# sensor_frontend_test_v0_5_1f4504da.net
KiCad netlist of a schematic drawn in EAGLE
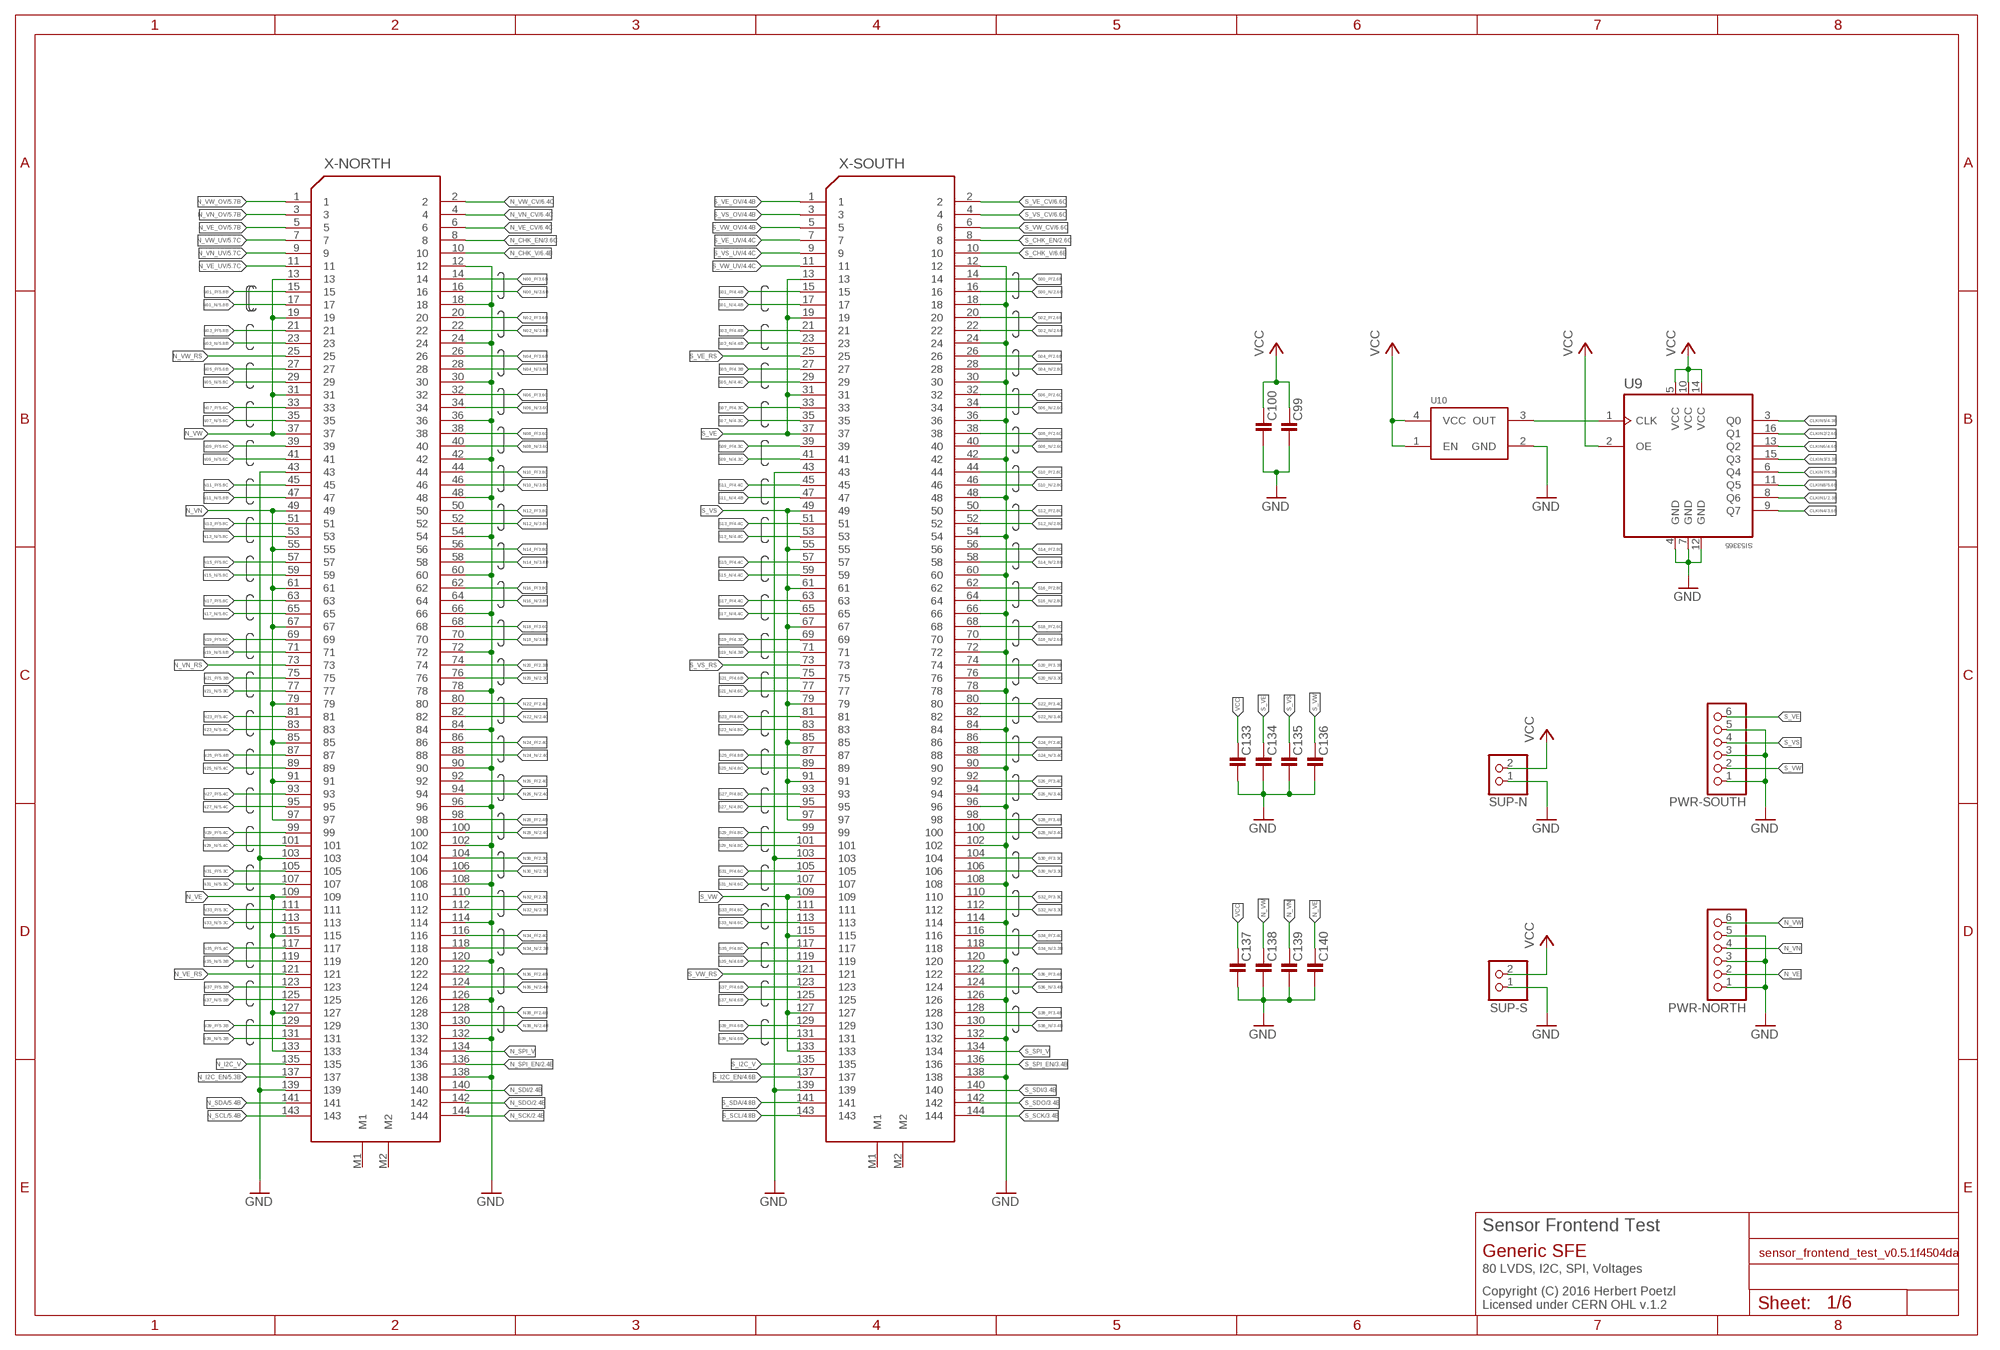
[diagram p0: schematic, sheet 1]
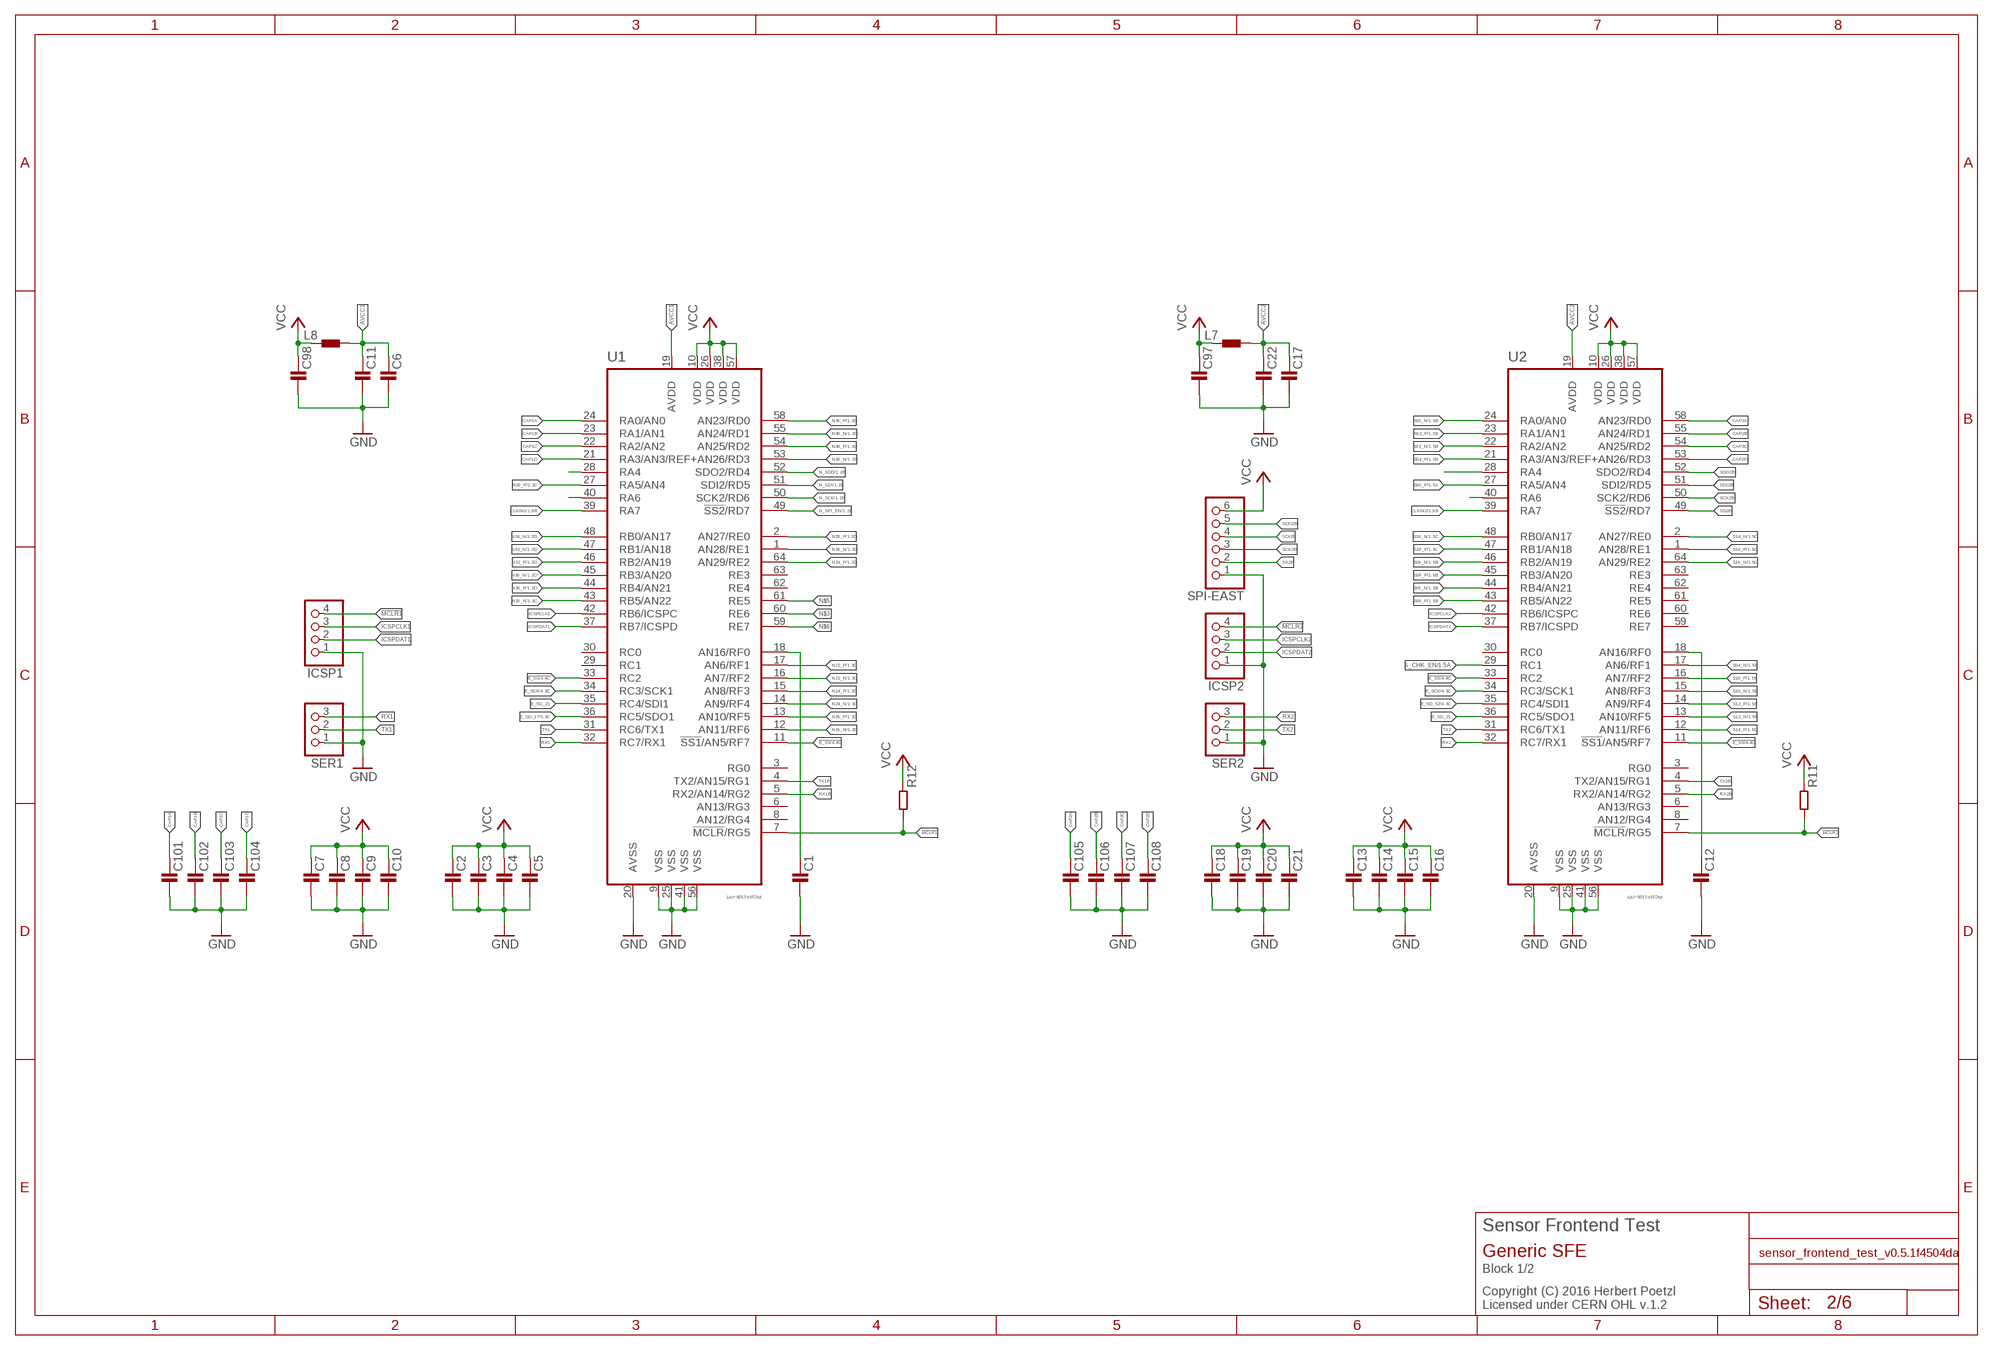
[diagram p1: schematic, sheet 2]
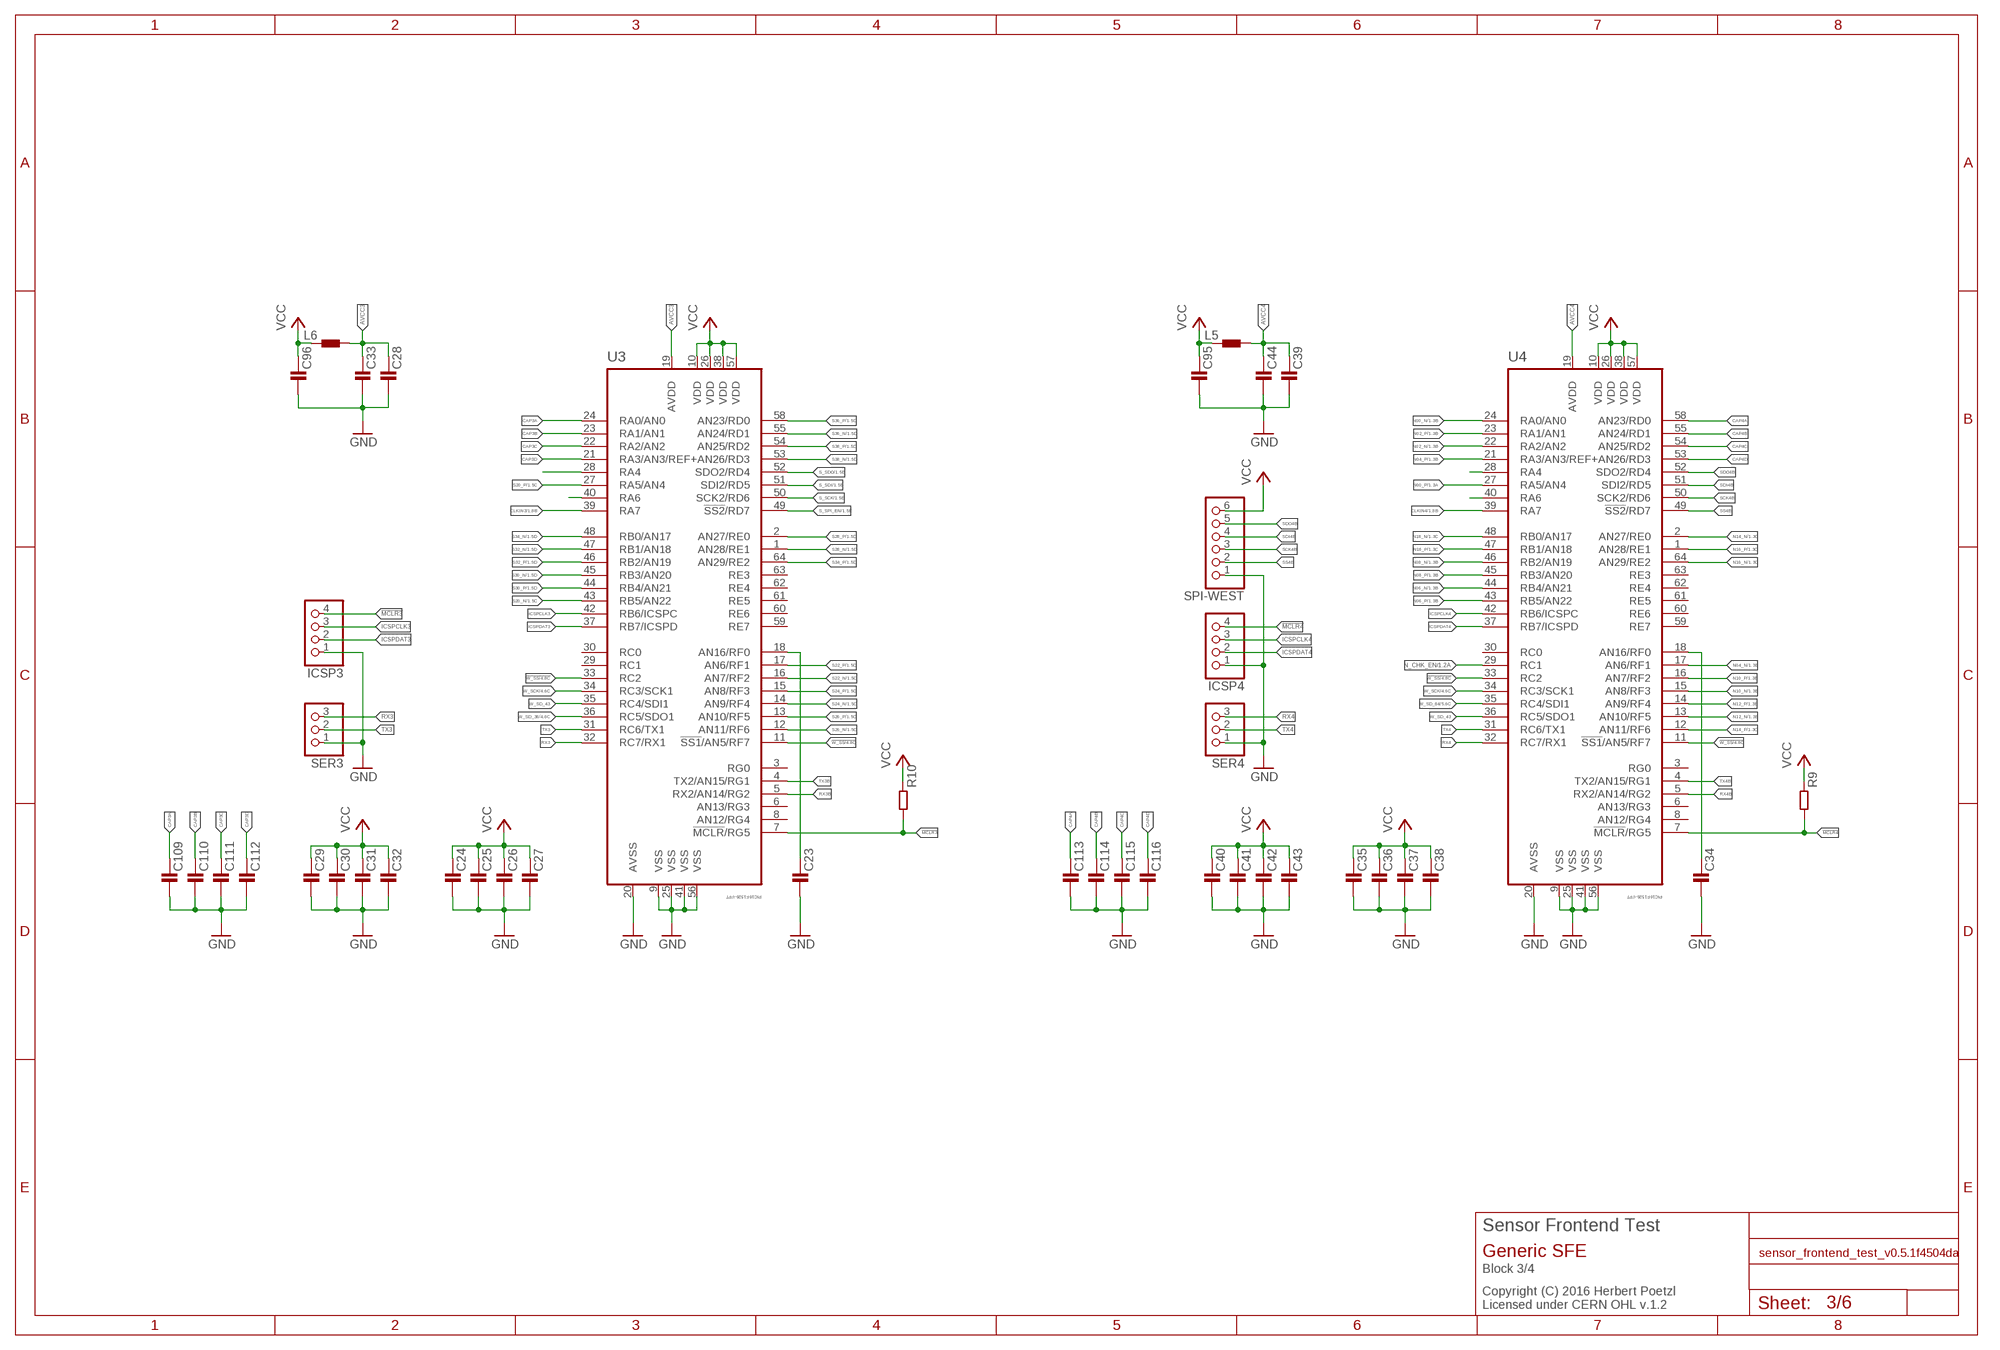
[diagram p2: schematic, sheet 3]
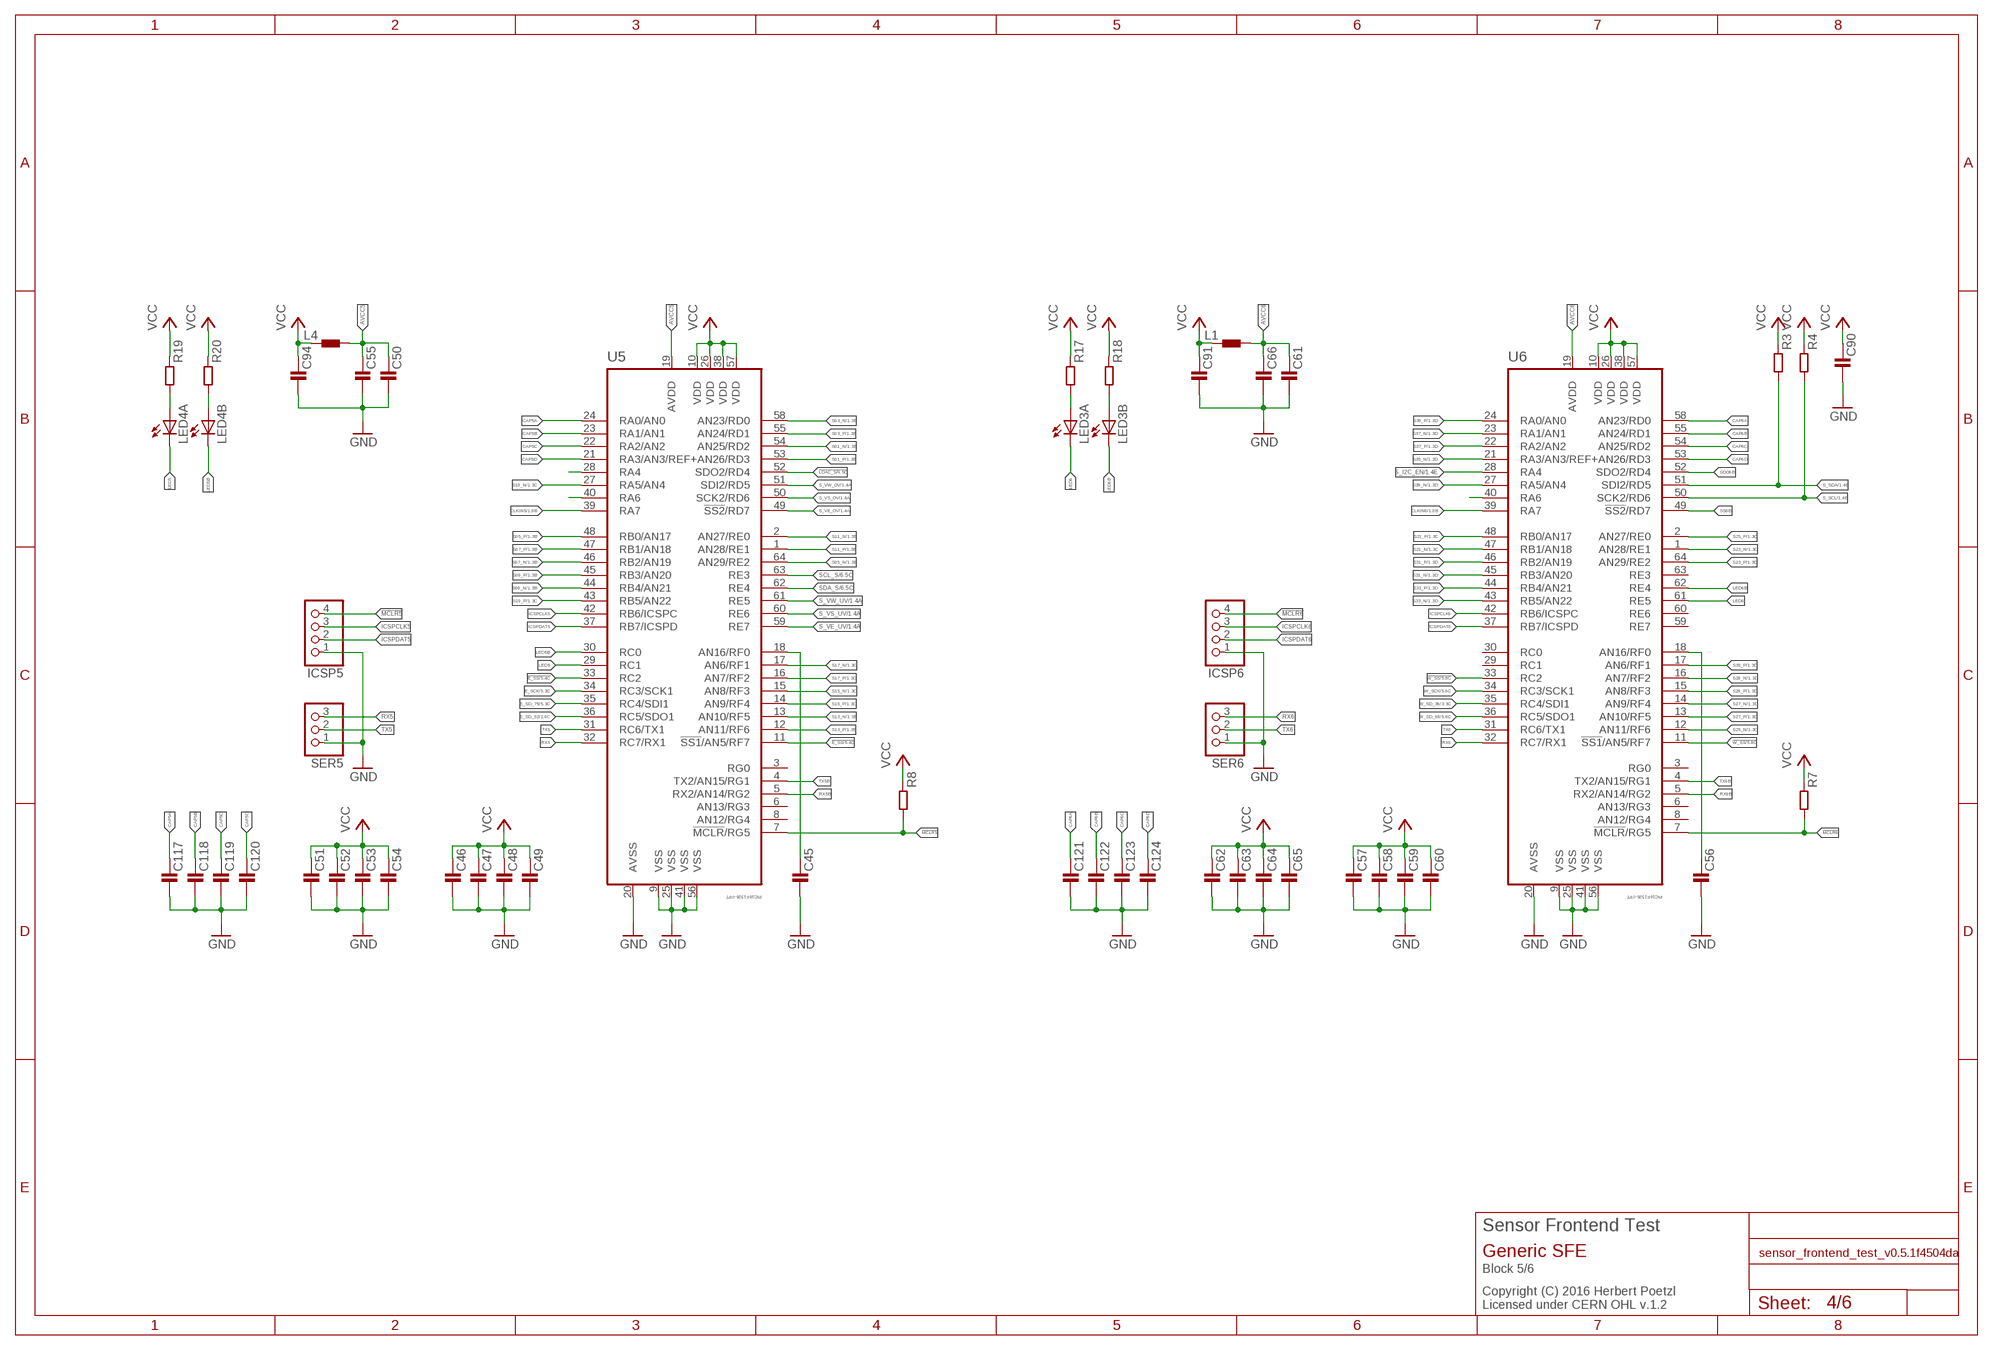
[diagram p3: schematic, sheet 4]
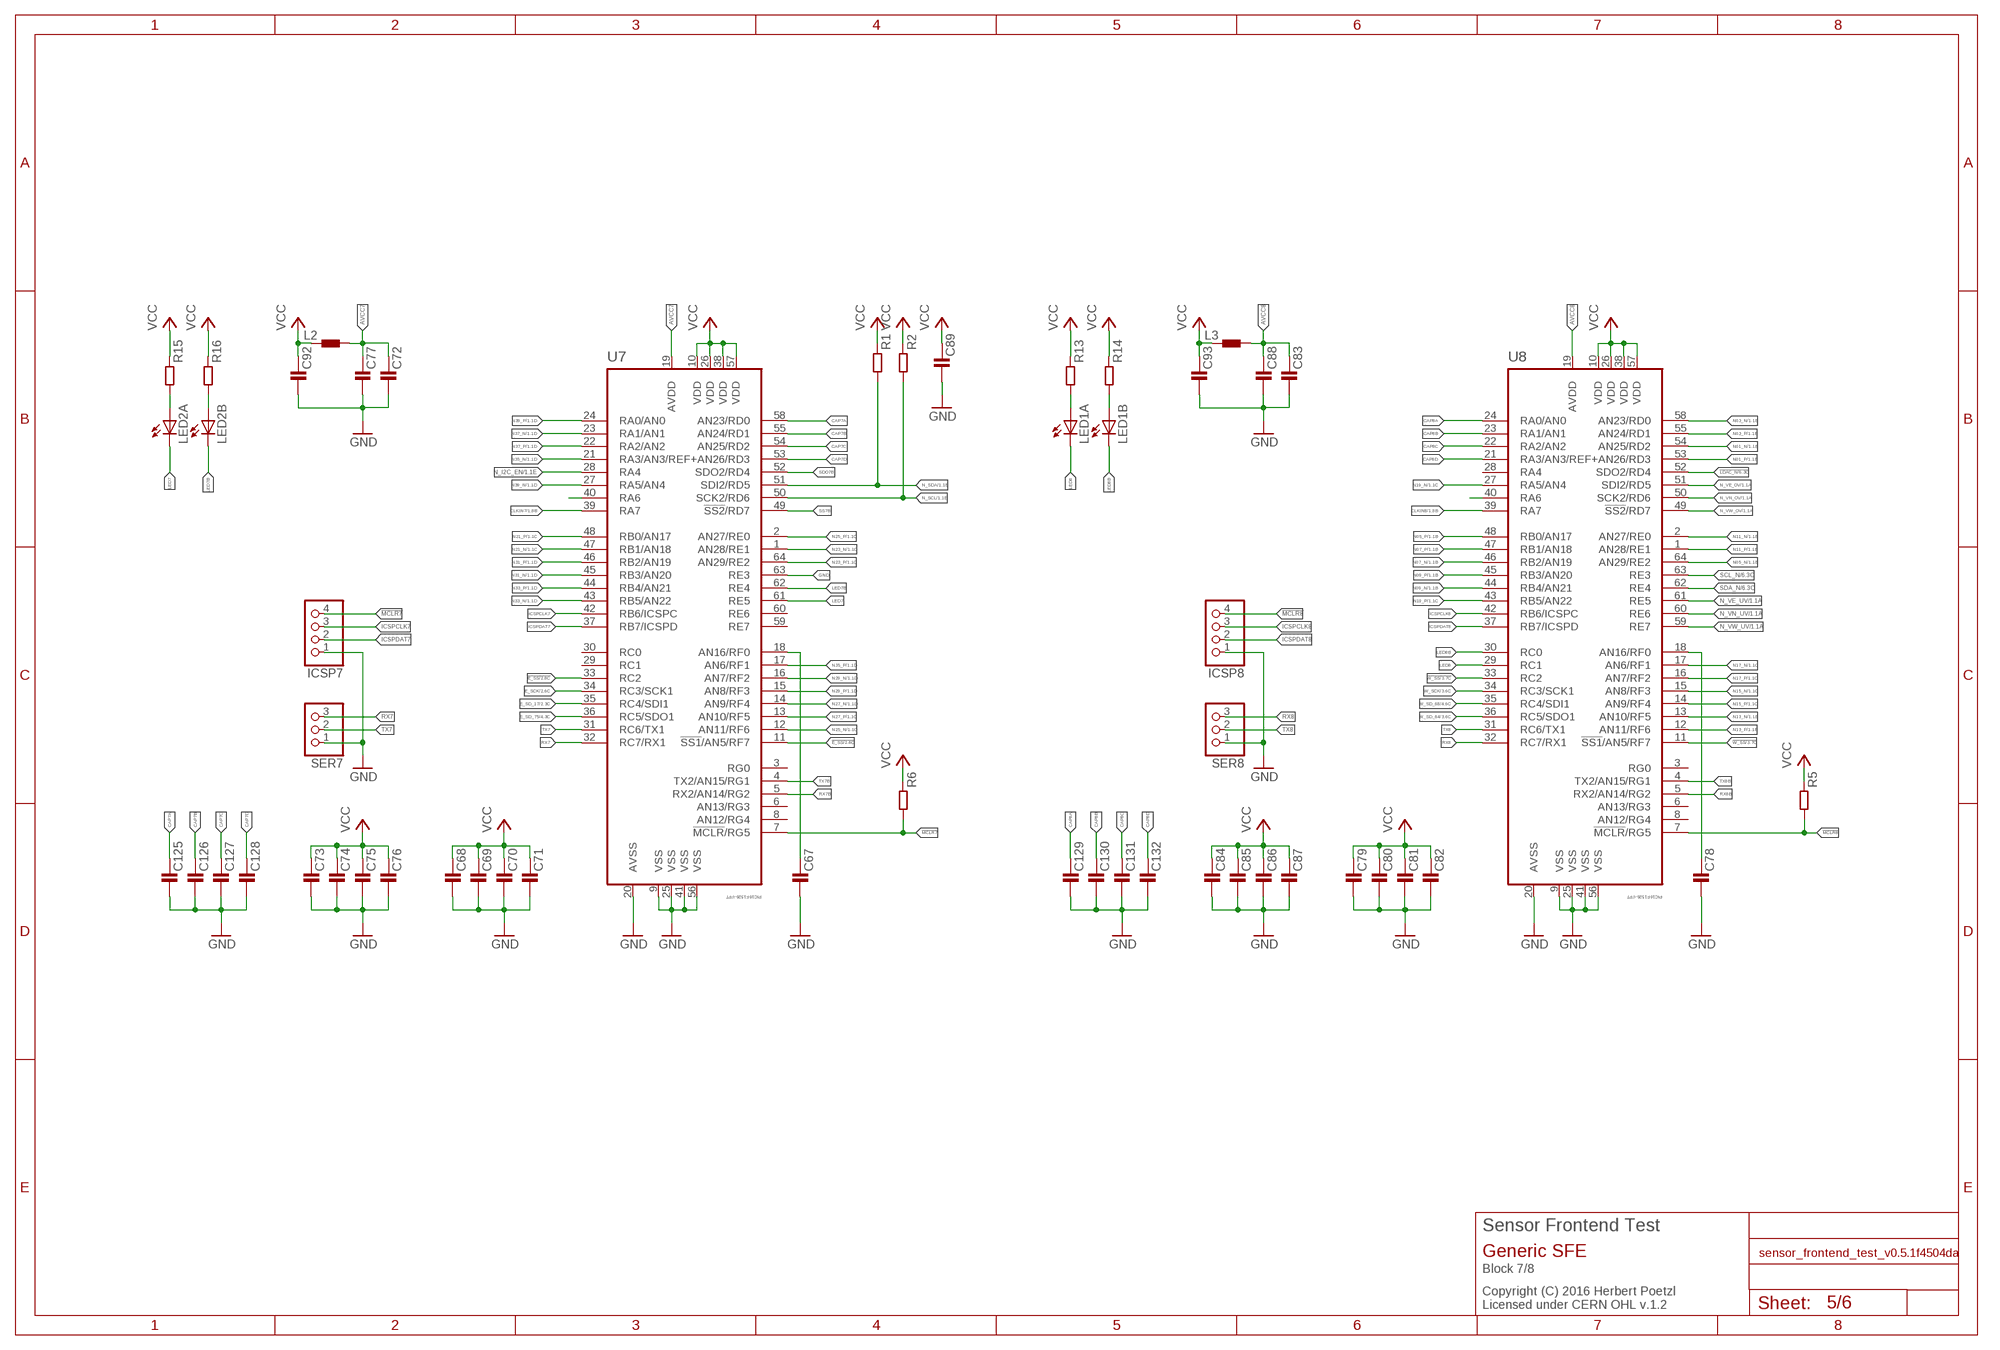
[diagram p4: schematic, sheet 5]
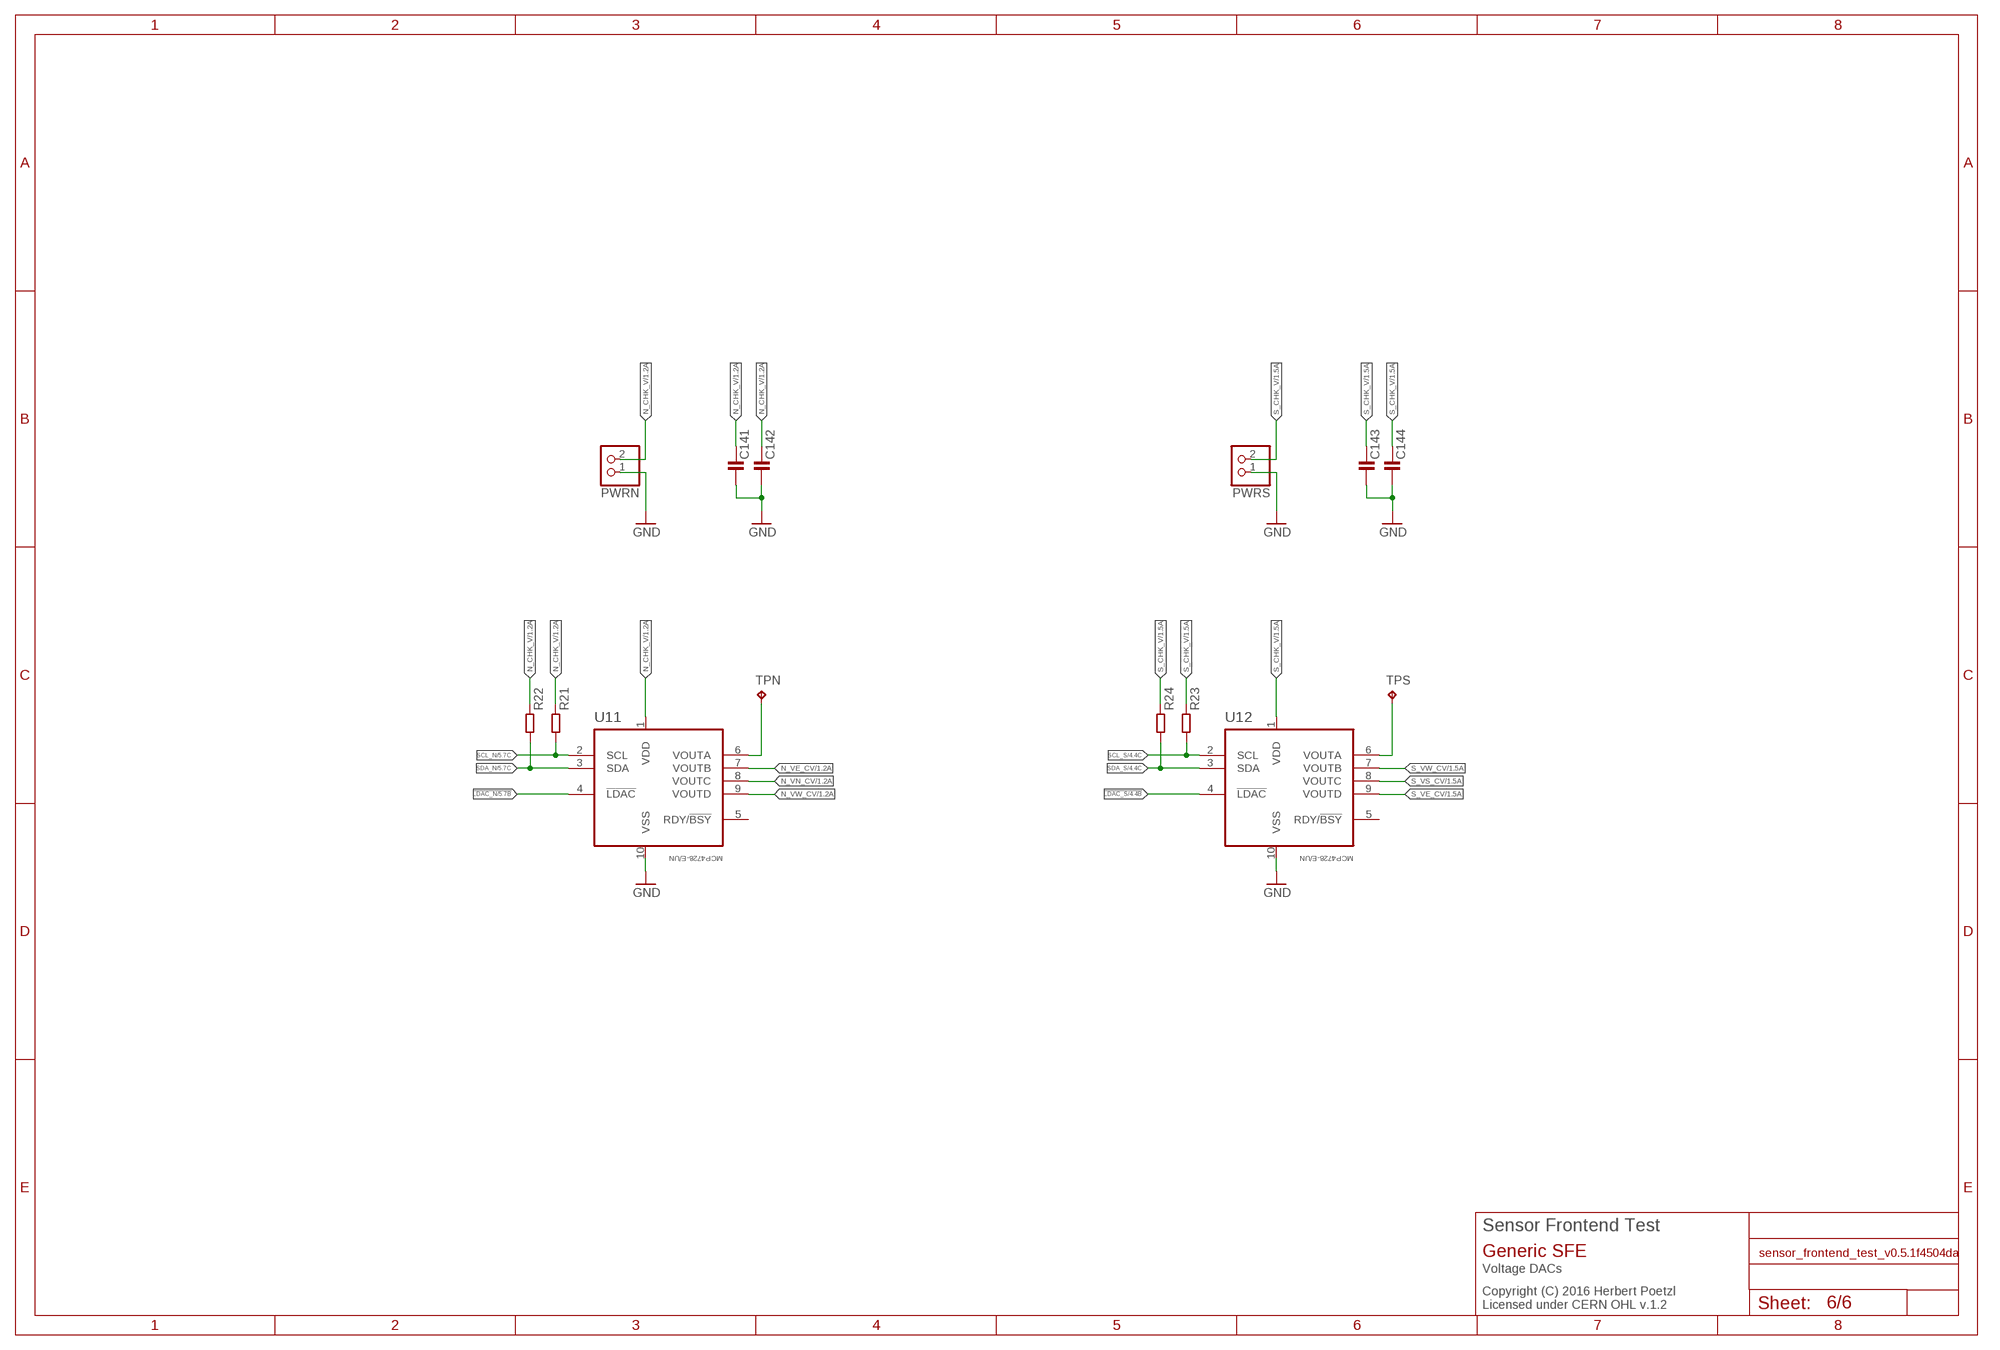
[diagram p5: schematic, sheet 6]

(export (version "E")
  (design (tool "Eeschema 10.0.6"))
  (components
    (comp (ref "C45")
      (value "C0402-B")
      (footprint "eagle-import:0402-B")
      (libsource (lib "eagle-import") (part "C0402-B"))
    )
    (comp (ref "C46")
      (value "C0402-B")
      (footprint "eagle-import:0402-B")
      (libsource (lib "eagle-import") (part "C0402-B"))
    )
    (comp (ref "C47")
      (value "C0402-B")
      (footprint "eagle-import:0402-B")
      (libsource (lib "eagle-import") (part "C0402-B"))
    )
    (comp (ref "C48")
      (value "C0402-B")
      (footprint "eagle-import:0402-B")
      (libsource (lib "eagle-import") (part "C0402-B"))
    )
    (comp (ref "C49")
      (value "C0402-B")
      (footprint "eagle-import:0402-B")
      (libsource (lib "eagle-import") (part "C0402-B"))
    )
    (comp (ref "C50")
      (value "C0402-B")
      (footprint "eagle-import:0402-B")
      (libsource (lib "eagle-import") (part "C0402-B"))
    )
    (comp (ref "C51")
      (value "C0402-B")
      (footprint "eagle-import:0402-B")
      (libsource (lib "eagle-import") (part "C0402-B"))
    )
    (comp (ref "C52")
      (value "C0402-B")
      (footprint "eagle-import:0402-B")
      (libsource (lib "eagle-import") (part "C0402-B"))
    )
    (comp (ref "C53")
      (value "C0402-B")
      (footprint "eagle-import:0402-B")
      (libsource (lib "eagle-import") (part "C0402-B"))
    )
    (comp (ref "C54")
      (value "C0402-B")
      (footprint "eagle-import:0402-B")
      (libsource (lib "eagle-import") (part "C0402-B"))
    )
    (comp (ref "C55")
      (value "C0402-B")
      (footprint "eagle-import:0402-B")
      (libsource (lib "eagle-import") (part "C0402-B"))
    )
    (comp (ref "C56")
      (value "C0402-B")
      (footprint "eagle-import:0402-B")
      (libsource (lib "eagle-import") (part "C0402-B"))
    )
    (comp (ref "C57")
      (value "C0402-B")
      (footprint "eagle-import:0402-B")
      (libsource (lib "eagle-import") (part "C0402-B"))
    )
    (comp (ref "C58")
      (value "C0402-B")
      (footprint "eagle-import:0402-B")
      (libsource (lib "eagle-import") (part "C0402-B"))
    )
    (comp (ref "C59")
      (value "C0402-B")
      (footprint "eagle-import:0402-B")
      (libsource (lib "eagle-import") (part "C0402-B"))
    )
    (comp (ref "C60")
      (value "C0402-B")
      (footprint "eagle-import:0402-B")
      (libsource (lib "eagle-import") (part "C0402-B"))
    )
    (comp (ref "C61")
      (value "C0402-B")
      (footprint "eagle-import:0402-B")
      (libsource (lib "eagle-import") (part "C0402-B"))
    )
    (comp (ref "C62")
      (value "C0402-B")
      (footprint "eagle-import:0402-B")
      (libsource (lib "eagle-import") (part "C0402-B"))
    )
    (comp (ref "C63")
      (value "C0402-B")
      (footprint "eagle-import:0402-B")
      (libsource (lib "eagle-import") (part "C0402-B"))
    )
    (comp (ref "C64")
      (value "C0402-B")
      (footprint "eagle-import:0402-B")
      (libsource (lib "eagle-import") (part "C0402-B"))
    )
    (comp (ref "C65")
      (value "C0402-B")
      (footprint "eagle-import:0402-B")
      (libsource (lib "eagle-import") (part "C0402-B"))
    )
    (comp (ref "C66")
      (value "C0402-B")
      (footprint "eagle-import:0402-B")
      (libsource (lib "eagle-import") (part "C0402-B"))
    )
    (comp (ref "C90")
      (value "C0402-B")
      (footprint "eagle-import:0402-B")
      (libsource (lib "eagle-import") (part "C0402-B"))
    )
    (comp (ref "C91")
      (value "C0402-B")
      (footprint "eagle-import:0402-B")
      (libsource (lib "eagle-import") (part "C0402-B"))
    )
    (comp (ref "C94")
      (value "C0402-B")
      (footprint "eagle-import:0402-B")
      (libsource (lib "eagle-import") (part "C0402-B"))
    )
    (comp (ref "C117")
      (value "C0402-B")
      (footprint "eagle-import:0402-B")
      (libsource (lib "eagle-import") (part "C0402-B"))
    )
    (comp (ref "C118")
      (value "C0402-B")
      (footprint "eagle-import:0402-B")
      (libsource (lib "eagle-import") (part "C0402-B"))
    )
    (comp (ref "C119")
      (value "C0603-B")
      (footprint "eagle-import:0603-B")
      (libsource (lib "eagle-import") (part "C0603-B"))
    )
    (comp (ref "C120")
      (value "C0603-B")
      (footprint "eagle-import:0603-B")
      (libsource (lib "eagle-import") (part "C0603-B"))
    )
    (comp (ref "C121")
      (value "C0402-B")
      (footprint "eagle-import:0402-B")
      (libsource (lib "eagle-import") (part "C0402-B"))
    )
    (comp (ref "C122")
      (value "C0402-B")
      (footprint "eagle-import:0402-B")
      (libsource (lib "eagle-import") (part "C0402-B"))
    )
    (comp (ref "C123")
      (value "C0603-B")
      (footprint "eagle-import:0603-B")
      (libsource (lib "eagle-import") (part "C0603-B"))
    )
    (comp (ref "C124")
      (value "C0603-B")
      (footprint "eagle-import:0603-B")
      (libsource (lib "eagle-import") (part "C0603-B"))
    )
    (comp (ref "ICSP5")
      (value "PINHD-1X04_2.00")
      (footprint "eagle-import:1X04M")
      (libsource (lib "eagle-import") (part "PINHD-1X04_2.00"))
    )
    (comp (ref "ICSP6")
      (value "PINHD-1X04_2.00")
      (footprint "eagle-import:1X04M")
      (libsource (lib "eagle-import") (part "PINHD-1X04_2.00"))
    )
    (comp (ref "L1")
      (value "L0402-B")
      (footprint "eagle-import:0402-B")
      (libsource (lib "eagle-import") (part "L0402-B"))
    )
    (comp (ref "L4")
      (value "L0402-B")
      (footprint "eagle-import:0402-B")
      (libsource (lib "eagle-import") (part "L0402-B"))
    )
    (comp (ref "LED3")
      (value "DUAL-LED-0404")
      (footprint "eagle-import:0404")
      (libsource (lib "eagle-import") (part "DUAL-LED-0404"))
    )
    (comp (ref "LED4")
      (value "DUAL-LED-0404")
      (footprint "eagle-import:0404")
      (libsource (lib "eagle-import") (part "DUAL-LED-0404"))
    )
    (comp (ref "R3")
      (value "R0402-B")
      (footprint "eagle-import:0402-B")
      (libsource (lib "eagle-import") (part "R0402-B"))
    )
    (comp (ref "R4")
      (value "R0402-B")
      (footprint "eagle-import:0402-B")
      (libsource (lib "eagle-import") (part "R0402-B"))
    )
    (comp (ref "R7")
      (value "R0402-B")
      (footprint "eagle-import:0402-B")
      (libsource (lib "eagle-import") (part "R0402-B"))
    )
    (comp (ref "R8")
      (value "R0402-B")
      (footprint "eagle-import:0402-B")
      (libsource (lib "eagle-import") (part "R0402-B"))
    )
    (comp (ref "R17")
      (value "R0402-B")
      (footprint "eagle-import:0402-B")
      (libsource (lib "eagle-import") (part "R0402-B"))
    )
    (comp (ref "R18")
      (value "R0402-B")
      (footprint "eagle-import:0402-B")
      (libsource (lib "eagle-import") (part "R0402-B"))
    )
    (comp (ref "R19")
      (value "R0402-B")
      (footprint "eagle-import:0402-B")
      (libsource (lib "eagle-import") (part "R0402-B"))
    )
    (comp (ref "R20")
      (value "R0402-B")
      (footprint "eagle-import:0402-B")
      (libsource (lib "eagle-import") (part "R0402-B"))
    )
    (comp (ref "SER5")
      (value "PINHD-1X03_2.00")
      (footprint "eagle-import:1X03M")
      (libsource (lib "eagle-import") (part "PINHD-1X03_2.00"))
    )
    (comp (ref "SER6")
      (value "PINHD-1X03_2.00")
      (footprint "eagle-import:1X03M")
      (libsource (lib "eagle-import") (part "PINHD-1X03_2.00"))
    )
    (comp (ref "U5")
      (value "PIC16F1526-I/PT")
      (footprint "eagle-import:QFP50P1200X1200X120-64N")
      (libsource (lib "eagle-import") (part "PIC16F1526-I/PT"))
    )
    (comp (ref "U6")
      (value "PIC16F1526-I/PT")
      (footprint "eagle-import:QFP50P1200X1200X120-64N")
      (libsource (lib "eagle-import") (part "PIC16F1526-I/PT"))
    )
    (comp (ref "C67")
      (value "C0402-B")
      (footprint "eagle-import:0402-B")
      (libsource (lib "eagle-import") (part "C0402-B"))
    )
    (comp (ref "C68")
      (value "C0402-B")
      (footprint "eagle-import:0402-B")
      (libsource (lib "eagle-import") (part "C0402-B"))
    )
    (comp (ref "C69")
      (value "C0402-B")
      (footprint "eagle-import:0402-B")
      (libsource (lib "eagle-import") (part "C0402-B"))
    )
    (comp (ref "C70")
      (value "C0402-B")
      (footprint "eagle-import:0402-B")
      (libsource (lib "eagle-import") (part "C0402-B"))
    )
    (comp (ref "C71")
      (value "C0402-B")
      (footprint "eagle-import:0402-B")
      (libsource (lib "eagle-import") (part "C0402-B"))
    )
    (comp (ref "C72")
      (value "C0402-B")
      (footprint "eagle-import:0402-B")
      (libsource (lib "eagle-import") (part "C0402-B"))
    )
    (comp (ref "C73")
      (value "C0402-B")
      (footprint "eagle-import:0402-B")
      (libsource (lib "eagle-import") (part "C0402-B"))
    )
    (comp (ref "C74")
      (value "C0402-B")
      (footprint "eagle-import:0402-B")
      (libsource (lib "eagle-import") (part "C0402-B"))
    )
    (comp (ref "C75")
      (value "C0402-B")
      (footprint "eagle-import:0402-B")
      (libsource (lib "eagle-import") (part "C0402-B"))
    )
    (comp (ref "C76")
      (value "C0402-B")
      (footprint "eagle-import:0402-B")
      (libsource (lib "eagle-import") (part "C0402-B"))
    )
    (comp (ref "C77")
      (value "C0402-B")
      (footprint "eagle-import:0402-B")
      (libsource (lib "eagle-import") (part "C0402-B"))
    )
    (comp (ref "C78")
      (value "C0402-B")
      (footprint "eagle-import:0402-B")
      (libsource (lib "eagle-import") (part "C0402-B"))
    )
    (comp (ref "C79")
      (value "C0402-B")
      (footprint "eagle-import:0402-B")
      (libsource (lib "eagle-import") (part "C0402-B"))
    )
    (comp (ref "C80")
      (value "C0402-B")
      (footprint "eagle-import:0402-B")
      (libsource (lib "eagle-import") (part "C0402-B"))
    )
    (comp (ref "C81")
      (value "C0402-B")
      (footprint "eagle-import:0402-B")
      (libsource (lib "eagle-import") (part "C0402-B"))
    )
    (comp (ref "C82")
      (value "C0402-B")
      (footprint "eagle-import:0402-B")
      (libsource (lib "eagle-import") (part "C0402-B"))
    )
    (comp (ref "C83")
      (value "C0402-B")
      (footprint "eagle-import:0402-B")
      (libsource (lib "eagle-import") (part "C0402-B"))
    )
    (comp (ref "C84")
      (value "C0402-B")
      (footprint "eagle-import:0402-B")
      (libsource (lib "eagle-import") (part "C0402-B"))
    )
    (comp (ref "C85")
      (value "C0402-B")
      (footprint "eagle-import:0402-B")
      (libsource (lib "eagle-import") (part "C0402-B"))
    )
    (comp (ref "C86")
      (value "C0402-B")
      (footprint "eagle-import:0402-B")
      (libsource (lib "eagle-import") (part "C0402-B"))
    )
    (comp (ref "C87")
      (value "C0402-B")
      (footprint "eagle-import:0402-B")
      (libsource (lib "eagle-import") (part "C0402-B"))
    )
    (comp (ref "C88")
      (value "C0402-B")
      (footprint "eagle-import:0402-B")
      (libsource (lib "eagle-import") (part "C0402-B"))
    )
    (comp (ref "C89")
      (value "C0402-B")
      (footprint "eagle-import:0402-B")
      (libsource (lib "eagle-import") (part "C0402-B"))
    )
    (comp (ref "C92")
      (value "C0402-B")
      (footprint "eagle-import:0402-B")
      (libsource (lib "eagle-import") (part "C0402-B"))
    )
    (comp (ref "C93")
      (value "C0402-B")
      (footprint "eagle-import:0402-B")
      (libsource (lib "eagle-import") (part "C0402-B"))
    )
    (comp (ref "C125")
      (value "C0402-B")
      (footprint "eagle-import:0402-B")
      (libsource (lib "eagle-import") (part "C0402-B"))
    )
    (comp (ref "C126")
      (value "C0402-B")
      (footprint "eagle-import:0402-B")
      (libsource (lib "eagle-import") (part "C0402-B"))
    )
    (comp (ref "C127")
      (value "C0603-B")
      (footprint "eagle-import:0603-B")
      (libsource (lib "eagle-import") (part "C0603-B"))
    )
    (comp (ref "C128")
      (value "C0603-B")
      (footprint "eagle-import:0603-B")
      (libsource (lib "eagle-import") (part "C0603-B"))
    )
    (comp (ref "C129")
      (value "C0402-B")
      (footprint "eagle-import:0402-B")
      (libsource (lib "eagle-import") (part "C0402-B"))
    )
    (comp (ref "C130")
      (value "C0402-B")
      (footprint "eagle-import:0402-B")
      (libsource (lib "eagle-import") (part "C0402-B"))
    )
    (comp (ref "C131")
      (value "C0603-B")
      (footprint "eagle-import:0603-B")
      (libsource (lib "eagle-import") (part "C0603-B"))
    )
    (comp (ref "C132")
      (value "C0603-B")
      (footprint "eagle-import:0603-B")
      (libsource (lib "eagle-import") (part "C0603-B"))
    )
    (comp (ref "ICSP7")
      (value "PINHD-1X04_2.00")
      (footprint "eagle-import:1X04M")
      (libsource (lib "eagle-import") (part "PINHD-1X04_2.00"))
    )
    (comp (ref "ICSP8")
      (value "PINHD-1X04_2.00")
      (footprint "eagle-import:1X04M")
      (libsource (lib "eagle-import") (part "PINHD-1X04_2.00"))
    )
    (comp (ref "L2")
      (value "L0402-B")
      (footprint "eagle-import:0402-B")
      (libsource (lib "eagle-import") (part "L0402-B"))
    )
    (comp (ref "L3")
      (value "L0402-B")
      (footprint "eagle-import:0402-B")
      (libsource (lib "eagle-import") (part "L0402-B"))
    )
    (comp (ref "LED1")
      (value "DUAL-LED-0404")
      (footprint "eagle-import:0404")
      (libsource (lib "eagle-import") (part "DUAL-LED-0404"))
    )
    (comp (ref "LED2")
      (value "DUAL-LED-0404")
      (footprint "eagle-import:0404")
      (libsource (lib "eagle-import") (part "DUAL-LED-0404"))
    )
    (comp (ref "R1")
      (value "R0402-B")
      (footprint "eagle-import:0402-B")
      (libsource (lib "eagle-import") (part "R0402-B"))
    )
    (comp (ref "R2")
      (value "R0402-B")
      (footprint "eagle-import:0402-B")
      (libsource (lib "eagle-import") (part "R0402-B"))
    )
    (comp (ref "R5")
      (value "R0402-B")
      (footprint "eagle-import:0402-B")
      (libsource (lib "eagle-import") (part "R0402-B"))
    )
    (comp (ref "R6")
      (value "R0402-B")
      (footprint "eagle-import:0402-B")
      (libsource (lib "eagle-import") (part "R0402-B"))
    )
    (comp (ref "R13")
      (value "R0402-B")
      (footprint "eagle-import:0402-B")
      (libsource (lib "eagle-import") (part "R0402-B"))
    )
    (comp (ref "R14")
      (value "R0402-B")
      (footprint "eagle-import:0402-B")
      (libsource (lib "eagle-import") (part "R0402-B"))
    )
    (comp (ref "R15")
      (value "R0402-B")
      (footprint "eagle-import:0402-B")
      (libsource (lib "eagle-import") (part "R0402-B"))
    )
    (comp (ref "R16")
      (value "R0402-B")
      (footprint "eagle-import:0402-B")
      (libsource (lib "eagle-import") (part "R0402-B"))
    )
    (comp (ref "SER7")
      (value "PINHD-1X03_2.00")
      (footprint "eagle-import:1X03M")
      (libsource (lib "eagle-import") (part "PINHD-1X03_2.00"))
    )
    (comp (ref "SER8")
      (value "PINHD-1X03_2.00")
      (footprint "eagle-import:1X03M")
      (libsource (lib "eagle-import") (part "PINHD-1X03_2.00"))
    )
    (comp (ref "U7")
      (value "PIC16F1526-I/PT")
      (footprint "eagle-import:QFP50P1200X1200X120-64N")
      (libsource (lib "eagle-import") (part "PIC16F1526-I/PT"))
    )
    (comp (ref "U8")
      (value "PIC16F1526-I/PT")
      (footprint "eagle-import:QFP50P1200X1200X120-64N")
      (libsource (lib "eagle-import") (part "PIC16F1526-I/PT"))
    )
    (comp (ref "C23")
      (value "C0402-B")
      (footprint "eagle-import:0402-B")
      (libsource (lib "eagle-import") (part "C0402-B"))
    )
    (comp (ref "C24")
      (value "C0402-B")
      (footprint "eagle-import:0402-B")
      (libsource (lib "eagle-import") (part "C0402-B"))
    )
    (comp (ref "C25")
      (value "C0402-B")
      (footprint "eagle-import:0402-B")
      (libsource (lib "eagle-import") (part "C0402-B"))
    )
    (comp (ref "C26")
      (value "C0402-B")
      (footprint "eagle-import:0402-B")
      (libsource (lib "eagle-import") (part "C0402-B"))
    )
    (comp (ref "C27")
      (value "C0402-B")
      (footprint "eagle-import:0402-B")
      (libsource (lib "eagle-import") (part "C0402-B"))
    )
    (comp (ref "C28")
      (value "C0402-B")
      (footprint "eagle-import:0402-B")
      (libsource (lib "eagle-import") (part "C0402-B"))
    )
    (comp (ref "C29")
      (value "C0402-B")
      (footprint "eagle-import:0402-B")
      (libsource (lib "eagle-import") (part "C0402-B"))
    )
    (comp (ref "C30")
      (value "C0402-B")
      (footprint "eagle-import:0402-B")
      (libsource (lib "eagle-import") (part "C0402-B"))
    )
    (comp (ref "C31")
      (value "C0402-B")
      (footprint "eagle-import:0402-B")
      (libsource (lib "eagle-import") (part "C0402-B"))
    )
    (comp (ref "C32")
      (value "C0402-B")
      (footprint "eagle-import:0402-B")
      (libsource (lib "eagle-import") (part "C0402-B"))
    )
    (comp (ref "C33")
      (value "C0402-B")
      (footprint "eagle-import:0402-B")
      (libsource (lib "eagle-import") (part "C0402-B"))
    )
    (comp (ref "C34")
      (value "C0402-B")
      (footprint "eagle-import:0402-B")
      (libsource (lib "eagle-import") (part "C0402-B"))
    )
    (comp (ref "C35")
      (value "C0402-B")
      (footprint "eagle-import:0402-B")
      (libsource (lib "eagle-import") (part "C0402-B"))
    )
    (comp (ref "C36")
      (value "C0402-B")
      (footprint "eagle-import:0402-B")
      (libsource (lib "eagle-import") (part "C0402-B"))
    )
    (comp (ref "C37")
      (value "C0402-B")
      (footprint "eagle-import:0402-B")
      (libsource (lib "eagle-import") (part "C0402-B"))
    )
    (comp (ref "C38")
      (value "C0402-B")
      (footprint "eagle-import:0402-B")
      (libsource (lib "eagle-import") (part "C0402-B"))
    )
    (comp (ref "C39")
      (value "C0402-B")
      (footprint "eagle-import:0402-B")
      (libsource (lib "eagle-import") (part "C0402-B"))
    )
    (comp (ref "C40")
      (value "C0402-B")
      (footprint "eagle-import:0402-B")
      (libsource (lib "eagle-import") (part "C0402-B"))
    )
    (comp (ref "C41")
      (value "C0402-B")
      (footprint "eagle-import:0402-B")
      (libsource (lib "eagle-import") (part "C0402-B"))
    )
    (comp (ref "C42")
      (value "C0402-B")
      (footprint "eagle-import:0402-B")
      (libsource (lib "eagle-import") (part "C0402-B"))
    )
    (comp (ref "C43")
      (value "C0402-B")
      (footprint "eagle-import:0402-B")
      (libsource (lib "eagle-import") (part "C0402-B"))
    )
    (comp (ref "C44")
      (value "C0402-B")
      (footprint "eagle-import:0402-B")
      (libsource (lib "eagle-import") (part "C0402-B"))
    )
    (comp (ref "C95")
      (value "C0402-B")
      (footprint "eagle-import:0402-B")
      (libsource (lib "eagle-import") (part "C0402-B"))
    )
    (comp (ref "C96")
      (value "C0402-B")
      (footprint "eagle-import:0402-B")
      (libsource (lib "eagle-import") (part "C0402-B"))
    )
    (comp (ref "C109")
      (value "C0402-B")
      (footprint "eagle-import:0402-B")
      (libsource (lib "eagle-import") (part "C0402-B"))
    )
    (comp (ref "C110")
      (value "C0402-B")
      (footprint "eagle-import:0402-B")
      (libsource (lib "eagle-import") (part "C0402-B"))
    )
    (comp (ref "C111")
      (value "C0603-B")
      (footprint "eagle-import:0603-B")
      (libsource (lib "eagle-import") (part "C0603-B"))
    )
    (comp (ref "C112")
      (value "C0603-B")
      (footprint "eagle-import:0603-B")
      (libsource (lib "eagle-import") (part "C0603-B"))
    )
    (comp (ref "C113")
      (value "C0402-B")
      (footprint "eagle-import:0402-B")
      (libsource (lib "eagle-import") (part "C0402-B"))
    )
    (comp (ref "C114")
      (value "C0402-B")
      (footprint "eagle-import:0402-B")
      (libsource (lib "eagle-import") (part "C0402-B"))
    )
    (comp (ref "C115")
      (value "C0603-B")
      (footprint "eagle-import:0603-B")
      (libsource (lib "eagle-import") (part "C0603-B"))
    )
    (comp (ref "C116")
      (value "C0603-B")
      (footprint "eagle-import:0603-B")
      (libsource (lib "eagle-import") (part "C0603-B"))
    )
    (comp (ref "ICSP3")
      (value "PINHD-1X04_2.00")
      (footprint "eagle-import:1X04M")
      (libsource (lib "eagle-import") (part "PINHD-1X04_2.00"))
    )
    (comp (ref "ICSP4")
      (value "PINHD-1X04_2.00")
      (footprint "eagle-import:1X04M")
      (libsource (lib "eagle-import") (part "PINHD-1X04_2.00"))
    )
    (comp (ref "L5")
      (value "L0402-B")
      (footprint "eagle-import:0402-B")
      (libsource (lib "eagle-import") (part "L0402-B"))
    )
    (comp (ref "L6")
      (value "L0402-B")
      (footprint "eagle-import:0402-B")
      (libsource (lib "eagle-import") (part "L0402-B"))
    )
    (comp (ref "R9")
      (value "R0402-B")
      (footprint "eagle-import:0402-B")
      (libsource (lib "eagle-import") (part "R0402-B"))
    )
    (comp (ref "R10")
      (value "R0402-B")
      (footprint "eagle-import:0402-B")
      (libsource (lib "eagle-import") (part "R0402-B"))
    )
    (comp (ref "SER3")
      (value "PINHD-1X03_2.00")
      (footprint "eagle-import:1X03M")
      (libsource (lib "eagle-import") (part "PINHD-1X03_2.00"))
    )
    (comp (ref "SER4")
      (value "PINHD-1X03_2.00")
      (footprint "eagle-import:1X03M")
      (libsource (lib "eagle-import") (part "PINHD-1X03_2.00"))
    )
    (comp (ref "SPI-WEST")
      (value "PINHD-1X06_2.00")
      (footprint "eagle-import:1X06M")
      (libsource (lib "eagle-import") (part "PINHD-1X06_2.00"))
    )
    (comp (ref "U3")
      (value "PIC16F1526-I/PT")
      (footprint "eagle-import:QFP50P1200X1200X120-64N")
      (libsource (lib "eagle-import") (part "PIC16F1526-I/PT"))
    )
    (comp (ref "U4")
      (value "PIC16F1526-I/PT")
      (footprint "eagle-import:QFP50P1200X1200X120-64N")
      (libsource (lib "eagle-import") (part "PIC16F1526-I/PT"))
    )
    (comp (ref "C141")
      (value "C0402-B")
      (footprint "eagle-import:0402-B")
      (libsource (lib "eagle-import") (part "C0402-B"))
    )
    (comp (ref "C142")
      (value "C0402-B")
      (footprint "eagle-import:0402-B")
      (libsource (lib "eagle-import") (part "C0402-B"))
    )
    (comp (ref "C143")
      (value "C0402-B")
      (footprint "eagle-import:0402-B")
      (libsource (lib "eagle-import") (part "C0402-B"))
    )
    (comp (ref "C144")
      (value "C0402-B")
      (footprint "eagle-import:0402-B")
      (libsource (lib "eagle-import") (part "C0402-B"))
    )
    (comp (ref "PWRN")
      (value "PINHD-1X02_2.00")
      (footprint "eagle-import:1X02M")
      (libsource (lib "eagle-import") (part "PINHD-1X02_2.00"))
    )
    (comp (ref "PWRS")
      (value "PINHD-1X02_2.00")
      (footprint "eagle-import:1X02M")
      (libsource (lib "eagle-import") (part "PINHD-1X02_2.00"))
    )
    (comp (ref "R21")
      (value "R0402-B")
      (footprint "eagle-import:0402-B")
      (libsource (lib "eagle-import") (part "R0402-B"))
    )
    (comp (ref "R22")
      (value "R0402-B")
      (footprint "eagle-import:0402-B")
      (libsource (lib "eagle-import") (part "R0402-B"))
    )
    (comp (ref "R23")
      (value "R0402-B")
      (footprint "eagle-import:0402-B")
      (libsource (lib "eagle-import") (part "R0402-B"))
    )
    (comp (ref "R24")
      (value "R0402-B")
      (footprint "eagle-import:0402-B")
      (libsource (lib "eagle-import") (part "R0402-B"))
    )
    (comp (ref "TPN")
      (value "TPTP16R")
      (footprint "eagle-import:TP16R")
      (libsource (lib "eagle-import") (part "TPTP16R"))
    )
    (comp (ref "TPS")
      (value "TPTP16R")
      (footprint "eagle-import:TP16R")
      (libsource (lib "eagle-import") (part "TPTP16R"))
    )
    (comp (ref "U11")
      (value "MCP4728-E/UN")
      (footprint "eagle-import:SOP50P490X110-10N")
      (libsource (lib "eagle-import") (part "MCP4728-E/UN"))
    )
    (comp (ref "U12")
      (value "MCP4728-E/UN")
      (footprint "eagle-import:SOP50P490X110-10N")
      (libsource (lib "eagle-import") (part "MCP4728-E/UN"))
    )
    (comp (ref "C99")
      (value "C0402-B")
      (footprint "eagle-import:0402-B")
      (libsource (lib "eagle-import") (part "C0402-B"))
    )
    (comp (ref "C100")
      (value "C0402-B")
      (footprint "eagle-import:0402-B")
      (libsource (lib "eagle-import") (part "C0402-B"))
    )
    (comp (ref "C133")
      (value "C0805-A")
      (footprint "eagle-import:0805-A")
      (libsource (lib "eagle-import") (part "C0805-A"))
    )
    (comp (ref "C134")
      (value "C0805-A")
      (footprint "eagle-import:0805-A")
      (libsource (lib "eagle-import") (part "C0805-A"))
    )
    (comp (ref "C135")
      (value "C0805-A")
      (footprint "eagle-import:0805-A")
      (libsource (lib "eagle-import") (part "C0805-A"))
    )
    (comp (ref "C136")
      (value "C0805-A")
      (footprint "eagle-import:0805-A")
      (libsource (lib "eagle-import") (part "C0805-A"))
    )
    (comp (ref "C137")
      (value "C0805-A")
      (footprint "eagle-import:0805-A")
      (libsource (lib "eagle-import") (part "C0805-A"))
    )
    (comp (ref "C138")
      (value "C0805-A")
      (footprint "eagle-import:0805-A")
      (libsource (lib "eagle-import") (part "C0805-A"))
    )
    (comp (ref "C139")
      (value "C0805-A")
      (footprint "eagle-import:0805-A")
      (libsource (lib "eagle-import") (part "C0805-A"))
    )
    (comp (ref "C140")
      (value "C0805-A")
      (footprint "eagle-import:0805-A")
      (libsource (lib "eagle-import") (part "C0805-A"))
    )
    (comp (ref "PWR-NORTH")
      (value "PINHD-1X06_2.54-S")
      (footprint "eagle-import:1X06-S")
      (libsource (lib "eagle-import") (part "PINHD-1X06_2.54-S"))
    )
    (comp (ref "PWR-SOUTH")
      (value "PINHD-1X06_2.54-S")
      (footprint "eagle-import:1X06-S")
      (libsource (lib "eagle-import") (part "PINHD-1X06_2.54-S"))
    )
    (comp (ref "SUP-N")
      (value "PINHD-1X02_2.54-S")
      (footprint "eagle-import:1X02-S")
      (libsource (lib "eagle-import") (part "PINHD-1X02_2.54-S"))
    )
    (comp (ref "SUP-S")
      (value "PINHD-1X02_2.54-S")
      (footprint "eagle-import:1X02-S")
      (libsource (lib "eagle-import") (part "PINHD-1X02_2.54-S"))
    )
    (comp (ref "U9")
      (value "SI53365")
      (footprint "eagle-import:SOP65P640X120-16N")
      (libsource (lib "eagle-import") (part "SI53365"))
    )
    (comp (ref "U10")
      (value "OSCILLATOR5X3-PIN1-INDICATED")
      (footprint "eagle-import:CRYSTAL-OSC-SMD-5X3")
      (libsource (lib "eagle-import") (part "OSCILLATOR5X3-PIN1-INDICATED"))
    )
    (comp (ref "X-NORTH")
      (value "FX10-144S")
      (footprint "eagle-import:FX10A-144S")
      (libsource (lib "eagle-import") (part "FX10-144S"))
    )
    (comp (ref "X-SOUTH")
      (value "FX10-144S")
      (footprint "eagle-import:FX10A-144S")
      (libsource (lib "eagle-import") (part "FX10-144S"))
    )
    (comp (ref "C1")
      (value "C0402-B")
      (footprint "eagle-import:0402-B")
      (libsource (lib "eagle-import") (part "C0402-B"))
    )
    (comp (ref "C2")
      (value "C0402-B")
      (footprint "eagle-import:0402-B")
      (libsource (lib "eagle-import") (part "C0402-B"))
    )
    (comp (ref "C3")
      (value "C0402-B")
      (footprint "eagle-import:0402-B")
      (libsource (lib "eagle-import") (part "C0402-B"))
    )
    (comp (ref "C4")
      (value "C0402-B")
      (footprint "eagle-import:0402-B")
      (libsource (lib "eagle-import") (part "C0402-B"))
    )
    (comp (ref "C5")
      (value "C0402-B")
      (footprint "eagle-import:0402-B")
      (libsource (lib "eagle-import") (part "C0402-B"))
    )
    (comp (ref "C6")
      (value "C0402-B")
      (footprint "eagle-import:0402-B")
      (libsource (lib "eagle-import") (part "C0402-B"))
    )
    (comp (ref "C7")
      (value "C0402-B")
      (footprint "eagle-import:0402-B")
      (libsource (lib "eagle-import") (part "C0402-B"))
    )
    (comp (ref "C8")
      (value "C0402-B")
      (footprint "eagle-import:0402-B")
      (libsource (lib "eagle-import") (part "C0402-B"))
    )
    (comp (ref "C9")
      (value "C0402-B")
      (footprint "eagle-import:0402-B")
      (libsource (lib "eagle-import") (part "C0402-B"))
    )
    (comp (ref "C10")
      (value "C0402-B")
      (footprint "eagle-import:0402-B")
      (libsource (lib "eagle-import") (part "C0402-B"))
    )
    (comp (ref "C11")
      (value "C0402-B")
      (footprint "eagle-import:0402-B")
      (libsource (lib "eagle-import") (part "C0402-B"))
    )
    (comp (ref "C12")
      (value "C0402-B")
      (footprint "eagle-import:0402-B")
      (libsource (lib "eagle-import") (part "C0402-B"))
    )
    (comp (ref "C13")
      (value "C0402-B")
      (footprint "eagle-import:0402-B")
      (libsource (lib "eagle-import") (part "C0402-B"))
    )
    (comp (ref "C14")
      (value "C0402-B")
      (footprint "eagle-import:0402-B")
      (libsource (lib "eagle-import") (part "C0402-B"))
    )
    (comp (ref "C15")
      (value "C0402-B")
      (footprint "eagle-import:0402-B")
      (libsource (lib "eagle-import") (part "C0402-B"))
    )
    (comp (ref "C16")
      (value "C0402-B")
      (footprint "eagle-import:0402-B")
      (libsource (lib "eagle-import") (part "C0402-B"))
    )
    (comp (ref "C17")
      (value "C0402-B")
      (footprint "eagle-import:0402-B")
      (libsource (lib "eagle-import") (part "C0402-B"))
    )
    (comp (ref "C18")
      (value "C0402-B")
      (footprint "eagle-import:0402-B")
      (libsource (lib "eagle-import") (part "C0402-B"))
    )
    (comp (ref "C19")
      (value "C0402-B")
      (footprint "eagle-import:0402-B")
      (libsource (lib "eagle-import") (part "C0402-B"))
    )
    (comp (ref "C20")
      (value "C0402-B")
      (footprint "eagle-import:0402-B")
      (libsource (lib "eagle-import") (part "C0402-B"))
    )
    (comp (ref "C21")
      (value "C0402-B")
      (footprint "eagle-import:0402-B")
      (libsource (lib "eagle-import") (part "C0402-B"))
    )
    (comp (ref "C22")
      (value "C0402-B")
      (footprint "eagle-import:0402-B")
      (libsource (lib "eagle-import") (part "C0402-B"))
    )
    (comp (ref "C97")
      (value "C0402-B")
      (footprint "eagle-import:0402-B")
      (libsource (lib "eagle-import") (part "C0402-B"))
    )
    (comp (ref "C98")
      (value "C0402-B")
      (footprint "eagle-import:0402-B")
      (libsource (lib "eagle-import") (part "C0402-B"))
    )
    (comp (ref "C101")
      (value "C0402-B")
      (footprint "eagle-import:0402-B")
      (libsource (lib "eagle-import") (part "C0402-B"))
    )
    (comp (ref "C102")
      (value "C0402-B")
      (footprint "eagle-import:0402-B")
      (libsource (lib "eagle-import") (part "C0402-B"))
    )
    (comp (ref "C103")
      (value "C0603-B")
      (footprint "eagle-import:0603-B")
      (libsource (lib "eagle-import") (part "C0603-B"))
    )
    (comp (ref "C104")
      (value "C0603-B")
      (footprint "eagle-import:0603-B")
      (libsource (lib "eagle-import") (part "C0603-B"))
    )
    (comp (ref "C105")
      (value "C0402-B")
      (footprint "eagle-import:0402-B")
      (libsource (lib "eagle-import") (part "C0402-B"))
    )
    (comp (ref "C106")
      (value "C0402-B")
      (footprint "eagle-import:0402-B")
      (libsource (lib "eagle-import") (part "C0402-B"))
    )
    (comp (ref "C107")
      (value "C0603-B")
      (footprint "eagle-import:0603-B")
      (libsource (lib "eagle-import") (part "C0603-B"))
    )
    (comp (ref "C108")
      (value "C0603-B")
      (footprint "eagle-import:0603-B")
      (libsource (lib "eagle-import") (part "C0603-B"))
    )
    (comp (ref "ICSP1")
      (value "PINHD-1X04_2.00")
      (footprint "eagle-import:1X04M")
      (libsource (lib "eagle-import") (part "PINHD-1X04_2.00"))
    )
    (comp (ref "ICSP2")
      (value "PINHD-1X04_2.00")
      (footprint "eagle-import:1X04M")
      (libsource (lib "eagle-import") (part "PINHD-1X04_2.00"))
    )
    (comp (ref "L7")
      (value "L0402-B")
      (footprint "eagle-import:0402-B")
      (libsource (lib "eagle-import") (part "L0402-B"))
    )
    (comp (ref "L8")
      (value "L0402-B")
      (footprint "eagle-import:0402-B")
      (libsource (lib "eagle-import") (part "L0402-B"))
    )
    (comp (ref "R11")
      (value "R0402-B")
      (footprint "eagle-import:0402-B")
      (libsource (lib "eagle-import") (part "R0402-B"))
    )
    (comp (ref "R12")
      (value "R0402-B")
      (footprint "eagle-import:0402-B")
      (libsource (lib "eagle-import") (part "R0402-B"))
    )
    (comp (ref "SER1")
      (value "PINHD-1X03_2.00")
      (footprint "eagle-import:1X03M")
      (libsource (lib "eagle-import") (part "PINHD-1X03_2.00"))
    )
    (comp (ref "SER2")
      (value "PINHD-1X03_2.00")
      (footprint "eagle-import:1X03M")
      (libsource (lib "eagle-import") (part "PINHD-1X03_2.00"))
    )
    (comp (ref "SPI-EAST")
      (value "PINHD-1X06_2.00")
      (footprint "eagle-import:1X06M")
      (libsource (lib "eagle-import") (part "PINHD-1X06_2.00"))
    )
    (comp (ref "U1")
      (value "PIC16F1526-I/PT")
      (footprint "eagle-import:QFP50P1200X1200X120-64N")
      (libsource (lib "eagle-import") (part "PIC16F1526-I/PT"))
    )
    (comp (ref "U2")
      (value "PIC16F1526-I/PT")
      (footprint "eagle-import:QFP50P1200X1200X120-64N")
      (libsource (lib "eagle-import") (part "PIC16F1526-I/PT"))
    )
  )
  (nets
    (net (code "1") (name "AVCC1") (class "Default")
      (node (ref "C11") (pin "1") (pinfunction "1_1") (pintype "passive"))
      (node (ref "C6") (pin "1") (pinfunction "1_1") (pintype "passive"))
      (node (ref "L8") (pin "2") (pinfunction "2_2") (pintype "passive"))
      (node (ref "U1") (pin "19") (pinfunction "AVDD_19") (pintype "power_in"))
    )
    (net (code "2") (name "AVCC2") (class "Default")
      (node (ref "C17") (pin "1") (pinfunction "1_1") (pintype "passive"))
      (node (ref "C22") (pin "1") (pinfunction "1_1") (pintype "passive"))
      (node (ref "L7") (pin "2") (pinfunction "2_2") (pintype "passive"))
      (node (ref "U2") (pin "19") (pinfunction "AVDD_19") (pintype "power_in"))
    )
    (net (code "3") (name "AVCC3") (class "Default")
      (node (ref "C28") (pin "1") (pinfunction "1_1") (pintype "passive"))
      (node (ref "C33") (pin "1") (pinfunction "1_1") (pintype "passive"))
      (node (ref "L6") (pin "2") (pinfunction "2_2") (pintype "passive"))
      (node (ref "U3") (pin "19") (pinfunction "AVDD_19") (pintype "power_in"))
    )
    (net (code "4") (name "AVCC4") (class "Default")
      (node (ref "C39") (pin "1") (pinfunction "1_1") (pintype "passive"))
      (node (ref "C44") (pin "1") (pinfunction "1_1") (pintype "passive"))
      (node (ref "L5") (pin "2") (pinfunction "2_2") (pintype "passive"))
      (node (ref "U4") (pin "19") (pinfunction "AVDD_19") (pintype "power_in"))
    )
    (net (code "5") (name "AVCC5") (class "Default")
      (node (ref "C50") (pin "1") (pinfunction "1_1") (pintype "passive"))
      (node (ref "C55") (pin "1") (pinfunction "1_1") (pintype "passive"))
      (node (ref "L4") (pin "2") (pinfunction "2_2") (pintype "passive"))
      (node (ref "U5") (pin "19") (pinfunction "AVDD_19") (pintype "power_in"))
    )
    (net (code "6") (name "AVCC6") (class "Default")
      (node (ref "C61") (pin "1") (pinfunction "1_1") (pintype "passive"))
      (node (ref "C66") (pin "1") (pinfunction "1_1") (pintype "passive"))
      (node (ref "L1") (pin "2") (pinfunction "2_2") (pintype "passive"))
      (node (ref "U6") (pin "19") (pinfunction "AVDD_19") (pintype "power_in"))
    )
    (net (code "7") (name "AVCC7") (class "Default")
      (node (ref "C72") (pin "1") (pinfunction "1_1") (pintype "passive"))
      (node (ref "C77") (pin "1") (pinfunction "1_1") (pintype "passive"))
      (node (ref "L2") (pin "2") (pinfunction "2_2") (pintype "passive"))
      (node (ref "U7") (pin "19") (pinfunction "AVDD_19") (pintype "power_in"))
    )
    (net (code "8") (name "AVCC8") (class "Default")
      (node (ref "C83") (pin "1") (pinfunction "1_1") (pintype "passive"))
      (node (ref "C88") (pin "1") (pinfunction "1_1") (pintype "passive"))
      (node (ref "L3") (pin "2") (pinfunction "2_2") (pintype "passive"))
      (node (ref "U8") (pin "19") (pinfunction "AVDD_19") (pintype "power_in"))
    )
    (net (code "9") (name "CAP1A") (class "Default")
      (node (ref "C101") (pin "1") (pinfunction "1_1") (pintype "passive"))
      (node (ref "U1") (pin "24") (pinfunction "RA0/AN0_24") (pintype "bidirectional"))
    )
    (net (code "10") (name "CAP1B") (class "Default")
      (node (ref "C102") (pin "1") (pinfunction "1_1") (pintype "passive"))
      (node (ref "U1") (pin "23") (pinfunction "RA1/AN1_23") (pintype "bidirectional"))
    )
    (net (code "11") (name "CAP1C") (class "Default")
      (node (ref "C103") (pin "1") (pinfunction "1_1") (pintype "passive"))
      (node (ref "U1") (pin "22") (pinfunction "RA2/AN2_22") (pintype "bidirectional"))
    )
    (net (code "12") (name "CAP1D") (class "Default")
      (node (ref "C104") (pin "1") (pinfunction "1_1") (pintype "passive"))
      (node (ref "U1") (pin "21") (pinfunction "RA3/AN3/REF+_21") (pintype "bidirectional"))
    )
    (net (code "13") (name "CAP2A") (class "Default")
      (node (ref "C105") (pin "1") (pinfunction "1_1") (pintype "passive"))
      (node (ref "U2") (pin "58") (pinfunction "AN23/RD0_58") (pintype "bidirectional"))
    )
    (net (code "14") (name "CAP2B") (class "Default")
      (node (ref "C106") (pin "1") (pinfunction "1_1") (pintype "passive"))
      (node (ref "U2") (pin "55") (pinfunction "AN24/RD1_55") (pintype "bidirectional"))
    )
    (net (code "15") (name "CAP2C") (class "Default")
      (node (ref "C107") (pin "1") (pinfunction "1_1") (pintype "passive"))
      (node (ref "U2") (pin "54") (pinfunction "AN25/RD2_54") (pintype "bidirectional"))
    )
    (net (code "16") (name "CAP2D") (class "Default")
      (node (ref "C108") (pin "1") (pinfunction "1_1") (pintype "passive"))
      (node (ref "U2") (pin "53") (pinfunction "AN26/RD3_53") (pintype "bidirectional"))
    )
    (net (code "17") (name "CAP3A") (class "Default")
      (node (ref "C109") (pin "1") (pinfunction "1_1") (pintype "passive"))
      (node (ref "U3") (pin "24") (pinfunction "RA0/AN0_24") (pintype "bidirectional"))
    )
    (net (code "18") (name "CAP3B") (class "Default")
      (node (ref "C110") (pin "1") (pinfunction "1_1") (pintype "passive"))
      (node (ref "U3") (pin "23") (pinfunction "RA1/AN1_23") (pintype "bidirectional"))
    )
    (net (code "19") (name "CAP3C") (class "Default")
      (node (ref "C111") (pin "1") (pinfunction "1_1") (pintype "passive"))
      (node (ref "U3") (pin "22") (pinfunction "RA2/AN2_22") (pintype "bidirectional"))
    )
    (net (code "20") (name "CAP3D") (class "Default")
      (node (ref "C112") (pin "1") (pinfunction "1_1") (pintype "passive"))
      (node (ref "U3") (pin "21") (pinfunction "RA3/AN3/REF+_21") (pintype "bidirectional"))
    )
    (net (code "21") (name "CAP4A") (class "Default")
      (node (ref "C113") (pin "1") (pinfunction "1_1") (pintype "passive"))
      (node (ref "U4") (pin "58") (pinfunction "AN23/RD0_58") (pintype "bidirectional"))
    )
    (net (code "22") (name "CAP4B") (class "Default")
      (node (ref "C114") (pin "1") (pinfunction "1_1") (pintype "passive"))
      (node (ref "U4") (pin "55") (pinfunction "AN24/RD1_55") (pintype "bidirectional"))
    )
    (net (code "23") (name "CAP4C") (class "Default")
      (node (ref "C115") (pin "1") (pinfunction "1_1") (pintype "passive"))
      (node (ref "U4") (pin "54") (pinfunction "AN25/RD2_54") (pintype "bidirectional"))
    )
    (net (code "24") (name "CAP4D") (class "Default")
      (node (ref "C116") (pin "1") (pinfunction "1_1") (pintype "passive"))
      (node (ref "U4") (pin "53") (pinfunction "AN26/RD3_53") (pintype "bidirectional"))
    )
    (net (code "25") (name "CAP5A") (class "Default")
      (node (ref "C117") (pin "1") (pinfunction "1_1") (pintype "passive"))
      (node (ref "U5") (pin "24") (pinfunction "RA0/AN0_24") (pintype "bidirectional"))
    )
    (net (code "26") (name "CAP5B") (class "Default")
      (node (ref "C118") (pin "1") (pinfunction "1_1") (pintype "passive"))
      (node (ref "U5") (pin "23") (pinfunction "RA1/AN1_23") (pintype "bidirectional"))
    )
    (net (code "27") (name "CAP5C") (class "Default")
      (node (ref "C119") (pin "1") (pinfunction "1_1") (pintype "passive"))
      (node (ref "U5") (pin "22") (pinfunction "RA2/AN2_22") (pintype "bidirectional"))
    )
    (net (code "28") (name "CAP5D") (class "Default")
      (node (ref "C120") (pin "1") (pinfunction "1_1") (pintype "passive"))
      (node (ref "U5") (pin "21") (pinfunction "RA3/AN3/REF+_21") (pintype "bidirectional"))
    )
    (net (code "29") (name "CAP6A") (class "Default")
      (node (ref "C121") (pin "1") (pinfunction "1_1") (pintype "passive"))
      (node (ref "U6") (pin "58") (pinfunction "AN23/RD0_58") (pintype "bidirectional"))
    )
    (net (code "30") (name "CAP6B") (class "Default")
      (node (ref "C122") (pin "1") (pinfunction "1_1") (pintype "passive"))
      (node (ref "U6") (pin "55") (pinfunction "AN24/RD1_55") (pintype "bidirectional"))
    )
    (net (code "31") (name "CAP6C") (class "Default")
      (node (ref "C123") (pin "1") (pinfunction "1_1") (pintype "passive"))
      (node (ref "U6") (pin "54") (pinfunction "AN25/RD2_54") (pintype "bidirectional"))
    )
    (net (code "32") (name "CAP6D") (class "Default")
      (node (ref "C124") (pin "1") (pinfunction "1_1") (pintype "passive"))
      (node (ref "U6") (pin "53") (pinfunction "AN26/RD3_53") (pintype "bidirectional"))
    )
    (net (code "33") (name "CAP7A") (class "Default")
      (node (ref "C125") (pin "1") (pinfunction "1_1") (pintype "passive"))
      (node (ref "U7") (pin "58") (pinfunction "AN23/RD0_58") (pintype "bidirectional"))
    )
    (net (code "34") (name "CAP7B") (class "Default")
      (node (ref "C126") (pin "1") (pinfunction "1_1") (pintype "passive"))
      (node (ref "U7") (pin "55") (pinfunction "AN24/RD1_55") (pintype "bidirectional"))
    )
    (net (code "35") (name "CAP7C") (class "Default")
      (node (ref "C127") (pin "1") (pinfunction "1_1") (pintype "passive"))
      (node (ref "U7") (pin "54") (pinfunction "AN25/RD2_54") (pintype "bidirectional"))
    )
    (net (code "36") (name "CAP7D") (class "Default")
      (node (ref "C128") (pin "1") (pinfunction "1_1") (pintype "passive"))
      (node (ref "U7") (pin "53") (pinfunction "AN26/RD3_53") (pintype "bidirectional"))
    )
    (net (code "37") (name "CAP8A") (class "Default")
      (node (ref "C129") (pin "1") (pinfunction "1_1") (pintype "passive"))
      (node (ref "U8") (pin "24") (pinfunction "RA0/AN0_24") (pintype "bidirectional"))
    )
    (net (code "38") (name "CAP8B") (class "Default")
      (node (ref "C130") (pin "1") (pinfunction "1_1") (pintype "passive"))
      (node (ref "U8") (pin "23") (pinfunction "RA1/AN1_23") (pintype "bidirectional"))
    )
    (net (code "39") (name "CAP8C") (class "Default")
      (node (ref "C131") (pin "1") (pinfunction "1_1") (pintype "passive"))
      (node (ref "U8") (pin "22") (pinfunction "RA2/AN2_22") (pintype "bidirectional"))
    )
    (net (code "40") (name "CAP8D") (class "Default")
      (node (ref "C132") (pin "1") (pinfunction "1_1") (pintype "passive"))
      (node (ref "U8") (pin "21") (pinfunction "RA3/AN3/REF+_21") (pintype "bidirectional"))
    )
    (net (code "41") (name "CLKIN1") (class "Default")
      (node (ref "U1") (pin "39") (pinfunction "RA7_39") (pintype "bidirectional"))
      (node (ref "U9") (pin "8") (pinfunction "Q6_8") (pintype "output"))
    )
    (net (code "42") (name "CLKIN2") (class "Default")
      (node (ref "U2") (pin "39") (pinfunction "RA7_39") (pintype "bidirectional"))
      (node (ref "U9") (pin "16") (pinfunction "Q1_16") (pintype "output"))
    )
    (net (code "43") (name "CLKIN3") (class "Default")
      (node (ref "U3") (pin "39") (pinfunction "RA7_39") (pintype "bidirectional"))
      (node (ref "U9") (pin "15") (pinfunction "Q3_15") (pintype "output"))
    )
    (net (code "44") (name "CLKIN4") (class "Default")
      (node (ref "U4") (pin "39") (pinfunction "RA7_39") (pintype "bidirectional"))
      (node (ref "U9") (pin "9") (pinfunction "Q7_9") (pintype "output"))
    )
    (net (code "45") (name "CLKIN5") (class "Default")
      (node (ref "U5") (pin "39") (pinfunction "RA7_39") (pintype "bidirectional"))
      (node (ref "U9") (pin "3") (pinfunction "Q0_3") (pintype "output"))
    )
    (net (code "46") (name "CLKIN6") (class "Default")
      (node (ref "U6") (pin "39") (pinfunction "RA7_39") (pintype "bidirectional"))
      (node (ref "U9") (pin "13") (pinfunction "Q2_13") (pintype "output"))
    )
    (net (code "47") (name "CLKIN7") (class "Default")
      (node (ref "U7") (pin "39") (pinfunction "RA7_39") (pintype "bidirectional"))
      (node (ref "U9") (pin "6") (pinfunction "Q4_6") (pintype "output"))
    )
    (net (code "48") (name "CLKIN8") (class "Default")
      (node (ref "U8") (pin "39") (pinfunction "RA7_39") (pintype "bidirectional"))
      (node (ref "U9") (pin "11") (pinfunction "Q5_11") (pintype "output"))
    )
    (net (code "49") (name "E_SCK") (class "Default")
      (node (ref "U1") (pin "34") (pinfunction "RC3/SCK1_34") (pintype "bidirectional"))
      (node (ref "U2") (pin "34") (pinfunction "RC3/SCK1_34") (pintype "bidirectional"))
      (node (ref "U5") (pin "34") (pinfunction "RC3/SCK1_34") (pintype "bidirectional"))
      (node (ref "U7") (pin "34") (pinfunction "RC3/SCK1_34") (pintype "bidirectional"))
    )
    (net (code "50") (name "E_SD_17") (class "Default")
      (node (ref "U1") (pin "36") (pinfunction "RC5/SDO1_36") (pintype "bidirectional"))
      (node (ref "U7") (pin "35") (pinfunction "RC4/SDI1_35") (pintype "bidirectional"))
    )
    (net (code "51") (name "E_SD_21") (class "Default")
      (node (ref "U1") (pin "35") (pinfunction "RC4/SDI1_35") (pintype "bidirectional"))
      (node (ref "U2") (pin "36") (pinfunction "RC5/SDO1_36") (pintype "bidirectional"))
    )
    (net (code "52") (name "E_SD_52") (class "Default")
      (node (ref "U2") (pin "35") (pinfunction "RC4/SDI1_35") (pintype "bidirectional"))
      (node (ref "U5") (pin "36") (pinfunction "RC5/SDO1_36") (pintype "bidirectional"))
    )
    (net (code "53") (name "E_SD_75") (class "Default")
      (node (ref "U5") (pin "35") (pinfunction "RC4/SDI1_35") (pintype "bidirectional"))
      (node (ref "U7") (pin "36") (pinfunction "RC5/SDO1_36") (pintype "bidirectional"))
    )
    (net (code "54") (name "GND") (class "Default")
      (node (ref "C1") (pin "2") (pinfunction "2_2") (pintype "passive"))
      (node (ref "C10") (pin "2") (pinfunction "2_2") (pintype "passive"))
      (node (ref "C100") (pin "2") (pinfunction "2_2") (pintype "passive"))
      (node (ref "C101") (pin "2") (pinfunction "2_2") (pintype "passive"))
      (node (ref "C102") (pin "2") (pinfunction "2_2") (pintype "passive"))
      (node (ref "C103") (pin "2") (pinfunction "2_2") (pintype "passive"))
      (node (ref "C104") (pin "2") (pinfunction "2_2") (pintype "passive"))
      (node (ref "C105") (pin "2") (pinfunction "2_2") (pintype "passive"))
      (node (ref "C106") (pin "2") (pinfunction "2_2") (pintype "passive"))
      (node (ref "C107") (pin "2") (pinfunction "2_2") (pintype "passive"))
      (node (ref "C108") (pin "2") (pinfunction "2_2") (pintype "passive"))
      (node (ref "C109") (pin "2") (pinfunction "2_2") (pintype "passive"))
      (node (ref "C11") (pin "2") (pinfunction "2_2") (pintype "passive"))
      (node (ref "C110") (pin "2") (pinfunction "2_2") (pintype "passive"))
      (node (ref "C111") (pin "2") (pinfunction "2_2") (pintype "passive"))
      (node (ref "C112") (pin "2") (pinfunction "2_2") (pintype "passive"))
      (node (ref "C113") (pin "2") (pinfunction "2_2") (pintype "passive"))
      (node (ref "C114") (pin "2") (pinfunction "2_2") (pintype "passive"))
      (node (ref "C115") (pin "2") (pinfunction "2_2") (pintype "passive"))
      (node (ref "C116") (pin "2") (pinfunction "2_2") (pintype "passive"))
      (node (ref "C117") (pin "2") (pinfunction "2_2") (pintype "passive"))
      (node (ref "C118") (pin "2") (pinfunction "2_2") (pintype "passive"))
      (node (ref "C119") (pin "2") (pinfunction "2_2") (pintype "passive"))
      (node (ref "C12") (pin "2") (pinfunction "2_2") (pintype "passive"))
      (node (ref "C120") (pin "2") (pinfunction "2_2") (pintype "passive"))
      (node (ref "C121") (pin "2") (pinfunction "2_2") (pintype "passive"))
      (node (ref "C122") (pin "2") (pinfunction "2_2") (pintype "passive"))
      (node (ref "C123") (pin "2") (pinfunction "2_2") (pintype "passive"))
      (node (ref "C124") (pin "2") (pinfunction "2_2") (pintype "passive"))
      (node (ref "C125") (pin "2") (pinfunction "2_2") (pintype "passive"))
      (node (ref "C126") (pin "2") (pinfunction "2_2") (pintype "passive"))
      (node (ref "C127") (pin "2") (pinfunction "2_2") (pintype "passive"))
      (node (ref "C128") (pin "2") (pinfunction "2_2") (pintype "passive"))
      (node (ref "C129") (pin "2") (pinfunction "2_2") (pintype "passive"))
      (node (ref "C13") (pin "2") (pinfunction "2_2") (pintype "passive"))
      (node (ref "C130") (pin "2") (pinfunction "2_2") (pintype "passive"))
      (node (ref "C131") (pin "2") (pinfunction "2_2") (pintype "passive"))
      (node (ref "C132") (pin "2") (pinfunction "2_2") (pintype "passive"))
      (node (ref "C133") (pin "2") (pinfunction "2_2") (pintype "passive"))
      (node (ref "C134") (pin "2") (pinfunction "2_2") (pintype "passive"))
      (node (ref "C135") (pin "2") (pinfunction "2_2") (pintype "passive"))
      (node (ref "C136") (pin "2") (pinfunction "2_2") (pintype "passive"))
      (node (ref "C137") (pin "2") (pinfunction "2_2") (pintype "passive"))
      (node (ref "C138") (pin "2") (pinfunction "2_2") (pintype "passive"))
      (node (ref "C139") (pin "2") (pinfunction "2_2") (pintype "passive"))
      (node (ref "C14") (pin "2") (pinfunction "2_2") (pintype "passive"))
      (node (ref "C140") (pin "2") (pinfunction "2_2") (pintype "passive"))
      (node (ref "C141") (pin "2") (pinfunction "2_2") (pintype "passive"))
      (node (ref "C142") (pin "2") (pinfunction "2_2") (pintype "passive"))
      (node (ref "C143") (pin "2") (pinfunction "2_2") (pintype "passive"))
      (node (ref "C144") (pin "2") (pinfunction "2_2") (pintype "passive"))
      (node (ref "C15") (pin "2") (pinfunction "2_2") (pintype "passive"))
      (node (ref "C16") (pin "2") (pinfunction "2_2") (pintype "passive"))
      (node (ref "C17") (pin "2") (pinfunction "2_2") (pintype "passive"))
      (node (ref "C18") (pin "2") (pinfunction "2_2") (pintype "passive"))
      (node (ref "C19") (pin "2") (pinfunction "2_2") (pintype "passive"))
      (node (ref "C2") (pin "2") (pinfunction "2_2") (pintype "passive"))
      (node (ref "C20") (pin "2") (pinfunction "2_2") (pintype "passive"))
      (node (ref "C21") (pin "2") (pinfunction "2_2") (pintype "passive"))
      (node (ref "C22") (pin "2") (pinfunction "2_2") (pintype "passive"))
      (node (ref "C23") (pin "2") (pinfunction "2_2") (pintype "passive"))
      (node (ref "C24") (pin "2") (pinfunction "2_2") (pintype "passive"))
      (node (ref "C25") (pin "2") (pinfunction "2_2") (pintype "passive"))
      (node (ref "C26") (pin "2") (pinfunction "2_2") (pintype "passive"))
      (node (ref "C27") (pin "2") (pinfunction "2_2") (pintype "passive"))
      (node (ref "C28") (pin "2") (pinfunction "2_2") (pintype "passive"))
      (node (ref "C29") (pin "2") (pinfunction "2_2") (pintype "passive"))
      (node (ref "C3") (pin "2") (pinfunction "2_2") (pintype "passive"))
      (node (ref "C30") (pin "2") (pinfunction "2_2") (pintype "passive"))
      (node (ref "C31") (pin "2") (pinfunction "2_2") (pintype "passive"))
      (node (ref "C32") (pin "2") (pinfunction "2_2") (pintype "passive"))
      (node (ref "C33") (pin "2") (pinfunction "2_2") (pintype "passive"))
      (node (ref "C34") (pin "2") (pinfunction "2_2") (pintype "passive"))
      (node (ref "C35") (pin "2") (pinfunction "2_2") (pintype "passive"))
      (node (ref "C36") (pin "2") (pinfunction "2_2") (pintype "passive"))
      (node (ref "C37") (pin "2") (pinfunction "2_2") (pintype "passive"))
      (node (ref "C38") (pin "2") (pinfunction "2_2") (pintype "passive"))
      (node (ref "C39") (pin "2") (pinfunction "2_2") (pintype "passive"))
      (node (ref "C4") (pin "2") (pinfunction "2_2") (pintype "passive"))
      (node (ref "C40") (pin "2") (pinfunction "2_2") (pintype "passive"))
      (node (ref "C41") (pin "2") (pinfunction "2_2") (pintype "passive"))
      (node (ref "C42") (pin "2") (pinfunction "2_2") (pintype "passive"))
      (node (ref "C43") (pin "2") (pinfunction "2_2") (pintype "passive"))
      (node (ref "C44") (pin "2") (pinfunction "2_2") (pintype "passive"))
      (node (ref "C45") (pin "2") (pinfunction "2_2") (pintype "passive"))
      (node (ref "C46") (pin "2") (pinfunction "2_2") (pintype "passive"))
      (node (ref "C47") (pin "2") (pinfunction "2_2") (pintype "passive"))
      (node (ref "C48") (pin "2") (pinfunction "2_2") (pintype "passive"))
      (node (ref "C49") (pin "2") (pinfunction "2_2") (pintype "passive"))
      (node (ref "C5") (pin "2") (pinfunction "2_2") (pintype "passive"))
      (node (ref "C50") (pin "2") (pinfunction "2_2") (pintype "passive"))
      (node (ref "C51") (pin "2") (pinfunction "2_2") (pintype "passive"))
      (node (ref "C52") (pin "2") (pinfunction "2_2") (pintype "passive"))
      (node (ref "C53") (pin "2") (pinfunction "2_2") (pintype "passive"))
      (node (ref "C54") (pin "2") (pinfunction "2_2") (pintype "passive"))
      (node (ref "C55") (pin "2") (pinfunction "2_2") (pintype "passive"))
      (node (ref "C56") (pin "2") (pinfunction "2_2") (pintype "passive"))
      (node (ref "C57") (pin "2") (pinfunction "2_2") (pintype "passive"))
      (node (ref "C58") (pin "2") (pinfunction "2_2") (pintype "passive"))
      (node (ref "C59") (pin "2") (pinfunction "2_2") (pintype "passive"))
      (node (ref "C6") (pin "2") (pinfunction "2_2") (pintype "passive"))
      (node (ref "C60") (pin "2") (pinfunction "2_2") (pintype "passive"))
      (node (ref "C61") (pin "2") (pinfunction "2_2") (pintype "passive"))
      (node (ref "C62") (pin "2") (pinfunction "2_2") (pintype "passive"))
      (node (ref "C63") (pin "2") (pinfunction "2_2") (pintype "passive"))
      (node (ref "C64") (pin "2") (pinfunction "2_2") (pintype "passive"))
      (node (ref "C65") (pin "2") (pinfunction "2_2") (pintype "passive"))
      (node (ref "C66") (pin "2") (pinfunction "2_2") (pintype "passive"))
      (node (ref "C67") (pin "2") (pinfunction "2_2") (pintype "passive"))
      (node (ref "C68") (pin "2") (pinfunction "2_2") (pintype "passive"))
      (node (ref "C69") (pin "2") (pinfunction "2_2") (pintype "passive"))
      (node (ref "C7") (pin "2") (pinfunction "2_2") (pintype "passive"))
      (node (ref "C70") (pin "2") (pinfunction "2_2") (pintype "passive"))
      (node (ref "C71") (pin "2") (pinfunction "2_2") (pintype "passive"))
      (node (ref "C72") (pin "2") (pinfunction "2_2") (pintype "passive"))
      (node (ref "C73") (pin "2") (pinfunction "2_2") (pintype "passive"))
      (node (ref "C74") (pin "2") (pinfunction "2_2") (pintype "passive"))
      (node (ref "C75") (pin "2") (pinfunction "2_2") (pintype "passive"))
      (node (ref "C76") (pin "2") (pinfunction "2_2") (pintype "passive"))
      (node (ref "C77") (pin "2") (pinfunction "2_2") (pintype "passive"))
      (node (ref "C78") (pin "2") (pinfunction "2_2") (pintype "passive"))
      (node (ref "C79") (pin "2") (pinfunction "2_2") (pintype "passive"))
      (node (ref "C8") (pin "2") (pinfunction "2_2") (pintype "passive"))
      (node (ref "C80") (pin "2") (pinfunction "2_2") (pintype "passive"))
      (node (ref "C81") (pin "2") (pinfunction "2_2") (pintype "passive"))
      (node (ref "C82") (pin "2") (pinfunction "2_2") (pintype "passive"))
      (node (ref "C83") (pin "2") (pinfunction "2_2") (pintype "passive"))
      (node (ref "C84") (pin "2") (pinfunction "2_2") (pintype "passive"))
      (node (ref "C85") (pin "2") (pinfunction "2_2") (pintype "passive"))
      (node (ref "C86") (pin "2") (pinfunction "2_2") (pintype "passive"))
      (node (ref "C87") (pin "2") (pinfunction "2_2") (pintype "passive"))
      (node (ref "C88") (pin "2") (pinfunction "2_2") (pintype "passive"))
      (node (ref "C89") (pin "2") (pinfunction "2_2") (pintype "passive"))
      (node (ref "C9") (pin "2") (pinfunction "2_2") (pintype "passive"))
      (node (ref "C90") (pin "2") (pinfunction "2_2") (pintype "passive"))
      (node (ref "C91") (pin "2") (pinfunction "2_2") (pintype "passive"))
      (node (ref "C92") (pin "2") (pinfunction "2_2") (pintype "passive"))
      (node (ref "C93") (pin "2") (pinfunction "2_2") (pintype "passive"))
      (node (ref "C94") (pin "2") (pinfunction "2_2") (pintype "passive"))
      (node (ref "C95") (pin "2") (pinfunction "2_2") (pintype "passive"))
      (node (ref "C96") (pin "2") (pinfunction "2_2") (pintype "passive"))
      (node (ref "C97") (pin "2") (pinfunction "2_2") (pintype "passive"))
      (node (ref "C98") (pin "2") (pinfunction "2_2") (pintype "passive"))
      (node (ref "C99") (pin "2") (pinfunction "2_2") (pintype "passive"))
      (node (ref "ICSP1") (pin "1") (pinfunction "1_1") (pintype "passive"))
      (node (ref "ICSP2") (pin "1") (pinfunction "1_1") (pintype "passive"))
      (node (ref "ICSP3") (pin "1") (pinfunction "1_1") (pintype "passive"))
      (node (ref "ICSP4") (pin "1") (pinfunction "1_1") (pintype "passive"))
      (node (ref "ICSP5") (pin "1") (pinfunction "1_1") (pintype "passive"))
      (node (ref "ICSP6") (pin "1") (pinfunction "1_1") (pintype "passive"))
      (node (ref "ICSP7") (pin "1") (pinfunction "1_1") (pintype "passive"))
      (node (ref "ICSP8") (pin "1") (pinfunction "1_1") (pintype "passive"))
      (node (ref "PWR-NORTH") (pin "1") (pinfunction "1_1") (pintype "passive"))
      (node (ref "PWR-NORTH") (pin "3") (pinfunction "3_3") (pintype "passive"))
      (node (ref "PWR-NORTH") (pin "5") (pinfunction "5_5") (pintype "passive"))
      (node (ref "PWR-SOUTH") (pin "1") (pinfunction "1_1") (pintype "passive"))
      (node (ref "PWR-SOUTH") (pin "3") (pinfunction "3_3") (pintype "passive"))
      (node (ref "PWR-SOUTH") (pin "5") (pinfunction "5_5") (pintype "passive"))
      (node (ref "PWRN") (pin "1") (pinfunction "1_1") (pintype "passive"))
      (node (ref "PWRS") (pin "1") (pinfunction "1_1") (pintype "passive"))
      (node (ref "SER1") (pin "1") (pinfunction "1_1") (pintype "passive"))
      (node (ref "SER2") (pin "1") (pinfunction "1_1") (pintype "passive"))
      (node (ref "SER3") (pin "1") (pinfunction "1_1") (pintype "passive"))
      (node (ref "SER4") (pin "1") (pinfunction "1_1") (pintype "passive"))
      (node (ref "SER5") (pin "1") (pinfunction "1_1") (pintype "passive"))
      (node (ref "SER6") (pin "1") (pinfunction "1_1") (pintype "passive"))
      (node (ref "SER7") (pin "1") (pinfunction "1_1") (pintype "passive"))
      (node (ref "SER8") (pin "1") (pinfunction "1_1") (pintype "passive"))
      (node (ref "SPI-EAST") (pin "1") (pinfunction "1_1") (pintype "passive"))
      (node (ref "SPI-WEST") (pin "1") (pinfunction "1_1") (pintype "passive"))
      (node (ref "SUP-N") (pin "1") (pinfunction "1_1") (pintype "passive"))
      (node (ref "SUP-S") (pin "1") (pinfunction "1_1") (pintype "passive"))
      (node (ref "U1") (pin "20") (pinfunction "AVSS_20") (pintype "power_in"))
      (node (ref "U1") (pin "25") (pinfunction "VSS_25") (pintype "power_in"))
      (node (ref "U1") (pin "41") (pinfunction "VSS_41") (pintype "power_in"))
      (node (ref "U1") (pin "56") (pinfunction "VSS_56") (pintype "power_in"))
      (node (ref "U1") (pin "9") (pinfunction "VSS_9") (pintype "power_in"))
      (node (ref "U10") (pin "2") (pinfunction "GND_2") (pintype "bidirectional"))
      (node (ref "U11") (pin "10") (pinfunction "VSS_10") (pintype "power_in"))
      (node (ref "U12") (pin "10") (pinfunction "VSS_10") (pintype "power_in"))
      (node (ref "U2") (pin "20") (pinfunction "AVSS_20") (pintype "power_in"))
      (node (ref "U2") (pin "25") (pinfunction "VSS_25") (pintype "power_in"))
      (node (ref "U2") (pin "41") (pinfunction "VSS_41") (pintype "power_in"))
      (node (ref "U2") (pin "56") (pinfunction "VSS_56") (pintype "power_in"))
      (node (ref "U2") (pin "9") (pinfunction "VSS_9") (pintype "power_in"))
      (node (ref "U3") (pin "20") (pinfunction "AVSS_20") (pintype "power_in"))
      (node (ref "U3") (pin "25") (pinfunction "VSS_25") (pintype "power_in"))
      (node (ref "U3") (pin "41") (pinfunction "VSS_41") (pintype "power_in"))
      (node (ref "U3") (pin "56") (pinfunction "VSS_56") (pintype "power_in"))
      (node (ref "U3") (pin "9") (pinfunction "VSS_9") (pintype "power_in"))
      (node (ref "U4") (pin "20") (pinfunction "AVSS_20") (pintype "power_in"))
      (node (ref "U4") (pin "25") (pinfunction "VSS_25") (pintype "power_in"))
      (node (ref "U4") (pin "41") (pinfunction "VSS_41") (pintype "power_in"))
      (node (ref "U4") (pin "56") (pinfunction "VSS_56") (pintype "power_in"))
      (node (ref "U4") (pin "9") (pinfunction "VSS_9") (pintype "power_in"))
      (node (ref "U5") (pin "20") (pinfunction "AVSS_20") (pintype "power_in"))
      (node (ref "U5") (pin "25") (pinfunction "VSS_25") (pintype "power_in"))
      (node (ref "U5") (pin "41") (pinfunction "VSS_41") (pintype "power_in"))
      (node (ref "U5") (pin "56") (pinfunction "VSS_56") (pintype "power_in"))
      (node (ref "U5") (pin "9") (pinfunction "VSS_9") (pintype "power_in"))
      (node (ref "U6") (pin "20") (pinfunction "AVSS_20") (pintype "power_in"))
      (node (ref "U6") (pin "25") (pinfunction "VSS_25") (pintype "power_in"))
      (node (ref "U6") (pin "41") (pinfunction "VSS_41") (pintype "power_in"))
      (node (ref "U6") (pin "56") (pinfunction "VSS_56") (pintype "power_in"))
      (node (ref "U6") (pin "9") (pinfunction "VSS_9") (pintype "power_in"))
      (node (ref "U7") (pin "20") (pinfunction "AVSS_20") (pintype "power_in"))
      (node (ref "U7") (pin "25") (pinfunction "VSS_25") (pintype "power_in"))
      (node (ref "U7") (pin "41") (pinfunction "VSS_41") (pintype "power_in"))
      (node (ref "U7") (pin "56") (pinfunction "VSS_56") (pintype "power_in"))
      (node (ref "U7") (pin "63") (pinfunction "RE3_63") (pintype "bidirectional"))
      (node (ref "U7") (pin "9") (pinfunction "VSS_9") (pintype "power_in"))
      (node (ref "U8") (pin "20") (pinfunction "AVSS_20") (pintype "power_in"))
      (node (ref "U8") (pin "25") (pinfunction "VSS_25") (pintype "power_in"))
      (node (ref "U8") (pin "41") (pinfunction "VSS_41") (pintype "power_in"))
      (node (ref "U8") (pin "56") (pinfunction "VSS_56") (pintype "power_in"))
      (node (ref "U8") (pin "9") (pinfunction "VSS_9") (pintype "power_in"))
      (node (ref "U9") (pin "12") (pinfunction "GND_12") (pintype "passive"))
      (node (ref "U9") (pin "4") (pinfunction "GND_4") (pintype "passive"))
      (node (ref "U9") (pin "7") (pinfunction "GND_7") (pintype "passive"))
      (node (ref "X-NORTH") (pin "102") (pinfunction "102_102") (pintype "bidirectional"))
      (node (ref "X-NORTH") (pin "103") (pinfunction "103_103") (pintype "bidirectional"))
      (node (ref "X-NORTH") (pin "108") (pinfunction "108_108") (pintype "bidirectional"))
      (node (ref "X-NORTH") (pin "114") (pinfunction "114_114") (pintype "bidirectional"))
      (node (ref "X-NORTH") (pin "12") (pinfunction "12_12") (pintype "bidirectional"))
      (node (ref "X-NORTH") (pin "120") (pinfunction "120_120") (pintype "bidirectional"))
      (node (ref "X-NORTH") (pin "126") (pinfunction "126_126") (pintype "bidirectional"))
      (node (ref "X-NORTH") (pin "132") (pinfunction "132_132") (pintype "bidirectional"))
      (node (ref "X-NORTH") (pin "138") (pinfunction "138_138") (pintype "bidirectional"))
      (node (ref "X-NORTH") (pin "139") (pinfunction "139_139") (pintype "bidirectional"))
      (node (ref "X-NORTH") (pin "18") (pinfunction "18_18") (pintype "bidirectional"))
      (node (ref "X-NORTH") (pin "24") (pinfunction "24_24") (pintype "bidirectional"))
      (node (ref "X-NORTH") (pin "30") (pinfunction "30_30") (pintype "bidirectional"))
      (node (ref "X-NORTH") (pin "36") (pinfunction "36_36") (pintype "bidirectional"))
      (node (ref "X-NORTH") (pin "42") (pinfunction "42_42") (pintype "bidirectional"))
      (node (ref "X-NORTH") (pin "43") (pinfunction "43_43") (pintype "bidirectional"))
      (node (ref "X-NORTH") (pin "48") (pinfunction "48_48") (pintype "bidirectional"))
      (node (ref "X-NORTH") (pin "54") (pinfunction "54_54") (pintype "bidirectional"))
      (node (ref "X-NORTH") (pin "60") (pinfunction "60_60") (pintype "bidirectional"))
      (node (ref "X-NORTH") (pin "66") (pinfunction "66_66") (pintype "bidirectional"))
      (node (ref "X-NORTH") (pin "72") (pinfunction "72_72") (pintype "bidirectional"))
      (node (ref "X-NORTH") (pin "78") (pinfunction "78_78") (pintype "bidirectional"))
      (node (ref "X-NORTH") (pin "84") (pinfunction "84_84") (pintype "bidirectional"))
      (node (ref "X-NORTH") (pin "90") (pinfunction "90_90") (pintype "bidirectional"))
      (node (ref "X-NORTH") (pin "96") (pinfunction "96_96") (pintype "bidirectional"))
      (node (ref "X-SOUTH") (pin "102") (pinfunction "102_102") (pintype "bidirectional"))
      (node (ref "X-SOUTH") (pin "103") (pinfunction "103_103") (pintype "bidirectional"))
      (node (ref "X-SOUTH") (pin "108") (pinfunction "108_108") (pintype "bidirectional"))
      (node (ref "X-SOUTH") (pin "114") (pinfunction "114_114") (pintype "bidirectional"))
      (node (ref "X-SOUTH") (pin "12") (pinfunction "12_12") (pintype "bidirectional"))
      (node (ref "X-SOUTH") (pin "120") (pinfunction "120_120") (pintype "bidirectional"))
      (node (ref "X-SOUTH") (pin "126") (pinfunction "126_126") (pintype "bidirectional"))
      (node (ref "X-SOUTH") (pin "132") (pinfunction "132_132") (pintype "bidirectional"))
      (node (ref "X-SOUTH") (pin "138") (pinfunction "138_138") (pintype "bidirectional"))
      (node (ref "X-SOUTH") (pin "139") (pinfunction "139_139") (pintype "bidirectional"))
      (node (ref "X-SOUTH") (pin "18") (pinfunction "18_18") (pintype "bidirectional"))
      (node (ref "X-SOUTH") (pin "24") (pinfunction "24_24") (pintype "bidirectional"))
      (node (ref "X-SOUTH") (pin "30") (pinfunction "30_30") (pintype "bidirectional"))
      (node (ref "X-SOUTH") (pin "36") (pinfunction "36_36") (pintype "bidirectional"))
      (node (ref "X-SOUTH") (pin "42") (pinfunction "42_42") (pintype "bidirectional"))
      (node (ref "X-SOUTH") (pin "43") (pinfunction "43_43") (pintype "bidirectional"))
      (node (ref "X-SOUTH") (pin "48") (pinfunction "48_48") (pintype "bidirectional"))
      (node (ref "X-SOUTH") (pin "54") (pinfunction "54_54") (pintype "bidirectional"))
      (node (ref "X-SOUTH") (pin "60") (pinfunction "60_60") (pintype "bidirectional"))
      (node (ref "X-SOUTH") (pin "66") (pinfunction "66_66") (pintype "bidirectional"))
      (node (ref "X-SOUTH") (pin "72") (pinfunction "72_72") (pintype "bidirectional"))
      (node (ref "X-SOUTH") (pin "78") (pinfunction "78_78") (pintype "bidirectional"))
      (node (ref "X-SOUTH") (pin "84") (pinfunction "84_84") (pintype "bidirectional"))
      (node (ref "X-SOUTH") (pin "90") (pinfunction "90_90") (pintype "bidirectional"))
      (node (ref "X-SOUTH") (pin "96") (pinfunction "96_96") (pintype "bidirectional"))
    )
    (net (code "55") (name "ICSPCLK1") (class "Default")
      (node (ref "ICSP1") (pin "3") (pinfunction "3_3") (pintype "passive"))
      (node (ref "U1") (pin "42") (pinfunction "RB6/ICSPC_42") (pintype "bidirectional"))
    )
    (net (code "56") (name "ICSPCLK2") (class "Default")
      (node (ref "ICSP2") (pin "3") (pinfunction "3_3") (pintype "passive"))
      (node (ref "U2") (pin "42") (pinfunction "RB6/ICSPC_42") (pintype "bidirectional"))
    )
    (net (code "57") (name "ICSPCLK3") (class "Default")
      (node (ref "ICSP3") (pin "3") (pinfunction "3_3") (pintype "passive"))
      (node (ref "U3") (pin "42") (pinfunction "RB6/ICSPC_42") (pintype "bidirectional"))
    )
    (net (code "58") (name "ICSPCLK4") (class "Default")
      (node (ref "ICSP4") (pin "3") (pinfunction "3_3") (pintype "passive"))
      (node (ref "U4") (pin "42") (pinfunction "RB6/ICSPC_42") (pintype "bidirectional"))
    )
    (net (code "59") (name "ICSPCLK5") (class "Default")
      (node (ref "ICSP5") (pin "3") (pinfunction "3_3") (pintype "passive"))
      (node (ref "U5") (pin "42") (pinfunction "RB6/ICSPC_42") (pintype "bidirectional"))
    )
    (net (code "60") (name "ICSPCLK6") (class "Default")
      (node (ref "ICSP6") (pin "3") (pinfunction "3_3") (pintype "passive"))
      (node (ref "U6") (pin "42") (pinfunction "RB6/ICSPC_42") (pintype "bidirectional"))
    )
    (net (code "61") (name "ICSPCLK7") (class "Default")
      (node (ref "ICSP7") (pin "3") (pinfunction "3_3") (pintype "passive"))
      (node (ref "U7") (pin "42") (pinfunction "RB6/ICSPC_42") (pintype "bidirectional"))
    )
    (net (code "62") (name "ICSPCLK8") (class "Default")
      (node (ref "ICSP8") (pin "3") (pinfunction "3_3") (pintype "passive"))
      (node (ref "U8") (pin "42") (pinfunction "RB6/ICSPC_42") (pintype "bidirectional"))
    )
    (net (code "63") (name "ICSPDAT1") (class "Default")
      (node (ref "ICSP1") (pin "2") (pinfunction "2_2") (pintype "passive"))
      (node (ref "U1") (pin "37") (pinfunction "RB7/ICSPD_37") (pintype "bidirectional"))
    )
    (net (code "64") (name "ICSPDAT2") (class "Default")
      (node (ref "ICSP2") (pin "2") (pinfunction "2_2") (pintype "passive"))
      (node (ref "U2") (pin "37") (pinfunction "RB7/ICSPD_37") (pintype "bidirectional"))
    )
    (net (code "65") (name "ICSPDAT3") (class "Default")
      (node (ref "ICSP3") (pin "2") (pinfunction "2_2") (pintype "passive"))
      (node (ref "U3") (pin "37") (pinfunction "RB7/ICSPD_37") (pintype "bidirectional"))
    )
    (net (code "66") (name "ICSPDAT4") (class "Default")
      (node (ref "ICSP4") (pin "2") (pinfunction "2_2") (pintype "passive"))
      (node (ref "U4") (pin "37") (pinfunction "RB7/ICSPD_37") (pintype "bidirectional"))
    )
    (net (code "67") (name "ICSPDAT5") (class "Default")
      (node (ref "ICSP5") (pin "2") (pinfunction "2_2") (pintype "passive"))
      (node (ref "U5") (pin "37") (pinfunction "RB7/ICSPD_37") (pintype "bidirectional"))
    )
    (net (code "68") (name "ICSPDAT6") (class "Default")
      (node (ref "ICSP6") (pin "2") (pinfunction "2_2") (pintype "passive"))
      (node (ref "U6") (pin "37") (pinfunction "RB7/ICSPD_37") (pintype "bidirectional"))
    )
    (net (code "69") (name "ICSPDAT7") (class "Default")
      (node (ref "ICSP7") (pin "2") (pinfunction "2_2") (pintype "passive"))
      (node (ref "U7") (pin "37") (pinfunction "RB7/ICSPD_37") (pintype "bidirectional"))
    )
    (net (code "70") (name "ICSPDAT8") (class "Default")
      (node (ref "ICSP8") (pin "2") (pinfunction "2_2") (pintype "passive"))
      (node (ref "U8") (pin "37") (pinfunction "RB7/ICSPD_37") (pintype "bidirectional"))
    )
    (net (code "71") (name "LED5") (class "Default")
      (node (ref "LED4") (pin "4") (pinfunction "C_4") (pintype "passive"))
      (node (ref "U5") (pin "29") (pinfunction "RC1_29") (pintype "bidirectional"))
    )
    (net (code "72") (name "LED5B") (class "Default")
      (node (ref "LED4") (pin "3") (pinfunction "C_3") (pintype "passive"))
      (node (ref "U5") (pin "30") (pinfunction "RC0_30") (pintype "bidirectional"))
    )
    (net (code "73") (name "LED6") (class "Default")
      (node (ref "LED3") (pin "4") (pinfunction "C_4") (pintype "passive"))
      (node (ref "U6") (pin "61") (pinfunction "RE5_61") (pintype "bidirectional"))
    )
    (net (code "74") (name "LED6B") (class "Default")
      (node (ref "LED3") (pin "3") (pinfunction "C_3") (pintype "passive"))
      (node (ref "U6") (pin "62") (pinfunction "RE4_62") (pintype "bidirectional"))
    )
    (net (code "75") (name "LED7") (class "Default")
      (node (ref "LED2") (pin "4") (pinfunction "C_4") (pintype "passive"))
      (node (ref "U7") (pin "61") (pinfunction "RE5_61") (pintype "bidirectional"))
    )
    (net (code "76") (name "LED7B") (class "Default")
      (node (ref "LED2") (pin "3") (pinfunction "C_3") (pintype "passive"))
      (node (ref "U7") (pin "62") (pinfunction "RE4_62") (pintype "bidirectional"))
    )
    (net (code "77") (name "LED8") (class "Default")
      (node (ref "LED1") (pin "4") (pinfunction "C_4") (pintype "passive"))
      (node (ref "U8") (pin "29") (pinfunction "RC1_29") (pintype "bidirectional"))
    )
    (net (code "78") (name "LED8B") (class "Default")
      (node (ref "LED1") (pin "3") (pinfunction "C_3") (pintype "passive"))
      (node (ref "U8") (pin "30") (pinfunction "RC0_30") (pintype "bidirectional"))
    )
    (net (code "79") (name "N$3") (class "Default")
      (node (ref "U1") (pin "60") (pinfunction "RE6_60") (pintype "bidirectional"))
    )
    (net (code "80") (name "N$5") (class "Default")
      (node (ref "U1") (pin "61") (pinfunction "RE5_61") (pintype "bidirectional"))
    )
    (net (code "81") (name "N$6") (class "Default")
      (node (ref "U1") (pin "59") (pinfunction "RE7_59") (pintype "bidirectional"))
    )
    (net (code "82") (name "N00_N") (class "Default")
      (node (ref "U4") (pin "24") (pinfunction "RA0/AN0_24") (pintype "bidirectional"))
      (node (ref "X-NORTH") (pin "16") (pinfunction "16_16") (pintype "bidirectional"))
    )
    (net (code "83") (name "N00_P") (class "Default")
      (node (ref "U4") (pin "27") (pinfunction "RA5/AN4_27") (pintype "bidirectional"))
      (node (ref "X-NORTH") (pin "14") (pinfunction "14_14") (pintype "bidirectional"))
    )
    (net (code "84") (name "N01_N") (class "Default")
      (node (ref "U8") (pin "54") (pinfunction "AN25/RD2_54") (pintype "bidirectional"))
      (node (ref "X-NORTH") (pin "17") (pinfunction "17_17") (pintype "bidirectional"))
    )
    (net (code "85") (name "N01_P") (class "Default")
      (node (ref "U8") (pin "53") (pinfunction "AN26/RD3_53") (pintype "bidirectional"))
      (node (ref "X-NORTH") (pin "15") (pinfunction "15_15") (pintype "bidirectional"))
    )
    (net (code "86") (name "N02_N") (class "Default")
      (node (ref "U4") (pin "22") (pinfunction "RA2/AN2_22") (pintype "bidirectional"))
      (node (ref "X-NORTH") (pin "22") (pinfunction "22_22") (pintype "bidirectional"))
    )
    (net (code "87") (name "N02_P") (class "Default")
      (node (ref "U4") (pin "23") (pinfunction "RA1/AN1_23") (pintype "bidirectional"))
      (node (ref "X-NORTH") (pin "20") (pinfunction "20_20") (pintype "bidirectional"))
    )
    (net (code "88") (name "N03_N") (class "Default")
      (node (ref "U8") (pin "58") (pinfunction "AN23/RD0_58") (pintype "bidirectional"))
      (node (ref "X-NORTH") (pin "23") (pinfunction "23_23") (pintype "bidirectional"))
    )
    (net (code "89") (name "N03_P") (class "Default")
      (node (ref "U8") (pin "55") (pinfunction "AN24/RD1_55") (pintype "bidirectional"))
      (node (ref "X-NORTH") (pin "21") (pinfunction "21_21") (pintype "bidirectional"))
    )
    (net (code "90") (name "N04_N") (class "Default")
      (node (ref "U4") (pin "17") (pinfunction "AN6/RF1_17") (pintype "bidirectional"))
      (node (ref "X-NORTH") (pin "28") (pinfunction "28_28") (pintype "bidirectional"))
    )
    (net (code "91") (name "N04_P") (class "Default")
      (node (ref "U4") (pin "21") (pinfunction "RA3/AN3/REF+_21") (pintype "bidirectional"))
      (node (ref "X-NORTH") (pin "26") (pinfunction "26_26") (pintype "bidirectional"))
    )
    (net (code "92") (name "N05_N") (class "Default")
      (node (ref "U8") (pin "64") (pinfunction "AN29/RE2_64") (pintype "bidirectional"))
      (node (ref "X-NORTH") (pin "29") (pinfunction "29_29") (pintype "bidirectional"))
    )
    (net (code "93") (name "N05_P") (class "Default")
      (node (ref "U8") (pin "48") (pinfunction "RB0/AN17_48") (pintype "bidirectional"))
      (node (ref "X-NORTH") (pin "27") (pinfunction "27_27") (pintype "bidirectional"))
    )
    (net (code "94") (name "N06_N") (class "Default")
      (node (ref "U4") (pin "44") (pinfunction "RB4/AN21_44") (pintype "bidirectional"))
      (node (ref "X-NORTH") (pin "34") (pinfunction "34_34") (pintype "bidirectional"))
    )
    (net (code "95") (name "N06_P") (class "Default")
      (node (ref "U4") (pin "43") (pinfunction "RB5/AN22_43") (pintype "bidirectional"))
      (node (ref "X-NORTH") (pin "32") (pinfunction "32_32") (pintype "bidirectional"))
    )
    (net (code "96") (name "N07_N") (class "Default")
      (node (ref "U8") (pin "46") (pinfunction "RB2/AN19_46") (pintype "bidirectional"))
      (node (ref "X-NORTH") (pin "35") (pinfunction "35_35") (pintype "bidirectional"))
    )
    (net (code "97") (name "N07_P") (class "Default")
      (node (ref "U8") (pin "47") (pinfunction "RB1/AN18_47") (pintype "bidirectional"))
      (node (ref "X-NORTH") (pin "33") (pinfunction "33_33") (pintype "bidirectional"))
    )
    (net (code "98") (name "N08_N") (class "Default")
      (node (ref "U4") (pin "46") (pinfunction "RB2/AN19_46") (pintype "bidirectional"))
      (node (ref "X-NORTH") (pin "40") (pinfunction "40_40") (pintype "bidirectional"))
    )
    (net (code "99") (name "N08_P") (class "Default")
      (node (ref "U4") (pin "45") (pinfunction "RB3/AN20_45") (pintype "bidirectional"))
      (node (ref "X-NORTH") (pin "38") (pinfunction "38_38") (pintype "bidirectional"))
    )
    (net (code "100") (name "N09_N") (class "Default")
      (node (ref "U8") (pin "44") (pinfunction "RB4/AN21_44") (pintype "bidirectional"))
      (node (ref "X-NORTH") (pin "41") (pinfunction "41_41") (pintype "bidirectional"))
    )
    (net (code "101") (name "N09_P") (class "Default")
      (node (ref "U8") (pin "45") (pinfunction "RB3/AN20_45") (pintype "bidirectional"))
      (node (ref "X-NORTH") (pin "39") (pinfunction "39_39") (pintype "bidirectional"))
    )
    (net (code "102") (name "N10_N") (class "Default")
      (node (ref "U4") (pin "15") (pinfunction "AN8/RF3_15") (pintype "bidirectional"))
      (node (ref "X-NORTH") (pin "46") (pinfunction "46_46") (pintype "bidirectional"))
    )
    (net (code "103") (name "N10_P") (class "Default")
      (node (ref "U4") (pin "16") (pinfunction "AN7/RF2_16") (pintype "bidirectional"))
      (node (ref "X-NORTH") (pin "44") (pinfunction "44_44") (pintype "bidirectional"))
    )
    (net (code "104") (name "N11_N") (class "Default")
      (node (ref "U8") (pin "2") (pinfunction "AN27/RE0_2") (pintype "bidirectional"))
      (node (ref "X-NORTH") (pin "47") (pinfunction "47_47") (pintype "bidirectional"))
    )
    (net (code "105") (name "N11_P") (class "Default")
      (node (ref "U8") (pin "1") (pinfunction "AN28/RE1_1") (pintype "bidirectional"))
      (node (ref "X-NORTH") (pin "45") (pinfunction "45_45") (pintype "bidirectional"))
    )
    (net (code "106") (name "N12_N") (class "Default")
      (node (ref "U4") (pin "13") (pinfunction "AN10/RF5_13") (pintype "bidirectional"))
      (node (ref "X-NORTH") (pin "52") (pinfunction "52_52") (pintype "bidirectional"))
    )
    (net (code "107") (name "N12_P") (class "Default")
      (node (ref "U4") (pin "14") (pinfunction "AN9/RF4_14") (pintype "bidirectional"))
      (node (ref "X-NORTH") (pin "50") (pinfunction "50_50") (pintype "bidirectional"))
    )
    (net (code "108") (name "N13_N") (class "Default")
      (node (ref "U8") (pin "13") (pinfunction "AN10/RF5_13") (pintype "bidirectional"))
      (node (ref "X-NORTH") (pin "53") (pinfunction "53_53") (pintype "bidirectional"))
    )
    (net (code "109") (name "N13_P") (class "Default")
      (node (ref "U8") (pin "12") (pinfunction "AN11/RF6_12") (pintype "bidirectional"))
      (node (ref "X-NORTH") (pin "51") (pinfunction "51_51") (pintype "bidirectional"))
    )
    (net (code "110") (name "N14_N") (class "Default")
      (node (ref "U4") (pin "2") (pinfunction "AN27/RE0_2") (pintype "bidirectional"))
      (node (ref "X-NORTH") (pin "58") (pinfunction "58_58") (pintype "bidirectional"))
    )
    (net (code "111") (name "N14_P") (class "Default")
      (node (ref "U4") (pin "12") (pinfunction "AN11/RF6_12") (pintype "bidirectional"))
      (node (ref "X-NORTH") (pin "56") (pinfunction "56_56") (pintype "bidirectional"))
    )
    (net (code "112") (name "N15_N") (class "Default")
      (node (ref "U8") (pin "15") (pinfunction "AN8/RF3_15") (pintype "bidirectional"))
      (node (ref "X-NORTH") (pin "59") (pinfunction "59_59") (pintype "bidirectional"))
    )
    (net (code "113") (name "N15_P") (class "Default")
      (node (ref "U8") (pin "14") (pinfunction "AN9/RF4_14") (pintype "bidirectional"))
      (node (ref "X-NORTH") (pin "57") (pinfunction "57_57") (pintype "bidirectional"))
    )
    (net (code "114") (name "N16_N") (class "Default")
      (node (ref "U4") (pin "64") (pinfunction "AN29/RE2_64") (pintype "bidirectional"))
      (node (ref "X-NORTH") (pin "64") (pinfunction "64_64") (pintype "bidirectional"))
    )
    (net (code "115") (name "N16_P") (class "Default")
      (node (ref "U4") (pin "1") (pinfunction "AN28/RE1_1") (pintype "bidirectional"))
      (node (ref "X-NORTH") (pin "62") (pinfunction "62_62") (pintype "bidirectional"))
    )
    (net (code "116") (name "N17_N") (class "Default")
      (node (ref "U8") (pin "17") (pinfunction "AN6/RF1_17") (pintype "bidirectional"))
      (node (ref "X-NORTH") (pin "65") (pinfunction "65_65") (pintype "bidirectional"))
    )
    (net (code "117") (name "N17_P") (class "Default")
      (node (ref "U8") (pin "16") (pinfunction "AN7/RF2_16") (pintype "bidirectional"))
      (node (ref "X-NORTH") (pin "63") (pinfunction "63_63") (pintype "bidirectional"))
    )
    (net (code "118") (name "N18_N") (class "Default")
      (node (ref "U4") (pin "48") (pinfunction "RB0/AN17_48") (pintype "bidirectional"))
      (node (ref "X-NORTH") (pin "70") (pinfunction "70_70") (pintype "bidirectional"))
    )
    (net (code "119") (name "N18_P") (class "Default")
      (node (ref "U4") (pin "47") (pinfunction "RB1/AN18_47") (pintype "bidirectional"))
      (node (ref "X-NORTH") (pin "68") (pinfunction "68_68") (pintype "bidirectional"))
    )
    (net (code "120") (name "N19_N") (class "Default")
      (node (ref "U8") (pin "27") (pinfunction "RA5/AN4_27") (pintype "bidirectional"))
      (node (ref "X-NORTH") (pin "71") (pinfunction "71_71") (pintype "bidirectional"))
    )
    (net (code "121") (name "N19_P") (class "Default")
      (node (ref "U8") (pin "43") (pinfunction "RB5/AN22_43") (pintype "bidirectional"))
      (node (ref "X-NORTH") (pin "69") (pinfunction "69_69") (pintype "bidirectional"))
    )
    (net (code "122") (name "N20_N") (class "Default")
      (node (ref "U1") (pin "43") (pinfunction "RB5/AN22_43") (pintype "bidirectional"))
      (node (ref "X-NORTH") (pin "76") (pinfunction "76_76") (pintype "bidirectional"))
    )
    (net (code "123") (name "N20_P") (class "Default")
      (node (ref "U1") (pin "27") (pinfunction "RA5/AN4_27") (pintype "bidirectional"))
      (node (ref "X-NORTH") (pin "74") (pinfunction "74_74") (pintype "bidirectional"))
    )
    (net (code "124") (name "N21_N") (class "Default")
      (node (ref "U7") (pin "47") (pinfunction "RB1/AN18_47") (pintype "bidirectional"))
      (node (ref "X-NORTH") (pin "77") (pinfunction "77_77") (pintype "bidirectional"))
    )
    (net (code "125") (name "N21_P") (class "Default")
      (node (ref "U7") (pin "48") (pinfunction "RB0/AN17_48") (pintype "bidirectional"))
      (node (ref "X-NORTH") (pin "75") (pinfunction "75_75") (pintype "bidirectional"))
    )
    (net (code "126") (name "N22_N") (class "Default")
      (node (ref "U1") (pin "16") (pinfunction "AN7/RF2_16") (pintype "bidirectional"))
      (node (ref "X-NORTH") (pin "82") (pinfunction "82_82") (pintype "bidirectional"))
    )
    (net (code "127") (name "N22_P") (class "Default")
      (node (ref "U1") (pin "17") (pinfunction "AN6/RF1_17") (pintype "bidirectional"))
      (node (ref "X-NORTH") (pin "80") (pinfunction "80_80") (pintype "bidirectional"))
    )
    (net (code "128") (name "N23_N") (class "Default")
      (node (ref "U7") (pin "1") (pinfunction "AN28/RE1_1") (pintype "bidirectional"))
      (node (ref "X-NORTH") (pin "83") (pinfunction "83_83") (pintype "bidirectional"))
    )
    (net (code "129") (name "N23_P") (class "Default")
      (node (ref "U7") (pin "64") (pinfunction "AN29/RE2_64") (pintype "bidirectional"))
      (node (ref "X-NORTH") (pin "81") (pinfunction "81_81") (pintype "bidirectional"))
    )
    (net (code "130") (name "N24_N") (class "Default")
      (node (ref "U1") (pin "14") (pinfunction "AN9/RF4_14") (pintype "bidirectional"))
      (node (ref "X-NORTH") (pin "88") (pinfunction "88_88") (pintype "bidirectional"))
    )
    (net (code "131") (name "N24_P") (class "Default")
      (node (ref "U1") (pin "15") (pinfunction "AN8/RF3_15") (pintype "bidirectional"))
      (node (ref "X-NORTH") (pin "86") (pinfunction "86_86") (pintype "bidirectional"))
    )
    (net (code "132") (name "N25_N") (class "Default")
      (node (ref "U7") (pin "12") (pinfunction "AN11/RF6_12") (pintype "bidirectional"))
      (node (ref "X-NORTH") (pin "89") (pinfunction "89_89") (pintype "bidirectional"))
    )
    (net (code "133") (name "N25_P") (class "Default")
      (node (ref "U7") (pin "2") (pinfunction "AN27/RE0_2") (pintype "bidirectional"))
      (node (ref "X-NORTH") (pin "87") (pinfunction "87_87") (pintype "bidirectional"))
    )
    (net (code "134") (name "N26_N") (class "Default")
      (node (ref "U1") (pin "12") (pinfunction "AN11/RF6_12") (pintype "bidirectional"))
      (node (ref "X-NORTH") (pin "94") (pinfunction "94_94") (pintype "bidirectional"))
    )
    (net (code "135") (name "N26_P") (class "Default")
      (node (ref "U1") (pin "13") (pinfunction "AN10/RF5_13") (pintype "bidirectional"))
      (node (ref "X-NORTH") (pin "92") (pinfunction "92_92") (pintype "bidirectional"))
    )
    (net (code "136") (name "N27_N") (class "Default")
      (node (ref "U7") (pin "14") (pinfunction "AN9/RF4_14") (pintype "bidirectional"))
      (node (ref "X-NORTH") (pin "95") (pinfunction "95_95") (pintype "bidirectional"))
    )
    (net (code "137") (name "N27_P") (class "Default")
      (node (ref "U7") (pin "13") (pinfunction "AN10/RF5_13") (pintype "bidirectional"))
      (node (ref "X-NORTH") (pin "93") (pinfunction "93_93") (pintype "bidirectional"))
    )
    (net (code "138") (name "N28_N") (class "Default")
      (node (ref "U1") (pin "1") (pinfunction "AN28/RE1_1") (pintype "bidirectional"))
      (node (ref "X-NORTH") (pin "100") (pinfunction "100_100") (pintype "bidirectional"))
    )
    (net (code "139") (name "N28_P") (class "Default")
      (node (ref "U1") (pin "2") (pinfunction "AN27/RE0_2") (pintype "bidirectional"))
      (node (ref "X-NORTH") (pin "98") (pinfunction "98_98") (pintype "bidirectional"))
    )
    (net (code "140") (name "N29_N") (class "Default")
      (node (ref "U7") (pin "16") (pinfunction "AN7/RF2_16") (pintype "bidirectional"))
      (node (ref "X-NORTH") (pin "101") (pinfunction "101_101") (pintype "bidirectional"))
    )
    (net (code "141") (name "N29_P") (class "Default")
      (node (ref "U7") (pin "15") (pinfunction "AN8/RF3_15") (pintype "bidirectional"))
      (node (ref "X-NORTH") (pin "99") (pinfunction "99_99") (pintype "bidirectional"))
    )
    (net (code "142") (name "N30_N") (class "Default")
      (node (ref "U1") (pin "45") (pinfunction "RB3/AN20_45") (pintype "bidirectional"))
      (node (ref "X-NORTH") (pin "106") (pinfunction "106_106") (pintype "bidirectional"))
    )
    (net (code "143") (name "N30_P") (class "Default")
      (node (ref "U1") (pin "44") (pinfunction "RB4/AN21_44") (pintype "bidirectional"))
      (node (ref "X-NORTH") (pin "104") (pinfunction "104_104") (pintype "bidirectional"))
    )
    (net (code "144") (name "N31_N") (class "Default")
      (node (ref "U7") (pin "45") (pinfunction "RB3/AN20_45") (pintype "bidirectional"))
      (node (ref "X-NORTH") (pin "107") (pinfunction "107_107") (pintype "bidirectional"))
    )
    (net (code "145") (name "N31_P") (class "Default")
      (node (ref "U7") (pin "46") (pinfunction "RB2/AN19_46") (pintype "bidirectional"))
      (node (ref "X-NORTH") (pin "105") (pinfunction "105_105") (pintype "bidirectional"))
    )
    (net (code "146") (name "N32_N") (class "Default")
      (node (ref "U1") (pin "47") (pinfunction "RB1/AN18_47") (pintype "bidirectional"))
      (node (ref "X-NORTH") (pin "112") (pinfunction "112_112") (pintype "bidirectional"))
    )
    (net (code "147") (name "N32_P") (class "Default")
      (node (ref "U1") (pin "46") (pinfunction "RB2/AN19_46") (pintype "bidirectional"))
      (node (ref "X-NORTH") (pin "110") (pinfunction "110_110") (pintype "bidirectional"))
    )
    (net (code "148") (name "N33_N") (class "Default")
      (node (ref "U7") (pin "43") (pinfunction "RB5/AN22_43") (pintype "bidirectional"))
      (node (ref "X-NORTH") (pin "113") (pinfunction "113_113") (pintype "bidirectional"))
    )
    (net (code "149") (name "N33_P") (class "Default")
      (node (ref "U7") (pin "44") (pinfunction "RB4/AN21_44") (pintype "bidirectional"))
      (node (ref "X-NORTH") (pin "111") (pinfunction "111_111") (pintype "bidirectional"))
    )
    (net (code "150") (name "N34_N") (class "Default")
      (node (ref "U1") (pin "48") (pinfunction "RB0/AN17_48") (pintype "bidirectional"))
      (node (ref "X-NORTH") (pin "118") (pinfunction "118_118") (pintype "bidirectional"))
    )
    (net (code "151") (name "N34_P") (class "Default")
      (node (ref "U1") (pin "64") (pinfunction "AN29/RE2_64") (pintype "bidirectional"))
      (node (ref "X-NORTH") (pin "116") (pinfunction "116_116") (pintype "bidirectional"))
    )
    (net (code "152") (name "N35_N") (class "Default")
      (node (ref "U7") (pin "21") (pinfunction "RA3/AN3/REF+_21") (pintype "bidirectional"))
      (node (ref "X-NORTH") (pin "119") (pinfunction "119_119") (pintype "bidirectional"))
    )
    (net (code "153") (name "N35_P") (class "Default")
      (node (ref "U7") (pin "17") (pinfunction "AN6/RF1_17") (pintype "bidirectional"))
      (node (ref "X-NORTH") (pin "117") (pinfunction "117_117") (pintype "bidirectional"))
    )
    (net (code "154") (name "N36_N") (class "Default")
      (node (ref "U1") (pin "55") (pinfunction "AN24/RD1_55") (pintype "bidirectional"))
      (node (ref "X-NORTH") (pin "124") (pinfunction "124_124") (pintype "bidirectional"))
    )
    (net (code "155") (name "N36_P") (class "Default")
      (node (ref "U1") (pin "58") (pinfunction "AN23/RD0_58") (pintype "bidirectional"))
      (node (ref "X-NORTH") (pin "122") (pinfunction "122_122") (pintype "bidirectional"))
    )
    (net (code "156") (name "N37_N") (class "Default")
      (node (ref "U7") (pin "23") (pinfunction "RA1/AN1_23") (pintype "bidirectional"))
      (node (ref "X-NORTH") (pin "125") (pinfunction "125_125") (pintype "bidirectional"))
    )
    (net (code "157") (name "N37_P") (class "Default")
      (node (ref "U7") (pin "22") (pinfunction "RA2/AN2_22") (pintype "bidirectional"))
      (node (ref "X-NORTH") (pin "123") (pinfunction "123_123") (pintype "bidirectional"))
    )
    (net (code "158") (name "N38_N") (class "Default")
      (node (ref "U1") (pin "53") (pinfunction "AN26/RD3_53") (pintype "bidirectional"))
      (node (ref "X-NORTH") (pin "130") (pinfunction "130_130") (pintype "bidirectional"))
    )
    (net (code "159") (name "N38_P") (class "Default")
      (node (ref "U1") (pin "54") (pinfunction "AN25/RD2_54") (pintype "bidirectional"))
      (node (ref "X-NORTH") (pin "128") (pinfunction "128_128") (pintype "bidirectional"))
    )
    (net (code "160") (name "N39_N") (class "Default")
      (node (ref "U7") (pin "27") (pinfunction "RA5/AN4_27") (pintype "bidirectional"))
      (node (ref "X-NORTH") (pin "131") (pinfunction "131_131") (pintype "bidirectional"))
    )
    (net (code "161") (name "N39_P") (class "Default")
      (node (ref "U7") (pin "24") (pinfunction "RA0/AN0_24") (pintype "bidirectional"))
      (node (ref "X-NORTH") (pin "129") (pinfunction "129_129") (pintype "bidirectional"))
    )
    (net (code "162") (name "N_CHK_EN") (class "Default")
      (node (ref "U4") (pin "29") (pinfunction "RC1_29") (pintype "bidirectional"))
      (node (ref "X-NORTH") (pin "8") (pinfunction "8_8") (pintype "bidirectional"))
    )
    (net (code "163") (name "N_CHK_V") (class "Default")
      (node (ref "C141") (pin "1") (pinfunction "1_1") (pintype "passive"))
      (node (ref "C142") (pin "1") (pinfunction "1_1") (pintype "passive"))
      (node (ref "PWRN") (pin "2") (pinfunction "2_2") (pintype "passive"))
      (node (ref "R21") (pin "1") (pinfunction "1_1") (pintype "passive"))
      (node (ref "R22") (pin "1") (pinfunction "1_1") (pintype "passive"))
      (node (ref "U11") (pin "1") (pinfunction "VDD_1") (pintype "power_in"))
      (node (ref "X-NORTH") (pin "10") (pinfunction "10_10") (pintype "bidirectional"))
    )
    (net (code "164") (name "N_I2C_EN") (class "Default")
      (node (ref "U7") (pin "28") (pinfunction "RA4_28") (pintype "bidirectional"))
      (node (ref "X-NORTH") (pin "137") (pinfunction "137_137") (pintype "bidirectional"))
    )
    (net (code "165") (name "N_I2C_V") (class "Default")
      (node (ref "X-NORTH") (pin "135") (pinfunction "135_135") (pintype "bidirectional"))
    )
    (net (code "166") (name "N_SCK") (class "Default")
      (node (ref "U1") (pin "50") (pinfunction "SCK2/RD6_50") (pintype "bidirectional"))
      (node (ref "X-NORTH") (pin "144") (pinfunction "144_144") (pintype "bidirectional"))
    )
    (net (code "167") (name "N_SCL") (class "Default")
      (node (ref "R2") (pin "2") (pinfunction "2_2") (pintype "passive"))
      (node (ref "U7") (pin "50") (pinfunction "SCK2/RD6_50") (pintype "bidirectional"))
      (node (ref "X-NORTH") (pin "143") (pinfunction "143_143") (pintype "bidirectional"))
    )
    (net (code "168") (name "N_SDA") (class "Default")
      (node (ref "R1") (pin "2") (pinfunction "2_2") (pintype "passive"))
      (node (ref "U7") (pin "51") (pinfunction "SDI2/RD5_51") (pintype "bidirectional"))
      (node (ref "X-NORTH") (pin "141") (pinfunction "141_141") (pintype "bidirectional"))
    )
    (net (code "169") (name "N_SDI") (class "Default")
      (node (ref "U1") (pin "51") (pinfunction "SDI2/RD5_51") (pintype "bidirectional"))
      (node (ref "X-NORTH") (pin "140") (pinfunction "140_140") (pintype "bidirectional"))
    )
    (net (code "170") (name "N_SDO") (class "Default")
      (node (ref "U1") (pin "52") (pinfunction "SDO2/RD4_52") (pintype "bidirectional"))
      (node (ref "X-NORTH") (pin "142") (pinfunction "142_142") (pintype "bidirectional"))
    )
    (net (code "171") (name "N_SPI_EN") (class "Default")
      (node (ref "U1") (pin "49") (pinfunction "~{SS2}/RD7_49") (pintype "bidirectional"))
      (node (ref "X-NORTH") (pin "136") (pinfunction "136_136") (pintype "bidirectional"))
    )
    (net (code "172") (name "N_SPI_V") (class "Default")
      (node (ref "X-NORTH") (pin "134") (pinfunction "134_134") (pintype "bidirectional"))
    )
    (net (code "173") (name "N_VE") (class "Default")
      (node (ref "C140") (pin "1") (pinfunction "1_1") (pintype "passive"))
      (node (ref "PWR-NORTH") (pin "2") (pinfunction "2_2") (pintype "passive"))
      (node (ref "X-NORTH") (pin "109") (pinfunction "109_109") (pintype "bidirectional"))
      (node (ref "X-NORTH") (pin "115") (pinfunction "115_115") (pintype "bidirectional"))
      (node (ref "X-NORTH") (pin "127") (pinfunction "127_127") (pintype "bidirectional"))
      (node (ref "X-NORTH") (pin "133") (pinfunction "133_133") (pintype "bidirectional"))
    )
    (net (code "174") (name "N_VE_CV") (class "Default")
      (node (ref "U11") (pin "7") (pinfunction "VOUTB_7") (pintype "output"))
      (node (ref "X-NORTH") (pin "6") (pinfunction "6_6") (pintype "bidirectional"))
    )
    (net (code "175") (name "N_VE_OV") (class "Default")
      (node (ref "U8") (pin "51") (pinfunction "SDI2/RD5_51") (pintype "bidirectional"))
      (node (ref "X-NORTH") (pin "5") (pinfunction "5_5") (pintype "bidirectional"))
    )
    (net (code "176") (name "N_VE_RS") (class "Default")
      (node (ref "X-NORTH") (pin "121") (pinfunction "121_121") (pintype "bidirectional"))
    )
    (net (code "177") (name "N_VE_UV") (class "Default")
      (node (ref "U8") (pin "61") (pinfunction "RE5_61") (pintype "bidirectional"))
      (node (ref "X-NORTH") (pin "11") (pinfunction "11_11") (pintype "bidirectional"))
    )
    (net (code "178") (name "N_VN") (class "Default")
      (node (ref "C139") (pin "1") (pinfunction "1_1") (pintype "passive"))
      (node (ref "PWR-NORTH") (pin "4") (pinfunction "4_4") (pintype "passive"))
      (node (ref "X-NORTH") (pin "49") (pinfunction "49_49") (pintype "bidirectional"))
      (node (ref "X-NORTH") (pin "55") (pinfunction "55_55") (pintype "bidirectional"))
      (node (ref "X-NORTH") (pin "61") (pinfunction "61_61") (pintype "bidirectional"))
      (node (ref "X-NORTH") (pin "67") (pinfunction "67_67") (pintype "bidirectional"))
      (node (ref "X-NORTH") (pin "79") (pinfunction "79_79") (pintype "bidirectional"))
      (node (ref "X-NORTH") (pin "85") (pinfunction "85_85") (pintype "bidirectional"))
      (node (ref "X-NORTH") (pin "91") (pinfunction "91_91") (pintype "bidirectional"))
      (node (ref "X-NORTH") (pin "97") (pinfunction "97_97") (pintype "bidirectional"))
    )
    (net (code "179") (name "N_VN_CV") (class "Default")
      (node (ref "U11") (pin "8") (pinfunction "VOUTC_8") (pintype "output"))
      (node (ref "X-NORTH") (pin "4") (pinfunction "4_4") (pintype "bidirectional"))
    )
    (net (code "180") (name "N_VN_OV") (class "Default")
      (node (ref "U8") (pin "50") (pinfunction "SCK2/RD6_50") (pintype "bidirectional"))
      (node (ref "X-NORTH") (pin "3") (pinfunction "3_3") (pintype "bidirectional"))
    )
    (net (code "181") (name "N_VN_RS") (class "Default")
      (node (ref "X-NORTH") (pin "73") (pinfunction "73_73") (pintype "bidirectional"))
    )
    (net (code "182") (name "N_VN_UV") (class "Default")
      (node (ref "U8") (pin "60") (pinfunction "RE6_60") (pintype "bidirectional"))
      (node (ref "X-NORTH") (pin "9") (pinfunction "9_9") (pintype "bidirectional"))
    )
    (net (code "183") (name "N_VW") (class "Default")
      (node (ref "C138") (pin "1") (pinfunction "1_1") (pintype "passive"))
      (node (ref "PWR-NORTH") (pin "6") (pinfunction "6_6") (pintype "passive"))
      (node (ref "X-NORTH") (pin "13") (pinfunction "13_13") (pintype "bidirectional"))
      (node (ref "X-NORTH") (pin "19") (pinfunction "19_19") (pintype "bidirectional"))
      (node (ref "X-NORTH") (pin "31") (pinfunction "31_31") (pintype "bidirectional"))
      (node (ref "X-NORTH") (pin "37") (pinfunction "37_37") (pintype "bidirectional"))
    )
    (net (code "184") (name "N_VW_CV") (class "Default")
      (node (ref "U11") (pin "9") (pinfunction "VOUTD_9") (pintype "output"))
      (node (ref "X-NORTH") (pin "2") (pinfunction "2_2") (pintype "bidirectional"))
    )
    (net (code "185") (name "N_VW_OV") (class "Default")
      (node (ref "U8") (pin "49") (pinfunction "~{SS2}/RD7_49") (pintype "bidirectional"))
      (node (ref "X-NORTH") (pin "1") (pinfunction "1_1") (pintype "bidirectional"))
    )
    (net (code "186") (name "N_VW_RS") (class "Default")
      (node (ref "X-NORTH") (pin "25") (pinfunction "25_25") (pintype "bidirectional"))
    )
    (net (code "187") (name "N_VW_UV") (class "Default")
      (node (ref "U8") (pin "59") (pinfunction "RE7_59") (pintype "bidirectional"))
      (node (ref "X-NORTH") (pin "7") (pinfunction "7_7") (pintype "bidirectional"))
    )
    (net (code "188") (name "Net-(LED1A-A)") (class "Default")
      (node (ref "LED1") (pin "1") (pinfunction "A_1") (pintype "passive"))
      (node (ref "R13") (pin "2") (pinfunction "2_2") (pintype "passive"))
    )
    (net (code "189") (name "Net-(LED1B-A)") (class "Default")
      (node (ref "LED1") (pin "2") (pinfunction "A_2") (pintype "passive"))
      (node (ref "R14") (pin "2") (pinfunction "2_2") (pintype "passive"))
    )
    (net (code "190") (name "Net-(LED2A-A)") (class "Default")
      (node (ref "LED2") (pin "1") (pinfunction "A_1") (pintype "passive"))
      (node (ref "R15") (pin "2") (pinfunction "2_2") (pintype "passive"))
    )
    (net (code "191") (name "Net-(LED2B-A)") (class "Default")
      (node (ref "LED2") (pin "2") (pinfunction "A_2") (pintype "passive"))
      (node (ref "R16") (pin "2") (pinfunction "2_2") (pintype "passive"))
    )
    (net (code "192") (name "Net-(LED3A-A)") (class "Default")
      (node (ref "LED3") (pin "1") (pinfunction "A_1") (pintype "passive"))
      (node (ref "R17") (pin "2") (pinfunction "2_2") (pintype "passive"))
    )
    (net (code "193") (name "Net-(LED3B-A)") (class "Default")
      (node (ref "LED3") (pin "2") (pinfunction "A_2") (pintype "passive"))
      (node (ref "R18") (pin "2") (pinfunction "2_2") (pintype "passive"))
    )
    (net (code "194") (name "Net-(LED4A-A)") (class "Default")
      (node (ref "LED4") (pin "1") (pinfunction "A_1") (pintype "passive"))
      (node (ref "R19") (pin "2") (pinfunction "2_2") (pintype "passive"))
    )
    (net (code "195") (name "Net-(LED4B-A)") (class "Default")
      (node (ref "LED4") (pin "2") (pinfunction "A_2") (pintype "passive"))
      (node (ref "R20") (pin "2") (pinfunction "2_2") (pintype "passive"))
    )
    (net (code "196") (name "Net-(U1-AN16{slash}RF0)") (class "Default")
      (node (ref "C1") (pin "1") (pinfunction "1_1") (pintype "passive"))
      (node (ref "U1") (pin "18") (pinfunction "AN16/RF0_18") (pintype "bidirectional"))
    )
    (net (code "197") (name "Net-(U2-AN16{slash}RF0)") (class "Default")
      (node (ref "C12") (pin "1") (pinfunction "1_1") (pintype "passive"))
      (node (ref "U2") (pin "18") (pinfunction "AN16/RF0_18") (pintype "bidirectional"))
    )
    (net (code "198") (name "Net-(U3-AN16{slash}RF0)") (class "Default")
      (node (ref "C23") (pin "1") (pinfunction "1_1") (pintype "passive"))
      (node (ref "U3") (pin "18") (pinfunction "AN16/RF0_18") (pintype "bidirectional"))
    )
    (net (code "199") (name "Net-(U4-AN16{slash}RF0)") (class "Default")
      (node (ref "C34") (pin "1") (pinfunction "1_1") (pintype "passive"))
      (node (ref "U4") (pin "18") (pinfunction "AN16/RF0_18") (pintype "bidirectional"))
    )
    (net (code "200") (name "Net-(U5-AN16{slash}RF0)") (class "Default")
      (node (ref "C45") (pin "1") (pinfunction "1_1") (pintype "passive"))
      (node (ref "U5") (pin "18") (pinfunction "AN16/RF0_18") (pintype "bidirectional"))
    )
    (net (code "201") (name "Net-(U6-AN16{slash}RF0)") (class "Default")
      (node (ref "C56") (pin "1") (pinfunction "1_1") (pintype "passive"))
      (node (ref "U6") (pin "18") (pinfunction "AN16/RF0_18") (pintype "bidirectional"))
    )
    (net (code "202") (name "Net-(U7-AN16{slash}RF0)") (class "Default")
      (node (ref "C67") (pin "1") (pinfunction "1_1") (pintype "passive"))
      (node (ref "U7") (pin "18") (pinfunction "AN16/RF0_18") (pintype "bidirectional"))
    )
    (net (code "203") (name "Net-(U8-AN16{slash}RF0)") (class "Default")
      (node (ref "C78") (pin "1") (pinfunction "1_1") (pintype "passive"))
      (node (ref "U8") (pin "18") (pinfunction "AN16/RF0_18") (pintype "bidirectional"))
    )
    (net (code "204") (name "Net-(U10-OUT)") (class "Default")
      (node (ref "U10") (pin "3") (pinfunction "OUT_3") (pintype "bidirectional"))
      (node (ref "U9") (pin "1") (pinfunction "CLK_1") (pintype "input"))
    )
    (net (code "205") (name "Net-(U11-VOUTA)") (class "Default")
      (node (ref "TPN") (pin "TP") (pinfunction "TP_TP") (pintype "input"))
      (node (ref "U11") (pin "6") (pinfunction "VOUTA_6") (pintype "output"))
    )
    (net (code "206") (name "Net-(U12-VOUTA)") (class "Default")
      (node (ref "TPS") (pin "TP") (pinfunction "TP_TP") (pintype "input"))
      (node (ref "U12") (pin "6") (pinfunction "VOUTA_6") (pintype "output"))
    )
    (net (code "207") (name "RX1") (class "Default")
      (node (ref "SER1") (pin "3") (pinfunction "3_3") (pintype "passive"))
      (node (ref "U1") (pin "32") (pinfunction "RC7/RX1_32") (pintype "bidirectional"))
    )
    (net (code "208") (name "RX1B") (class "Default")
      (node (ref "U1") (pin "5") (pinfunction "RX2/AN14/RG2_5") (pintype "bidirectional"))
    )
    (net (code "209") (name "RX2") (class "Default")
      (node (ref "SER2") (pin "3") (pinfunction "3_3") (pintype "passive"))
      (node (ref "U2") (pin "32") (pinfunction "RC7/RX1_32") (pintype "bidirectional"))
    )
    (net (code "210") (name "RX2B") (class "Default")
      (node (ref "U2") (pin "5") (pinfunction "RX2/AN14/RG2_5") (pintype "bidirectional"))
    )
    (net (code "211") (name "RX3") (class "Default")
      (node (ref "SER3") (pin "3") (pinfunction "3_3") (pintype "passive"))
      (node (ref "U3") (pin "32") (pinfunction "RC7/RX1_32") (pintype "bidirectional"))
    )
    (net (code "212") (name "RX3B") (class "Default")
      (node (ref "U3") (pin "5") (pinfunction "RX2/AN14/RG2_5") (pintype "bidirectional"))
    )
    (net (code "213") (name "RX4") (class "Default")
      (node (ref "SER4") (pin "3") (pinfunction "3_3") (pintype "passive"))
      (node (ref "U4") (pin "32") (pinfunction "RC7/RX1_32") (pintype "bidirectional"))
    )
    (net (code "214") (name "RX4B") (class "Default")
      (node (ref "U4") (pin "5") (pinfunction "RX2/AN14/RG2_5") (pintype "bidirectional"))
    )
    (net (code "215") (name "RX5") (class "Default")
      (node (ref "SER5") (pin "3") (pinfunction "3_3") (pintype "passive"))
      (node (ref "U5") (pin "32") (pinfunction "RC7/RX1_32") (pintype "bidirectional"))
    )
    (net (code "216") (name "RX5B") (class "Default")
      (node (ref "U5") (pin "5") (pinfunction "RX2/AN14/RG2_5") (pintype "bidirectional"))
    )
    (net (code "217") (name "RX6") (class "Default")
      (node (ref "SER6") (pin "3") (pinfunction "3_3") (pintype "passive"))
      (node (ref "U6") (pin "32") (pinfunction "RC7/RX1_32") (pintype "bidirectional"))
    )
    (net (code "218") (name "RX6B") (class "Default")
      (node (ref "U6") (pin "5") (pinfunction "RX2/AN14/RG2_5") (pintype "bidirectional"))
    )
    (net (code "219") (name "RX7") (class "Default")
      (node (ref "SER7") (pin "3") (pinfunction "3_3") (pintype "passive"))
      (node (ref "U7") (pin "32") (pinfunction "RC7/RX1_32") (pintype "bidirectional"))
    )
    (net (code "220") (name "RX7B") (class "Default")
      (node (ref "U7") (pin "5") (pinfunction "RX2/AN14/RG2_5") (pintype "bidirectional"))
    )
    (net (code "221") (name "RX8") (class "Default")
      (node (ref "SER8") (pin "3") (pinfunction "3_3") (pintype "passive"))
      (node (ref "U8") (pin "32") (pinfunction "RC7/RX1_32") (pintype "bidirectional"))
    )
    (net (code "222") (name "RX8B") (class "Default")
      (node (ref "U8") (pin "5") (pinfunction "RX2/AN14/RG2_5") (pintype "bidirectional"))
    )
    (net (code "223") (name "S00_N") (class "Default")
      (node (ref "U2") (pin "24") (pinfunction "RA0/AN0_24") (pintype "bidirectional"))
      (node (ref "X-SOUTH") (pin "16") (pinfunction "16_16") (pintype "bidirectional"))
    )
    (net (code "224") (name "S00_P") (class "Default")
      (node (ref "U2") (pin "27") (pinfunction "RA5/AN4_27") (pintype "bidirectional"))
      (node (ref "X-SOUTH") (pin "14") (pinfunction "14_14") (pintype "bidirectional"))
    )
    (net (code "225") (name "S01_N") (class "Default")
      (node (ref "U5") (pin "54") (pinfunction "AN25/RD2_54") (pintype "bidirectional"))
      (node (ref "X-SOUTH") (pin "17") (pinfunction "17_17") (pintype "bidirectional"))
    )
    (net (code "226") (name "S01_P") (class "Default")
      (node (ref "U5") (pin "53") (pinfunction "AN26/RD3_53") (pintype "bidirectional"))
      (node (ref "X-SOUTH") (pin "15") (pinfunction "15_15") (pintype "bidirectional"))
    )
    (net (code "227") (name "S02_N") (class "Default")
      (node (ref "U2") (pin "22") (pinfunction "RA2/AN2_22") (pintype "bidirectional"))
      (node (ref "X-SOUTH") (pin "22") (pinfunction "22_22") (pintype "bidirectional"))
    )
    (net (code "228") (name "S02_P") (class "Default")
      (node (ref "U2") (pin "23") (pinfunction "RA1/AN1_23") (pintype "bidirectional"))
      (node (ref "X-SOUTH") (pin "20") (pinfunction "20_20") (pintype "bidirectional"))
    )
    (net (code "229") (name "S03_N") (class "Default")
      (node (ref "U5") (pin "58") (pinfunction "AN23/RD0_58") (pintype "bidirectional"))
      (node (ref "X-SOUTH") (pin "23") (pinfunction "23_23") (pintype "bidirectional"))
    )
    (net (code "230") (name "S03_P") (class "Default")
      (node (ref "U5") (pin "55") (pinfunction "AN24/RD1_55") (pintype "bidirectional"))
      (node (ref "X-SOUTH") (pin "21") (pinfunction "21_21") (pintype "bidirectional"))
    )
    (net (code "231") (name "S04_N") (class "Default")
      (node (ref "U2") (pin "17") (pinfunction "AN6/RF1_17") (pintype "bidirectional"))
      (node (ref "X-SOUTH") (pin "28") (pinfunction "28_28") (pintype "bidirectional"))
    )
    (net (code "232") (name "S04_P") (class "Default")
      (node (ref "U2") (pin "21") (pinfunction "RA3/AN3/REF+_21") (pintype "bidirectional"))
      (node (ref "X-SOUTH") (pin "26") (pinfunction "26_26") (pintype "bidirectional"))
    )
    (net (code "233") (name "S05_N") (class "Default")
      (node (ref "U5") (pin "64") (pinfunction "AN29/RE2_64") (pintype "bidirectional"))
      (node (ref "X-SOUTH") (pin "29") (pinfunction "29_29") (pintype "bidirectional"))
    )
    (net (code "234") (name "S05_P") (class "Default")
      (node (ref "U5") (pin "48") (pinfunction "RB0/AN17_48") (pintype "bidirectional"))
      (node (ref "X-SOUTH") (pin "27") (pinfunction "27_27") (pintype "bidirectional"))
    )
    (net (code "235") (name "S06_N") (class "Default")
      (node (ref "U2") (pin "44") (pinfunction "RB4/AN21_44") (pintype "bidirectional"))
      (node (ref "X-SOUTH") (pin "34") (pinfunction "34_34") (pintype "bidirectional"))
    )
    (net (code "236") (name "S06_P") (class "Default")
      (node (ref "U2") (pin "43") (pinfunction "RB5/AN22_43") (pintype "bidirectional"))
      (node (ref "X-SOUTH") (pin "32") (pinfunction "32_32") (pintype "bidirectional"))
    )
    (net (code "237") (name "S07_N") (class "Default")
      (node (ref "U5") (pin "46") (pinfunction "RB2/AN19_46") (pintype "bidirectional"))
      (node (ref "X-SOUTH") (pin "35") (pinfunction "35_35") (pintype "bidirectional"))
    )
    (net (code "238") (name "S07_P") (class "Default")
      (node (ref "U5") (pin "47") (pinfunction "RB1/AN18_47") (pintype "bidirectional"))
      (node (ref "X-SOUTH") (pin "33") (pinfunction "33_33") (pintype "bidirectional"))
    )
    (net (code "239") (name "S08_N") (class "Default")
      (node (ref "U2") (pin "46") (pinfunction "RB2/AN19_46") (pintype "bidirectional"))
      (node (ref "X-SOUTH") (pin "40") (pinfunction "40_40") (pintype "bidirectional"))
    )
    (net (code "240") (name "S08_P") (class "Default")
      (node (ref "U2") (pin "45") (pinfunction "RB3/AN20_45") (pintype "bidirectional"))
      (node (ref "X-SOUTH") (pin "38") (pinfunction "38_38") (pintype "bidirectional"))
    )
    (net (code "241") (name "S09_N") (class "Default")
      (node (ref "U5") (pin "44") (pinfunction "RB4/AN21_44") (pintype "bidirectional"))
      (node (ref "X-SOUTH") (pin "41") (pinfunction "41_41") (pintype "bidirectional"))
    )
    (net (code "242") (name "S09_P") (class "Default")
      (node (ref "U5") (pin "45") (pinfunction "RB3/AN20_45") (pintype "bidirectional"))
      (node (ref "X-SOUTH") (pin "39") (pinfunction "39_39") (pintype "bidirectional"))
    )
    (net (code "243") (name "S10_N") (class "Default")
      (node (ref "U2") (pin "15") (pinfunction "AN8/RF3_15") (pintype "bidirectional"))
      (node (ref "X-SOUTH") (pin "46") (pinfunction "46_46") (pintype "bidirectional"))
    )
    (net (code "244") (name "S10_P") (class "Default")
      (node (ref "U2") (pin "16") (pinfunction "AN7/RF2_16") (pintype "bidirectional"))
      (node (ref "X-SOUTH") (pin "44") (pinfunction "44_44") (pintype "bidirectional"))
    )
    (net (code "245") (name "S11_N") (class "Default")
      (node (ref "U5") (pin "2") (pinfunction "AN27/RE0_2") (pintype "bidirectional"))
      (node (ref "X-SOUTH") (pin "47") (pinfunction "47_47") (pintype "bidirectional"))
    )
    (net (code "246") (name "S11_P") (class "Default")
      (node (ref "U5") (pin "1") (pinfunction "AN28/RE1_1") (pintype "bidirectional"))
      (node (ref "X-SOUTH") (pin "45") (pinfunction "45_45") (pintype "bidirectional"))
    )
    (net (code "247") (name "S12_N") (class "Default")
      (node (ref "U2") (pin "13") (pinfunction "AN10/RF5_13") (pintype "bidirectional"))
      (node (ref "X-SOUTH") (pin "52") (pinfunction "52_52") (pintype "bidirectional"))
    )
    (net (code "248") (name "S12_P") (class "Default")
      (node (ref "U2") (pin "14") (pinfunction "AN9/RF4_14") (pintype "bidirectional"))
      (node (ref "X-SOUTH") (pin "50") (pinfunction "50_50") (pintype "bidirectional"))
    )
    (net (code "249") (name "S13_N") (class "Default")
      (node (ref "U5") (pin "13") (pinfunction "AN10/RF5_13") (pintype "bidirectional"))
      (node (ref "X-SOUTH") (pin "53") (pinfunction "53_53") (pintype "bidirectional"))
    )
    (net (code "250") (name "S13_P") (class "Default")
      (node (ref "U5") (pin "12") (pinfunction "AN11/RF6_12") (pintype "bidirectional"))
      (node (ref "X-SOUTH") (pin "51") (pinfunction "51_51") (pintype "bidirectional"))
    )
    (net (code "251") (name "S14_N") (class "Default")
      (node (ref "U2") (pin "2") (pinfunction "AN27/RE0_2") (pintype "bidirectional"))
      (node (ref "X-SOUTH") (pin "58") (pinfunction "58_58") (pintype "bidirectional"))
    )
    (net (code "252") (name "S14_P") (class "Default")
      (node (ref "U2") (pin "12") (pinfunction "AN11/RF6_12") (pintype "bidirectional"))
      (node (ref "X-SOUTH") (pin "56") (pinfunction "56_56") (pintype "bidirectional"))
    )
    (net (code "253") (name "S15_N") (class "Default")
      (node (ref "U5") (pin "15") (pinfunction "AN8/RF3_15") (pintype "bidirectional"))
      (node (ref "X-SOUTH") (pin "59") (pinfunction "59_59") (pintype "bidirectional"))
    )
    (net (code "254") (name "S15_P") (class "Default")
      (node (ref "U5") (pin "14") (pinfunction "AN9/RF4_14") (pintype "bidirectional"))
      (node (ref "X-SOUTH") (pin "57") (pinfunction "57_57") (pintype "bidirectional"))
    )
    (net (code "255") (name "S16_N") (class "Default")
      (node (ref "U2") (pin "64") (pinfunction "AN29/RE2_64") (pintype "bidirectional"))
      (node (ref "X-SOUTH") (pin "64") (pinfunction "64_64") (pintype "bidirectional"))
    )
    (net (code "256") (name "S16_P") (class "Default")
      (node (ref "U2") (pin "1") (pinfunction "AN28/RE1_1") (pintype "bidirectional"))
      (node (ref "X-SOUTH") (pin "62") (pinfunction "62_62") (pintype "bidirectional"))
    )
    (net (code "257") (name "S17_N") (class "Default")
      (node (ref "U5") (pin "17") (pinfunction "AN6/RF1_17") (pintype "bidirectional"))
      (node (ref "X-SOUTH") (pin "65") (pinfunction "65_65") (pintype "bidirectional"))
    )
    (net (code "258") (name "S17_P") (class "Default")
      (node (ref "U5") (pin "16") (pinfunction "AN7/RF2_16") (pintype "bidirectional"))
      (node (ref "X-SOUTH") (pin "63") (pinfunction "63_63") (pintype "bidirectional"))
    )
    (net (code "259") (name "S18_N") (class "Default")
      (node (ref "U2") (pin "48") (pinfunction "RB0/AN17_48") (pintype "bidirectional"))
      (node (ref "X-SOUTH") (pin "70") (pinfunction "70_70") (pintype "bidirectional"))
    )
    (net (code "260") (name "S18_P") (class "Default")
      (node (ref "U2") (pin "47") (pinfunction "RB1/AN18_47") (pintype "bidirectional"))
      (node (ref "X-SOUTH") (pin "68") (pinfunction "68_68") (pintype "bidirectional"))
    )
    (net (code "261") (name "S19_N") (class "Default")
      (node (ref "U5") (pin "27") (pinfunction "RA5/AN4_27") (pintype "bidirectional"))
      (node (ref "X-SOUTH") (pin "71") (pinfunction "71_71") (pintype "bidirectional"))
    )
    (net (code "262") (name "S19_P") (class "Default")
      (node (ref "U5") (pin "43") (pinfunction "RB5/AN22_43") (pintype "bidirectional"))
      (node (ref "X-SOUTH") (pin "69") (pinfunction "69_69") (pintype "bidirectional"))
    )
    (net (code "263") (name "S20_N") (class "Default")
      (node (ref "U3") (pin "43") (pinfunction "RB5/AN22_43") (pintype "bidirectional"))
      (node (ref "X-SOUTH") (pin "76") (pinfunction "76_76") (pintype "bidirectional"))
    )
    (net (code "264") (name "S20_P") (class "Default")
      (node (ref "U3") (pin "27") (pinfunction "RA5/AN4_27") (pintype "bidirectional"))
      (node (ref "X-SOUTH") (pin "74") (pinfunction "74_74") (pintype "bidirectional"))
    )
    (net (code "265") (name "S21_N") (class "Default")
      (node (ref "U6") (pin "47") (pinfunction "RB1/AN18_47") (pintype "bidirectional"))
      (node (ref "X-SOUTH") (pin "77") (pinfunction "77_77") (pintype "bidirectional"))
    )
    (net (code "266") (name "S21_P") (class "Default")
      (node (ref "U6") (pin "48") (pinfunction "RB0/AN17_48") (pintype "bidirectional"))
      (node (ref "X-SOUTH") (pin "75") (pinfunction "75_75") (pintype "bidirectional"))
    )
    (net (code "267") (name "S22_N") (class "Default")
      (node (ref "U3") (pin "16") (pinfunction "AN7/RF2_16") (pintype "bidirectional"))
      (node (ref "X-SOUTH") (pin "82") (pinfunction "82_82") (pintype "bidirectional"))
    )
    (net (code "268") (name "S22_P") (class "Default")
      (node (ref "U3") (pin "17") (pinfunction "AN6/RF1_17") (pintype "bidirectional"))
      (node (ref "X-SOUTH") (pin "80") (pinfunction "80_80") (pintype "bidirectional"))
    )
    (net (code "269") (name "S23_N") (class "Default")
      (node (ref "U6") (pin "1") (pinfunction "AN28/RE1_1") (pintype "bidirectional"))
      (node (ref "X-SOUTH") (pin "83") (pinfunction "83_83") (pintype "bidirectional"))
    )
    (net (code "270") (name "S23_P") (class "Default")
      (node (ref "U6") (pin "64") (pinfunction "AN29/RE2_64") (pintype "bidirectional"))
      (node (ref "X-SOUTH") (pin "81") (pinfunction "81_81") (pintype "bidirectional"))
    )
    (net (code "271") (name "S24_N") (class "Default")
      (node (ref "U3") (pin "14") (pinfunction "AN9/RF4_14") (pintype "bidirectional"))
      (node (ref "X-SOUTH") (pin "88") (pinfunction "88_88") (pintype "bidirectional"))
    )
    (net (code "272") (name "S24_P") (class "Default")
      (node (ref "U3") (pin "15") (pinfunction "AN8/RF3_15") (pintype "bidirectional"))
      (node (ref "X-SOUTH") (pin "86") (pinfunction "86_86") (pintype "bidirectional"))
    )
    (net (code "273") (name "S25_N") (class "Default")
      (node (ref "U6") (pin "12") (pinfunction "AN11/RF6_12") (pintype "bidirectional"))
      (node (ref "X-SOUTH") (pin "89") (pinfunction "89_89") (pintype "bidirectional"))
    )
    (net (code "274") (name "S25_P") (class "Default")
      (node (ref "U6") (pin "2") (pinfunction "AN27/RE0_2") (pintype "bidirectional"))
      (node (ref "X-SOUTH") (pin "87") (pinfunction "87_87") (pintype "bidirectional"))
    )
    (net (code "275") (name "S26_N") (class "Default")
      (node (ref "U3") (pin "12") (pinfunction "AN11/RF6_12") (pintype "bidirectional"))
      (node (ref "X-SOUTH") (pin "94") (pinfunction "94_94") (pintype "bidirectional"))
    )
    (net (code "276") (name "S26_P") (class "Default")
      (node (ref "U3") (pin "13") (pinfunction "AN10/RF5_13") (pintype "bidirectional"))
      (node (ref "X-SOUTH") (pin "92") (pinfunction "92_92") (pintype "bidirectional"))
    )
    (net (code "277") (name "S27_N") (class "Default")
      (node (ref "U6") (pin "14") (pinfunction "AN9/RF4_14") (pintype "bidirectional"))
      (node (ref "X-SOUTH") (pin "95") (pinfunction "95_95") (pintype "bidirectional"))
    )
    (net (code "278") (name "S27_P") (class "Default")
      (node (ref "U6") (pin "13") (pinfunction "AN10/RF5_13") (pintype "bidirectional"))
      (node (ref "X-SOUTH") (pin "93") (pinfunction "93_93") (pintype "bidirectional"))
    )
    (net (code "279") (name "S28_N") (class "Default")
      (node (ref "U3") (pin "1") (pinfunction "AN28/RE1_1") (pintype "bidirectional"))
      (node (ref "X-SOUTH") (pin "100") (pinfunction "100_100") (pintype "bidirectional"))
    )
    (net (code "280") (name "S28_P") (class "Default")
      (node (ref "U3") (pin "2") (pinfunction "AN27/RE0_2") (pintype "bidirectional"))
      (node (ref "X-SOUTH") (pin "98") (pinfunction "98_98") (pintype "bidirectional"))
    )
    (net (code "281") (name "S29_N") (class "Default")
      (node (ref "U6") (pin "16") (pinfunction "AN7/RF2_16") (pintype "bidirectional"))
      (node (ref "X-SOUTH") (pin "101") (pinfunction "101_101") (pintype "bidirectional"))
    )
    (net (code "282") (name "S29_P") (class "Default")
      (node (ref "U6") (pin "15") (pinfunction "AN8/RF3_15") (pintype "bidirectional"))
      (node (ref "X-SOUTH") (pin "99") (pinfunction "99_99") (pintype "bidirectional"))
    )
    (net (code "283") (name "S30_N") (class "Default")
      (node (ref "U3") (pin "45") (pinfunction "RB3/AN20_45") (pintype "bidirectional"))
      (node (ref "X-SOUTH") (pin "106") (pinfunction "106_106") (pintype "bidirectional"))
    )
    (net (code "284") (name "S30_P") (class "Default")
      (node (ref "U3") (pin "44") (pinfunction "RB4/AN21_44") (pintype "bidirectional"))
      (node (ref "X-SOUTH") (pin "104") (pinfunction "104_104") (pintype "bidirectional"))
    )
    (net (code "285") (name "S31_N") (class "Default")
      (node (ref "U6") (pin "45") (pinfunction "RB3/AN20_45") (pintype "bidirectional"))
      (node (ref "X-SOUTH") (pin "107") (pinfunction "107_107") (pintype "bidirectional"))
    )
    (net (code "286") (name "S31_P") (class "Default")
      (node (ref "U6") (pin "46") (pinfunction "RB2/AN19_46") (pintype "bidirectional"))
      (node (ref "X-SOUTH") (pin "105") (pinfunction "105_105") (pintype "bidirectional"))
    )
    (net (code "287") (name "S32_N") (class "Default")
      (node (ref "U3") (pin "47") (pinfunction "RB1/AN18_47") (pintype "bidirectional"))
      (node (ref "X-SOUTH") (pin "112") (pinfunction "112_112") (pintype "bidirectional"))
    )
    (net (code "288") (name "S32_P") (class "Default")
      (node (ref "U3") (pin "46") (pinfunction "RB2/AN19_46") (pintype "bidirectional"))
      (node (ref "X-SOUTH") (pin "110") (pinfunction "110_110") (pintype "bidirectional"))
    )
    (net (code "289") (name "S33_N") (class "Default")
      (node (ref "U6") (pin "43") (pinfunction "RB5/AN22_43") (pintype "bidirectional"))
      (node (ref "X-SOUTH") (pin "113") (pinfunction "113_113") (pintype "bidirectional"))
    )
    (net (code "290") (name "S33_P") (class "Default")
      (node (ref "U6") (pin "44") (pinfunction "RB4/AN21_44") (pintype "bidirectional"))
      (node (ref "X-SOUTH") (pin "111") (pinfunction "111_111") (pintype "bidirectional"))
    )
    (net (code "291") (name "S34_N") (class "Default")
      (node (ref "U3") (pin "48") (pinfunction "RB0/AN17_48") (pintype "bidirectional"))
      (node (ref "X-SOUTH") (pin "118") (pinfunction "118_118") (pintype "bidirectional"))
    )
    (net (code "292") (name "S34_P") (class "Default")
      (node (ref "U3") (pin "64") (pinfunction "AN29/RE2_64") (pintype "bidirectional"))
      (node (ref "X-SOUTH") (pin "116") (pinfunction "116_116") (pintype "bidirectional"))
    )
    (net (code "293") (name "S35_N") (class "Default")
      (node (ref "U6") (pin "21") (pinfunction "RA3/AN3/REF+_21") (pintype "bidirectional"))
      (node (ref "X-SOUTH") (pin "119") (pinfunction "119_119") (pintype "bidirectional"))
    )
    (net (code "294") (name "S35_P") (class "Default")
      (node (ref "U6") (pin "17") (pinfunction "AN6/RF1_17") (pintype "bidirectional"))
      (node (ref "X-SOUTH") (pin "117") (pinfunction "117_117") (pintype "bidirectional"))
    )
    (net (code "295") (name "S36_N") (class "Default")
      (node (ref "U3") (pin "55") (pinfunction "AN24/RD1_55") (pintype "bidirectional"))
      (node (ref "X-SOUTH") (pin "124") (pinfunction "124_124") (pintype "bidirectional"))
    )
    (net (code "296") (name "S36_P") (class "Default")
      (node (ref "U3") (pin "58") (pinfunction "AN23/RD0_58") (pintype "bidirectional"))
      (node (ref "X-SOUTH") (pin "122") (pinfunction "122_122") (pintype "bidirectional"))
    )
    (net (code "297") (name "S37_N") (class "Default")
      (node (ref "U6") (pin "23") (pinfunction "RA1/AN1_23") (pintype "bidirectional"))
      (node (ref "X-SOUTH") (pin "125") (pinfunction "125_125") (pintype "bidirectional"))
    )
    (net (code "298") (name "S37_P") (class "Default")
      (node (ref "U6") (pin "22") (pinfunction "RA2/AN2_22") (pintype "bidirectional"))
      (node (ref "X-SOUTH") (pin "123") (pinfunction "123_123") (pintype "bidirectional"))
    )
    (net (code "299") (name "S38_N") (class "Default")
      (node (ref "U3") (pin "53") (pinfunction "AN26/RD3_53") (pintype "bidirectional"))
      (node (ref "X-SOUTH") (pin "130") (pinfunction "130_130") (pintype "bidirectional"))
    )
    (net (code "300") (name "S38_P") (class "Default")
      (node (ref "U3") (pin "54") (pinfunction "AN25/RD2_54") (pintype "bidirectional"))
      (node (ref "X-SOUTH") (pin "128") (pinfunction "128_128") (pintype "bidirectional"))
    )
    (net (code "301") (name "S39_N") (class "Default")
      (node (ref "U6") (pin "27") (pinfunction "RA5/AN4_27") (pintype "bidirectional"))
      (node (ref "X-SOUTH") (pin "131") (pinfunction "131_131") (pintype "bidirectional"))
    )
    (net (code "302") (name "S39_P") (class "Default")
      (node (ref "U6") (pin "24") (pinfunction "RA0/AN0_24") (pintype "bidirectional"))
      (node (ref "X-SOUTH") (pin "129") (pinfunction "129_129") (pintype "bidirectional"))
    )
    (net (code "303") (name "SCK2B") (class "Default")
      (node (ref "SPI-EAST") (pin "3") (pinfunction "3_3") (pintype "passive"))
      (node (ref "U2") (pin "50") (pinfunction "SCK2/RD6_50") (pintype "bidirectional"))
    )
    (net (code "304") (name "SCK4B") (class "Default")
      (node (ref "SPI-WEST") (pin "3") (pinfunction "3_3") (pintype "passive"))
      (node (ref "U4") (pin "50") (pinfunction "SCK2/RD6_50") (pintype "bidirectional"))
    )
    (net (code "305") (name "SCL_N") (class "Default")
      (node (ref "R21") (pin "2") (pinfunction "2_2") (pintype "passive"))
      (node (ref "U11") (pin "2") (pinfunction "SCL_2") (pintype "input"))
      (node (ref "U8") (pin "63") (pinfunction "RE3_63") (pintype "bidirectional"))
    )
    (net (code "306") (name "SCL_S") (class "Default")
      (node (ref "R23") (pin "2") (pinfunction "2_2") (pintype "passive"))
      (node (ref "U12") (pin "2") (pinfunction "SCL_2") (pintype "input"))
      (node (ref "U5") (pin "63") (pinfunction "RE3_63") (pintype "bidirectional"))
    )
    (net (code "307") (name "SDA_N") (class "Default")
      (node (ref "R22") (pin "2") (pinfunction "2_2") (pintype "passive"))
      (node (ref "U11") (pin "3") (pinfunction "SDA_3") (pintype "bidirectional"))
      (node (ref "U8") (pin "62") (pinfunction "RE4_62") (pintype "bidirectional"))
    )
    (net (code "308") (name "SDA_S") (class "Default")
      (node (ref "R24") (pin "2") (pinfunction "2_2") (pintype "passive"))
      (node (ref "U12") (pin "3") (pinfunction "SDA_3") (pintype "bidirectional"))
      (node (ref "U5") (pin "62") (pinfunction "RE4_62") (pintype "bidirectional"))
    )
    (net (code "309") (name "SDI2B") (class "Default")
      (node (ref "SPI-EAST") (pin "4") (pinfunction "4_4") (pintype "passive"))
      (node (ref "U2") (pin "51") (pinfunction "SDI2/RD5_51") (pintype "bidirectional"))
    )
    (net (code "310") (name "SDI4B") (class "Default")
      (node (ref "SPI-WEST") (pin "4") (pinfunction "4_4") (pintype "passive"))
      (node (ref "U4") (pin "51") (pinfunction "SDI2/RD5_51") (pintype "bidirectional"))
    )
    (net (code "311") (name "SDO2B") (class "Default")
      (node (ref "SPI-EAST") (pin "5") (pinfunction "5_5") (pintype "passive"))
      (node (ref "U2") (pin "52") (pinfunction "SDO2/RD4_52") (pintype "bidirectional"))
    )
    (net (code "312") (name "SDO4B") (class "Default")
      (node (ref "SPI-WEST") (pin "5") (pinfunction "5_5") (pintype "passive"))
      (node (ref "U4") (pin "52") (pinfunction "SDO2/RD4_52") (pintype "bidirectional"))
    )
    (net (code "313") (name "SDO6B") (class "Default")
      (node (ref "U6") (pin "52") (pinfunction "SDO2/RD4_52") (pintype "bidirectional"))
    )
    (net (code "314") (name "SDO7B") (class "Default")
      (node (ref "U7") (pin "52") (pinfunction "SDO2/RD4_52") (pintype "bidirectional"))
    )
    (net (code "315") (name "SS2B") (class "Default")
      (node (ref "SPI-EAST") (pin "2") (pinfunction "2_2") (pintype "passive"))
      (node (ref "U2") (pin "49") (pinfunction "~{SS2}/RD7_49") (pintype "bidirectional"))
    )
    (net (code "316") (name "SS4B") (class "Default")
      (node (ref "SPI-WEST") (pin "2") (pinfunction "2_2") (pintype "passive"))
      (node (ref "U4") (pin "49") (pinfunction "~{SS2}/RD7_49") (pintype "bidirectional"))
    )
    (net (code "317") (name "SS6B") (class "Default")
      (node (ref "U6") (pin "49") (pinfunction "~{SS2}/RD7_49") (pintype "bidirectional"))
    )
    (net (code "318") (name "SS7B") (class "Default")
      (node (ref "U7") (pin "49") (pinfunction "~{SS2}/RD7_49") (pintype "bidirectional"))
    )
    (net (code "319") (name "S_CHK_EN") (class "Default")
      (node (ref "U2") (pin "29") (pinfunction "RC1_29") (pintype "bidirectional"))
      (node (ref "X-SOUTH") (pin "8") (pinfunction "8_8") (pintype "bidirectional"))
    )
    (net (code "320") (name "S_CHK_V") (class "Default")
      (node (ref "C143") (pin "1") (pinfunction "1_1") (pintype "passive"))
      (node (ref "C144") (pin "1") (pinfunction "1_1") (pintype "passive"))
      (node (ref "PWRS") (pin "2") (pinfunction "2_2") (pintype "passive"))
      (node (ref "R23") (pin "1") (pinfunction "1_1") (pintype "passive"))
      (node (ref "R24") (pin "1") (pinfunction "1_1") (pintype "passive"))
      (node (ref "U12") (pin "1") (pinfunction "VDD_1") (pintype "power_in"))
      (node (ref "X-SOUTH") (pin "10") (pinfunction "10_10") (pintype "bidirectional"))
    )
    (net (code "321") (name "S_I2C_EN") (class "Default")
      (node (ref "U6") (pin "28") (pinfunction "RA4_28") (pintype "bidirectional"))
      (node (ref "X-SOUTH") (pin "137") (pinfunction "137_137") (pintype "bidirectional"))
    )
    (net (code "322") (name "S_I2C_V") (class "Default")
      (node (ref "X-SOUTH") (pin "135") (pinfunction "135_135") (pintype "bidirectional"))
    )
    (net (code "323") (name "S_SCK") (class "Default")
      (node (ref "U3") (pin "50") (pinfunction "SCK2/RD6_50") (pintype "bidirectional"))
      (node (ref "X-SOUTH") (pin "144") (pinfunction "144_144") (pintype "bidirectional"))
    )
    (net (code "324") (name "S_SCL") (class "Default")
      (node (ref "R4") (pin "2") (pinfunction "2_2") (pintype "passive"))
      (node (ref "U6") (pin "50") (pinfunction "SCK2/RD6_50") (pintype "bidirectional"))
      (node (ref "X-SOUTH") (pin "143") (pinfunction "143_143") (pintype "bidirectional"))
    )
    (net (code "325") (name "S_SDA") (class "Default")
      (node (ref "R3") (pin "2") (pinfunction "2_2") (pintype "passive"))
      (node (ref "U6") (pin "51") (pinfunction "SDI2/RD5_51") (pintype "bidirectional"))
      (node (ref "X-SOUTH") (pin "141") (pinfunction "141_141") (pintype "bidirectional"))
    )
    (net (code "326") (name "S_SDI") (class "Default")
      (node (ref "U3") (pin "51") (pinfunction "SDI2/RD5_51") (pintype "bidirectional"))
      (node (ref "X-SOUTH") (pin "140") (pinfunction "140_140") (pintype "bidirectional"))
    )
    (net (code "327") (name "S_SDO") (class "Default")
      (node (ref "U3") (pin "52") (pinfunction "SDO2/RD4_52") (pintype "bidirectional"))
      (node (ref "X-SOUTH") (pin "142") (pinfunction "142_142") (pintype "bidirectional"))
    )
    (net (code "328") (name "S_SPI_EN") (class "Default")
      (node (ref "U3") (pin "49") (pinfunction "~{SS2}/RD7_49") (pintype "bidirectional"))
      (node (ref "X-SOUTH") (pin "136") (pinfunction "136_136") (pintype "bidirectional"))
    )
    (net (code "329") (name "S_SPI_V") (class "Default")
      (node (ref "X-SOUTH") (pin "134") (pinfunction "134_134") (pintype "bidirectional"))
    )
    (net (code "330") (name "S_VE") (class "Default")
      (node (ref "C134") (pin "1") (pinfunction "1_1") (pintype "passive"))
      (node (ref "PWR-SOUTH") (pin "6") (pinfunction "6_6") (pintype "passive"))
      (node (ref "X-SOUTH") (pin "13") (pinfunction "13_13") (pintype "bidirectional"))
      (node (ref "X-SOUTH") (pin "19") (pinfunction "19_19") (pintype "bidirectional"))
      (node (ref "X-SOUTH") (pin "31") (pinfunction "31_31") (pintype "bidirectional"))
      (node (ref "X-SOUTH") (pin "37") (pinfunction "37_37") (pintype "bidirectional"))
    )
    (net (code "331") (name "S_VE_CV") (class "Default")
      (node (ref "U12") (pin "9") (pinfunction "VOUTD_9") (pintype "output"))
      (node (ref "X-SOUTH") (pin "2") (pinfunction "2_2") (pintype "bidirectional"))
    )
    (net (code "332") (name "S_VE_OV") (class "Default")
      (node (ref "U5") (pin "49") (pinfunction "~{SS2}/RD7_49") (pintype "bidirectional"))
      (node (ref "X-SOUTH") (pin "1") (pinfunction "1_1") (pintype "bidirectional"))
    )
    (net (code "333") (name "S_VE_RS") (class "Default")
      (node (ref "X-SOUTH") (pin "25") (pinfunction "25_25") (pintype "bidirectional"))
    )
    (net (code "334") (name "S_VE_UV") (class "Default")
      (node (ref "U5") (pin "59") (pinfunction "RE7_59") (pintype "bidirectional"))
      (node (ref "X-SOUTH") (pin "7") (pinfunction "7_7") (pintype "bidirectional"))
    )
    (net (code "335") (name "S_VS") (class "Default")
      (node (ref "C135") (pin "1") (pinfunction "1_1") (pintype "passive"))
      (node (ref "PWR-SOUTH") (pin "4") (pinfunction "4_4") (pintype "passive"))
      (node (ref "X-SOUTH") (pin "49") (pinfunction "49_49") (pintype "bidirectional"))
      (node (ref "X-SOUTH") (pin "55") (pinfunction "55_55") (pintype "bidirectional"))
      (node (ref "X-SOUTH") (pin "61") (pinfunction "61_61") (pintype "bidirectional"))
      (node (ref "X-SOUTH") (pin "67") (pinfunction "67_67") (pintype "bidirectional"))
      (node (ref "X-SOUTH") (pin "79") (pinfunction "79_79") (pintype "bidirectional"))
      (node (ref "X-SOUTH") (pin "85") (pinfunction "85_85") (pintype "bidirectional"))
      (node (ref "X-SOUTH") (pin "91") (pinfunction "91_91") (pintype "bidirectional"))
      (node (ref "X-SOUTH") (pin "97") (pinfunction "97_97") (pintype "bidirectional"))
    )
    (net (code "336") (name "S_VS_CV") (class "Default")
      (node (ref "U12") (pin "8") (pinfunction "VOUTC_8") (pintype "output"))
      (node (ref "X-SOUTH") (pin "4") (pinfunction "4_4") (pintype "bidirectional"))
    )
    (net (code "337") (name "S_VS_OV") (class "Default")
      (node (ref "U5") (pin "50") (pinfunction "SCK2/RD6_50") (pintype "bidirectional"))
      (node (ref "X-SOUTH") (pin "3") (pinfunction "3_3") (pintype "bidirectional"))
    )
    (net (code "338") (name "S_VS_RS") (class "Default")
      (node (ref "X-SOUTH") (pin "73") (pinfunction "73_73") (pintype "bidirectional"))
    )
    (net (code "339") (name "S_VS_UV") (class "Default")
      (node (ref "U5") (pin "60") (pinfunction "RE6_60") (pintype "bidirectional"))
      (node (ref "X-SOUTH") (pin "9") (pinfunction "9_9") (pintype "bidirectional"))
    )
    (net (code "340") (name "S_VW") (class "Default")
      (node (ref "C136") (pin "1") (pinfunction "1_1") (pintype "passive"))
      (node (ref "PWR-SOUTH") (pin "2") (pinfunction "2_2") (pintype "passive"))
      (node (ref "X-SOUTH") (pin "109") (pinfunction "109_109") (pintype "bidirectional"))
      (node (ref "X-SOUTH") (pin "115") (pinfunction "115_115") (pintype "bidirectional"))
      (node (ref "X-SOUTH") (pin "127") (pinfunction "127_127") (pintype "bidirectional"))
      (node (ref "X-SOUTH") (pin "133") (pinfunction "133_133") (pintype "bidirectional"))
    )
    (net (code "341") (name "S_VW_CV") (class "Default")
      (node (ref "U12") (pin "7") (pinfunction "VOUTB_7") (pintype "output"))
      (node (ref "X-SOUTH") (pin "6") (pinfunction "6_6") (pintype "bidirectional"))
    )
    (net (code "342") (name "S_VW_OV") (class "Default")
      (node (ref "U5") (pin "51") (pinfunction "SDI2/RD5_51") (pintype "bidirectional"))
      (node (ref "X-SOUTH") (pin "5") (pinfunction "5_5") (pintype "bidirectional"))
    )
    (net (code "343") (name "S_VW_RS") (class "Default")
      (node (ref "X-SOUTH") (pin "121") (pinfunction "121_121") (pintype "bidirectional"))
    )
    (net (code "344") (name "S_VW_UV") (class "Default")
      (node (ref "U5") (pin "61") (pinfunction "RE5_61") (pintype "bidirectional"))
      (node (ref "X-SOUTH") (pin "11") (pinfunction "11_11") (pintype "bidirectional"))
    )
    (net (code "345") (name "TX1") (class "Default")
      (node (ref "SER1") (pin "2") (pinfunction "2_2") (pintype "passive"))
      (node (ref "U1") (pin "31") (pinfunction "RC6/TX1_31") (pintype "bidirectional"))
    )
    (net (code "346") (name "TX1B") (class "Default")
      (node (ref "U1") (pin "4") (pinfunction "TX2/AN15/RG1_4") (pintype "bidirectional"))
    )
    (net (code "347") (name "TX2") (class "Default")
      (node (ref "SER2") (pin "2") (pinfunction "2_2") (pintype "passive"))
      (node (ref "U2") (pin "31") (pinfunction "RC6/TX1_31") (pintype "bidirectional"))
    )
    (net (code "348") (name "TX2B") (class "Default")
      (node (ref "U2") (pin "4") (pinfunction "TX2/AN15/RG1_4") (pintype "bidirectional"))
    )
    (net (code "349") (name "TX3") (class "Default")
      (node (ref "SER3") (pin "2") (pinfunction "2_2") (pintype "passive"))
      (node (ref "U3") (pin "31") (pinfunction "RC6/TX1_31") (pintype "bidirectional"))
    )
    (net (code "350") (name "TX3B") (class "Default")
      (node (ref "U3") (pin "4") (pinfunction "TX2/AN15/RG1_4") (pintype "bidirectional"))
    )
    (net (code "351") (name "TX4") (class "Default")
      (node (ref "SER4") (pin "2") (pinfunction "2_2") (pintype "passive"))
      (node (ref "U4") (pin "31") (pinfunction "RC6/TX1_31") (pintype "bidirectional"))
    )
    (net (code "352") (name "TX4B") (class "Default")
      (node (ref "U4") (pin "4") (pinfunction "TX2/AN15/RG1_4") (pintype "bidirectional"))
    )
    (net (code "353") (name "TX5") (class "Default")
      (node (ref "SER5") (pin "2") (pinfunction "2_2") (pintype "passive"))
      (node (ref "U5") (pin "31") (pinfunction "RC6/TX1_31") (pintype "bidirectional"))
    )
    (net (code "354") (name "TX5B") (class "Default")
      (node (ref "U5") (pin "4") (pinfunction "TX2/AN15/RG1_4") (pintype "bidirectional"))
    )
    (net (code "355") (name "TX6") (class "Default")
      (node (ref "SER6") (pin "2") (pinfunction "2_2") (pintype "passive"))
      (node (ref "U6") (pin "31") (pinfunction "RC6/TX1_31") (pintype "bidirectional"))
    )
    (net (code "356") (name "TX6B") (class "Default")
      (node (ref "U6") (pin "4") (pinfunction "TX2/AN15/RG1_4") (pintype "bidirectional"))
    )
    (net (code "357") (name "TX7") (class "Default")
      (node (ref "SER7") (pin "2") (pinfunction "2_2") (pintype "passive"))
      (node (ref "U7") (pin "31") (pinfunction "RC6/TX1_31") (pintype "bidirectional"))
    )
    (net (code "358") (name "TX7B") (class "Default")
      (node (ref "U7") (pin "4") (pinfunction "TX2/AN15/RG1_4") (pintype "bidirectional"))
    )
    (net (code "359") (name "TX8") (class "Default")
      (node (ref "SER8") (pin "2") (pinfunction "2_2") (pintype "passive"))
      (node (ref "U8") (pin "31") (pinfunction "RC6/TX1_31") (pintype "bidirectional"))
    )
    (net (code "360") (name "TX8B") (class "Default")
      (node (ref "U8") (pin "4") (pinfunction "TX2/AN15/RG1_4") (pintype "bidirectional"))
    )
    (net (code "361") (name "VCC") (class "Default")
      (node (ref "C10") (pin "1") (pinfunction "1_1") (pintype "passive"))
      (node (ref "C100") (pin "1") (pinfunction "1_1") (pintype "passive"))
      (node (ref "C13") (pin "1") (pinfunction "1_1") (pintype "passive"))
      (node (ref "C133") (pin "1") (pinfunction "1_1") (pintype "passive"))
      (node (ref "C137") (pin "1") (pinfunction "1_1") (pintype "passive"))
      (node (ref "C14") (pin "1") (pinfunction "1_1") (pintype "passive"))
      (node (ref "C15") (pin "1") (pinfunction "1_1") (pintype "passive"))
      (node (ref "C16") (pin "1") (pinfunction "1_1") (pintype "passive"))
      (node (ref "C18") (pin "1") (pinfunction "1_1") (pintype "passive"))
      (node (ref "C19") (pin "1") (pinfunction "1_1") (pintype "passive"))
      (node (ref "C2") (pin "1") (pinfunction "1_1") (pintype "passive"))
      (node (ref "C20") (pin "1") (pinfunction "1_1") (pintype "passive"))
      (node (ref "C21") (pin "1") (pinfunction "1_1") (pintype "passive"))
      (node (ref "C24") (pin "1") (pinfunction "1_1") (pintype "passive"))
      (node (ref "C25") (pin "1") (pinfunction "1_1") (pintype "passive"))
      (node (ref "C26") (pin "1") (pinfunction "1_1") (pintype "passive"))
      (node (ref "C27") (pin "1") (pinfunction "1_1") (pintype "passive"))
      (node (ref "C29") (pin "1") (pinfunction "1_1") (pintype "passive"))
      (node (ref "C3") (pin "1") (pinfunction "1_1") (pintype "passive"))
      (node (ref "C30") (pin "1") (pinfunction "1_1") (pintype "passive"))
      (node (ref "C31") (pin "1") (pinfunction "1_1") (pintype "passive"))
      (node (ref "C32") (pin "1") (pinfunction "1_1") (pintype "passive"))
      (node (ref "C35") (pin "1") (pinfunction "1_1") (pintype "passive"))
      (node (ref "C36") (pin "1") (pinfunction "1_1") (pintype "passive"))
      (node (ref "C37") (pin "1") (pinfunction "1_1") (pintype "passive"))
      (node (ref "C38") (pin "1") (pinfunction "1_1") (pintype "passive"))
      (node (ref "C4") (pin "1") (pinfunction "1_1") (pintype "passive"))
      (node (ref "C40") (pin "1") (pinfunction "1_1") (pintype "passive"))
      (node (ref "C41") (pin "1") (pinfunction "1_1") (pintype "passive"))
      (node (ref "C42") (pin "1") (pinfunction "1_1") (pintype "passive"))
      (node (ref "C43") (pin "1") (pinfunction "1_1") (pintype "passive"))
      (node (ref "C46") (pin "1") (pinfunction "1_1") (pintype "passive"))
      (node (ref "C47") (pin "1") (pinfunction "1_1") (pintype "passive"))
      (node (ref "C48") (pin "1") (pinfunction "1_1") (pintype "passive"))
      (node (ref "C49") (pin "1") (pinfunction "1_1") (pintype "passive"))
      (node (ref "C5") (pin "1") (pinfunction "1_1") (pintype "passive"))
      (node (ref "C51") (pin "1") (pinfunction "1_1") (pintype "passive"))
      (node (ref "C52") (pin "1") (pinfunction "1_1") (pintype "passive"))
      (node (ref "C53") (pin "1") (pinfunction "1_1") (pintype "passive"))
      (node (ref "C54") (pin "1") (pinfunction "1_1") (pintype "passive"))
      (node (ref "C57") (pin "1") (pinfunction "1_1") (pintype "passive"))
      (node (ref "C58") (pin "1") (pinfunction "1_1") (pintype "passive"))
      (node (ref "C59") (pin "1") (pinfunction "1_1") (pintype "passive"))
      (node (ref "C60") (pin "1") (pinfunction "1_1") (pintype "passive"))
      (node (ref "C62") (pin "1") (pinfunction "1_1") (pintype "passive"))
      (node (ref "C63") (pin "1") (pinfunction "1_1") (pintype "passive"))
      (node (ref "C64") (pin "1") (pinfunction "1_1") (pintype "passive"))
      (node (ref "C65") (pin "1") (pinfunction "1_1") (pintype "passive"))
      (node (ref "C68") (pin "1") (pinfunction "1_1") (pintype "passive"))
      (node (ref "C69") (pin "1") (pinfunction "1_1") (pintype "passive"))
      (node (ref "C7") (pin "1") (pinfunction "1_1") (pintype "passive"))
      (node (ref "C70") (pin "1") (pinfunction "1_1") (pintype "passive"))
      (node (ref "C71") (pin "1") (pinfunction "1_1") (pintype "passive"))
      (node (ref "C73") (pin "1") (pinfunction "1_1") (pintype "passive"))
      (node (ref "C74") (pin "1") (pinfunction "1_1") (pintype "passive"))
      (node (ref "C75") (pin "1") (pinfunction "1_1") (pintype "passive"))
      (node (ref "C76") (pin "1") (pinfunction "1_1") (pintype "passive"))
      (node (ref "C79") (pin "1") (pinfunction "1_1") (pintype "passive"))
      (node (ref "C8") (pin "1") (pinfunction "1_1") (pintype "passive"))
      (node (ref "C80") (pin "1") (pinfunction "1_1") (pintype "passive"))
      (node (ref "C81") (pin "1") (pinfunction "1_1") (pintype "passive"))
      (node (ref "C82") (pin "1") (pinfunction "1_1") (pintype "passive"))
      (node (ref "C84") (pin "1") (pinfunction "1_1") (pintype "passive"))
      (node (ref "C85") (pin "1") (pinfunction "1_1") (pintype "passive"))
      (node (ref "C86") (pin "1") (pinfunction "1_1") (pintype "passive"))
      (node (ref "C87") (pin "1") (pinfunction "1_1") (pintype "passive"))
      (node (ref "C89") (pin "1") (pinfunction "1_1") (pintype "passive"))
      (node (ref "C9") (pin "1") (pinfunction "1_1") (pintype "passive"))
      (node (ref "C90") (pin "1") (pinfunction "1_1") (pintype "passive"))
      (node (ref "C91") (pin "1") (pinfunction "1_1") (pintype "passive"))
      (node (ref "C92") (pin "1") (pinfunction "1_1") (pintype "passive"))
      (node (ref "C93") (pin "1") (pinfunction "1_1") (pintype "passive"))
      (node (ref "C94") (pin "1") (pinfunction "1_1") (pintype "passive"))
      (node (ref "C95") (pin "1") (pinfunction "1_1") (pintype "passive"))
      (node (ref "C96") (pin "1") (pinfunction "1_1") (pintype "passive"))
      (node (ref "C97") (pin "1") (pinfunction "1_1") (pintype "passive"))
      (node (ref "C98") (pin "1") (pinfunction "1_1") (pintype "passive"))
      (node (ref "C99") (pin "1") (pinfunction "1_1") (pintype "passive"))
      (node (ref "L1") (pin "1") (pinfunction "1_1") (pintype "passive"))
      (node (ref "L2") (pin "1") (pinfunction "1_1") (pintype "passive"))
      (node (ref "L3") (pin "1") (pinfunction "1_1") (pintype "passive"))
      (node (ref "L4") (pin "1") (pinfunction "1_1") (pintype "passive"))
      (node (ref "L5") (pin "1") (pinfunction "1_1") (pintype "passive"))
      (node (ref "L6") (pin "1") (pinfunction "1_1") (pintype "passive"))
      (node (ref "L7") (pin "1") (pinfunction "1_1") (pintype "passive"))
      (node (ref "L8") (pin "1") (pinfunction "1_1") (pintype "passive"))
      (node (ref "R1") (pin "1") (pinfunction "1_1") (pintype "passive"))
      (node (ref "R10") (pin "1") (pinfunction "1_1") (pintype "passive"))
      (node (ref "R11") (pin "1") (pinfunction "1_1") (pintype "passive"))
      (node (ref "R12") (pin "1") (pinfunction "1_1") (pintype "passive"))
      (node (ref "R13") (pin "1") (pinfunction "1_1") (pintype "passive"))
      (node (ref "R14") (pin "1") (pinfunction "1_1") (pintype "passive"))
      (node (ref "R15") (pin "1") (pinfunction "1_1") (pintype "passive"))
      (node (ref "R16") (pin "1") (pinfunction "1_1") (pintype "passive"))
      (node (ref "R17") (pin "1") (pinfunction "1_1") (pintype "passive"))
      (node (ref "R18") (pin "1") (pinfunction "1_1") (pintype "passive"))
      (node (ref "R19") (pin "1") (pinfunction "1_1") (pintype "passive"))
      (node (ref "R2") (pin "1") (pinfunction "1_1") (pintype "passive"))
      (node (ref "R20") (pin "1") (pinfunction "1_1") (pintype "passive"))
      (node (ref "R3") (pin "1") (pinfunction "1_1") (pintype "passive"))
      (node (ref "R4") (pin "1") (pinfunction "1_1") (pintype "passive"))
      (node (ref "R5") (pin "1") (pinfunction "1_1") (pintype "passive"))
      (node (ref "R6") (pin "1") (pinfunction "1_1") (pintype "passive"))
      (node (ref "R7") (pin "1") (pinfunction "1_1") (pintype "passive"))
      (node (ref "R8") (pin "1") (pinfunction "1_1") (pintype "passive"))
      (node (ref "R9") (pin "1") (pinfunction "1_1") (pintype "passive"))
      (node (ref "SPI-EAST") (pin "6") (pinfunction "6_6") (pintype "passive"))
      (node (ref "SPI-WEST") (pin "6") (pinfunction "6_6") (pintype "passive"))
      (node (ref "SUP-N") (pin "2") (pinfunction "2_2") (pintype "passive"))
      (node (ref "SUP-S") (pin "2") (pinfunction "2_2") (pintype "passive"))
      (node (ref "U1") (pin "10") (pinfunction "VDD_10") (pintype "power_in"))
      (node (ref "U1") (pin "26") (pinfunction "VDD_26") (pintype "power_in"))
      (node (ref "U1") (pin "38") (pinfunction "VDD_38") (pintype "power_in"))
      (node (ref "U1") (pin "57") (pinfunction "VDD_57") (pintype "power_in"))
      (node (ref "U10") (pin "1") (pinfunction "EN_1") (pintype "bidirectional"))
      (node (ref "U10") (pin "4") (pinfunction "VCC_4") (pintype "bidirectional"))
      (node (ref "U2") (pin "10") (pinfunction "VDD_10") (pintype "power_in"))
      (node (ref "U2") (pin "26") (pinfunction "VDD_26") (pintype "power_in"))
      (node (ref "U2") (pin "38") (pinfunction "VDD_38") (pintype "power_in"))
      (node (ref "U2") (pin "57") (pinfunction "VDD_57") (pintype "power_in"))
      (node (ref "U3") (pin "10") (pinfunction "VDD_10") (pintype "power_in"))
      (node (ref "U3") (pin "26") (pinfunction "VDD_26") (pintype "power_in"))
      (node (ref "U3") (pin "38") (pinfunction "VDD_38") (pintype "power_in"))
      (node (ref "U3") (pin "57") (pinfunction "VDD_57") (pintype "power_in"))
      (node (ref "U4") (pin "10") (pinfunction "VDD_10") (pintype "power_in"))
      (node (ref "U4") (pin "26") (pinfunction "VDD_26") (pintype "power_in"))
      (node (ref "U4") (pin "38") (pinfunction "VDD_38") (pintype "power_in"))
      (node (ref "U4") (pin "57") (pinfunction "VDD_57") (pintype "power_in"))
      (node (ref "U5") (pin "10") (pinfunction "VDD_10") (pintype "power_in"))
      (node (ref "U5") (pin "26") (pinfunction "VDD_26") (pintype "power_in"))
      (node (ref "U5") (pin "38") (pinfunction "VDD_38") (pintype "power_in"))
      (node (ref "U5") (pin "57") (pinfunction "VDD_57") (pintype "power_in"))
      (node (ref "U6") (pin "10") (pinfunction "VDD_10") (pintype "power_in"))
      (node (ref "U6") (pin "26") (pinfunction "VDD_26") (pintype "power_in"))
      (node (ref "U6") (pin "38") (pinfunction "VDD_38") (pintype "power_in"))
      (node (ref "U6") (pin "57") (pinfunction "VDD_57") (pintype "power_in"))
      (node (ref "U7") (pin "10") (pinfunction "VDD_10") (pintype "power_in"))
      (node (ref "U7") (pin "26") (pinfunction "VDD_26") (pintype "power_in"))
      (node (ref "U7") (pin "38") (pinfunction "VDD_38") (pintype "power_in"))
      (node (ref "U7") (pin "57") (pinfunction "VDD_57") (pintype "power_in"))
      (node (ref "U8") (pin "10") (pinfunction "VDD_10") (pintype "power_in"))
      (node (ref "U8") (pin "26") (pinfunction "VDD_26") (pintype "power_in"))
      (node (ref "U8") (pin "38") (pinfunction "VDD_38") (pintype "power_in"))
      (node (ref "U8") (pin "57") (pinfunction "VDD_57") (pintype "power_in"))
      (node (ref "U9") (pin "10") (pinfunction "VCC_10") (pintype "power_in"))
      (node (ref "U9") (pin "14") (pinfunction "VCC_14") (pintype "power_in"))
      (node (ref "U9") (pin "2") (pinfunction "OE_2") (pintype "input"))
      (node (ref "U9") (pin "5") (pinfunction "VCC_5") (pintype "power_in"))
    )
    (net (code "362") (name "W_SCK") (class "Default")
      (node (ref "U3") (pin "34") (pinfunction "RC3/SCK1_34") (pintype "bidirectional"))
      (node (ref "U4") (pin "34") (pinfunction "RC3/SCK1_34") (pintype "bidirectional"))
      (node (ref "U6") (pin "34") (pinfunction "RC3/SCK1_34") (pintype "bidirectional"))
      (node (ref "U8") (pin "34") (pinfunction "RC3/SCK1_34") (pintype "bidirectional"))
    )
    (net (code "363") (name "W_SD_36") (class "Default")
      (node (ref "U3") (pin "36") (pinfunction "RC5/SDO1_36") (pintype "bidirectional"))
      (node (ref "U6") (pin "35") (pinfunction "RC4/SDI1_35") (pintype "bidirectional"))
    )
    (net (code "364") (name "W_SD_43") (class "Default")
      (node (ref "U3") (pin "35") (pinfunction "RC4/SDI1_35") (pintype "bidirectional"))
      (node (ref "U4") (pin "36") (pinfunction "RC5/SDO1_36") (pintype "bidirectional"))
    )
    (net (code "365") (name "W_SD_68") (class "Default")
      (node (ref "U6") (pin "36") (pinfunction "RC5/SDO1_36") (pintype "bidirectional"))
      (node (ref "U8") (pin "35") (pinfunction "RC4/SDI1_35") (pintype "bidirectional"))
    )
    (net (code "366") (name "W_SD_84") (class "Default")
      (node (ref "U4") (pin "35") (pinfunction "RC4/SDI1_35") (pintype "bidirectional"))
      (node (ref "U8") (pin "36") (pinfunction "RC5/SDO1_36") (pintype "bidirectional"))
    )
    (net (code "367") (name "unconnected-(U1-AN12{slash}RG4-Pad8)") (class "Default")
      (node (ref "U1") (pin "8") (pinfunction "AN12/RG4_8") (pintype "bidirectional"))
    )
    (net (code "368") (name "unconnected-(U1-AN13{slash}RG3-Pad6)") (class "Default")
      (node (ref "U1") (pin "6") (pinfunction "AN13/RG3_6") (pintype "bidirectional"))
    )
    (net (code "369") (name "unconnected-(U1-RA4-Pad28)") (class "Default")
      (node (ref "U1") (pin "28") (pinfunction "RA4_28") (pintype "bidirectional"))
    )
    (net (code "370") (name "unconnected-(U1-RA6-Pad40)") (class "Default")
      (node (ref "U1") (pin "40") (pinfunction "RA6_40") (pintype "bidirectional"))
    )
    (net (code "371") (name "unconnected-(U1-RC0-Pad30)") (class "Default")
      (node (ref "U1") (pin "30") (pinfunction "RC0_30") (pintype "bidirectional"))
    )
    (net (code "372") (name "unconnected-(U1-RC1-Pad29)") (class "Default")
      (node (ref "U1") (pin "29") (pinfunction "RC1_29") (pintype "bidirectional"))
    )
    (net (code "373") (name "unconnected-(U1-RE3-Pad63)") (class "Default")
      (node (ref "U1") (pin "63") (pinfunction "RE3_63") (pintype "bidirectional"))
    )
    (net (code "374") (name "unconnected-(U1-RE4-Pad62)") (class "Default")
      (node (ref "U1") (pin "62") (pinfunction "RE4_62") (pintype "bidirectional"))
    )
    (net (code "375") (name "unconnected-(U1-RG0-Pad3)") (class "Default")
      (node (ref "U1") (pin "3") (pinfunction "RG0_3") (pintype "bidirectional"))
    )
    (net (code "376") (name "unconnected-(U2-AN12{slash}RG4-Pad8)") (class "Default")
      (node (ref "U2") (pin "8") (pinfunction "AN12/RG4_8") (pintype "bidirectional"))
    )
    (net (code "377") (name "unconnected-(U2-AN13{slash}RG3-Pad6)") (class "Default")
      (node (ref "U2") (pin "6") (pinfunction "AN13/RG3_6") (pintype "bidirectional"))
    )
    (net (code "378") (name "unconnected-(U2-RA4-Pad28)") (class "Default")
      (node (ref "U2") (pin "28") (pinfunction "RA4_28") (pintype "bidirectional"))
    )
    (net (code "379") (name "unconnected-(U2-RA6-Pad40)") (class "Default")
      (node (ref "U2") (pin "40") (pinfunction "RA6_40") (pintype "bidirectional"))
    )
    (net (code "380") (name "unconnected-(U2-RC0-Pad30)") (class "Default")
      (node (ref "U2") (pin "30") (pinfunction "RC0_30") (pintype "bidirectional"))
    )
    (net (code "381") (name "unconnected-(U2-RE3-Pad63)") (class "Default")
      (node (ref "U2") (pin "63") (pinfunction "RE3_63") (pintype "bidirectional"))
    )
    (net (code "382") (name "unconnected-(U2-RE4-Pad62)") (class "Default")
      (node (ref "U2") (pin "62") (pinfunction "RE4_62") (pintype "bidirectional"))
    )
    (net (code "383") (name "unconnected-(U2-RE5-Pad61)") (class "Default")
      (node (ref "U2") (pin "61") (pinfunction "RE5_61") (pintype "bidirectional"))
    )
    (net (code "384") (name "unconnected-(U2-RE6-Pad60)") (class "Default")
      (node (ref "U2") (pin "60") (pinfunction "RE6_60") (pintype "bidirectional"))
    )
    (net (code "385") (name "unconnected-(U2-RE7-Pad59)") (class "Default")
      (node (ref "U2") (pin "59") (pinfunction "RE7_59") (pintype "bidirectional"))
    )
    (net (code "386") (name "unconnected-(U2-RG0-Pad3)") (class "Default")
      (node (ref "U2") (pin "3") (pinfunction "RG0_3") (pintype "bidirectional"))
    )
    (net (code "387") (name "unconnected-(U3-AN12{slash}RG4-Pad8)") (class "Default")
      (node (ref "U3") (pin "8") (pinfunction "AN12/RG4_8") (pintype "bidirectional"))
    )
    (net (code "388") (name "unconnected-(U3-AN13{slash}RG3-Pad6)") (class "Default")
      (node (ref "U3") (pin "6") (pinfunction "AN13/RG3_6") (pintype "bidirectional"))
    )
    (net (code "389") (name "unconnected-(U3-RA4-Pad28)") (class "Default")
      (node (ref "U3") (pin "28") (pinfunction "RA4_28") (pintype "bidirectional"))
    )
    (net (code "390") (name "unconnected-(U3-RA6-Pad40)") (class "Default")
      (node (ref "U3") (pin "40") (pinfunction "RA6_40") (pintype "bidirectional"))
    )
    (net (code "391") (name "unconnected-(U3-RC0-Pad30)") (class "Default")
      (node (ref "U3") (pin "30") (pinfunction "RC0_30") (pintype "bidirectional"))
    )
    (net (code "392") (name "unconnected-(U3-RC1-Pad29)") (class "Default")
      (node (ref "U3") (pin "29") (pinfunction "RC1_29") (pintype "bidirectional"))
    )
    (net (code "393") (name "unconnected-(U3-RE3-Pad63)") (class "Default")
      (node (ref "U3") (pin "63") (pinfunction "RE3_63") (pintype "bidirectional"))
    )
    (net (code "394") (name "unconnected-(U3-RE4-Pad62)") (class "Default")
      (node (ref "U3") (pin "62") (pinfunction "RE4_62") (pintype "bidirectional"))
    )
    (net (code "395") (name "unconnected-(U3-RE5-Pad61)") (class "Default")
      (node (ref "U3") (pin "61") (pinfunction "RE5_61") (pintype "bidirectional"))
    )
    (net (code "396") (name "unconnected-(U3-RE6-Pad60)") (class "Default")
      (node (ref "U3") (pin "60") (pinfunction "RE6_60") (pintype "bidirectional"))
    )
    (net (code "397") (name "unconnected-(U3-RE7-Pad59)") (class "Default")
      (node (ref "U3") (pin "59") (pinfunction "RE7_59") (pintype "bidirectional"))
    )
    (net (code "398") (name "unconnected-(U3-RG0-Pad3)") (class "Default")
      (node (ref "U3") (pin "3") (pinfunction "RG0_3") (pintype "bidirectional"))
    )
    (net (code "399") (name "unconnected-(U4-AN12{slash}RG4-Pad8)") (class "Default")
      (node (ref "U4") (pin "8") (pinfunction "AN12/RG4_8") (pintype "bidirectional"))
    )
    (net (code "400") (name "unconnected-(U4-AN13{slash}RG3-Pad6)") (class "Default")
      (node (ref "U4") (pin "6") (pinfunction "AN13/RG3_6") (pintype "bidirectional"))
    )
    (net (code "401") (name "unconnected-(U4-RA4-Pad28)") (class "Default")
      (node (ref "U4") (pin "28") (pinfunction "RA4_28") (pintype "bidirectional"))
    )
    (net (code "402") (name "unconnected-(U4-RA6-Pad40)") (class "Default")
      (node (ref "U4") (pin "40") (pinfunction "RA6_40") (pintype "bidirectional"))
    )
    (net (code "403") (name "unconnected-(U4-RC0-Pad30)") (class "Default")
      (node (ref "U4") (pin "30") (pinfunction "RC0_30") (pintype "bidirectional"))
    )
    (net (code "404") (name "unconnected-(U4-RE3-Pad63)") (class "Default")
      (node (ref "U4") (pin "63") (pinfunction "RE3_63") (pintype "bidirectional"))
    )
    (net (code "405") (name "unconnected-(U4-RE4-Pad62)") (class "Default")
      (node (ref "U4") (pin "62") (pinfunction "RE4_62") (pintype "bidirectional"))
    )
    (net (code "406") (name "unconnected-(U4-RE5-Pad61)") (class "Default")
      (node (ref "U4") (pin "61") (pinfunction "RE5_61") (pintype "bidirectional"))
    )
    (net (code "407") (name "unconnected-(U4-RE6-Pad60)") (class "Default")
      (node (ref "U4") (pin "60") (pinfunction "RE6_60") (pintype "bidirectional"))
    )
    (net (code "408") (name "unconnected-(U4-RE7-Pad59)") (class "Default")
      (node (ref "U4") (pin "59") (pinfunction "RE7_59") (pintype "bidirectional"))
    )
    (net (code "409") (name "unconnected-(U4-RG0-Pad3)") (class "Default")
      (node (ref "U4") (pin "3") (pinfunction "RG0_3") (pintype "bidirectional"))
    )
    (net (code "410") (name "unconnected-(U5-AN12{slash}RG4-Pad8)") (class "Default")
      (node (ref "U5") (pin "8") (pinfunction "AN12/RG4_8") (pintype "bidirectional"))
    )
    (net (code "411") (name "unconnected-(U5-AN13{slash}RG3-Pad6)") (class "Default")
      (node (ref "U5") (pin "6") (pinfunction "AN13/RG3_6") (pintype "bidirectional"))
    )
    (net (code "412") (name "unconnected-(U5-RA4-Pad28)") (class "Default")
      (node (ref "U5") (pin "28") (pinfunction "RA4_28") (pintype "bidirectional"))
    )
    (net (code "413") (name "unconnected-(U5-RA6-Pad40)") (class "Default")
      (node (ref "U5") (pin "40") (pinfunction "RA6_40") (pintype "bidirectional"))
    )
    (net (code "414") (name "unconnected-(U5-RG0-Pad3)") (class "Default")
      (node (ref "U5") (pin "3") (pinfunction "RG0_3") (pintype "bidirectional"))
    )
    (net (code "415") (name "unconnected-(U6-AN12{slash}RG4-Pad8)") (class "Default")
      (node (ref "U6") (pin "8") (pinfunction "AN12/RG4_8") (pintype "bidirectional"))
    )
    (net (code "416") (name "unconnected-(U6-AN13{slash}RG3-Pad6)") (class "Default")
      (node (ref "U6") (pin "6") (pinfunction "AN13/RG3_6") (pintype "bidirectional"))
    )
    (net (code "417") (name "unconnected-(U6-RA6-Pad40)") (class "Default")
      (node (ref "U6") (pin "40") (pinfunction "RA6_40") (pintype "bidirectional"))
    )
    (net (code "418") (name "unconnected-(U6-RC0-Pad30)") (class "Default")
      (node (ref "U6") (pin "30") (pinfunction "RC0_30") (pintype "bidirectional"))
    )
    (net (code "419") (name "unconnected-(U6-RC1-Pad29)") (class "Default")
      (node (ref "U6") (pin "29") (pinfunction "RC1_29") (pintype "bidirectional"))
    )
    (net (code "420") (name "unconnected-(U6-RE3-Pad63)") (class "Default")
      (node (ref "U6") (pin "63") (pinfunction "RE3_63") (pintype "bidirectional"))
    )
    (net (code "421") (name "unconnected-(U6-RE6-Pad60)") (class "Default")
      (node (ref "U6") (pin "60") (pinfunction "RE6_60") (pintype "bidirectional"))
    )
    (net (code "422") (name "unconnected-(U6-RE7-Pad59)") (class "Default")
      (node (ref "U6") (pin "59") (pinfunction "RE7_59") (pintype "bidirectional"))
    )
    (net (code "423") (name "unconnected-(U6-RG0-Pad3)") (class "Default")
      (node (ref "U6") (pin "3") (pinfunction "RG0_3") (pintype "bidirectional"))
    )
    (net (code "424") (name "unconnected-(U7-AN12{slash}RG4-Pad8)") (class "Default")
      (node (ref "U7") (pin "8") (pinfunction "AN12/RG4_8") (pintype "bidirectional"))
    )
    (net (code "425") (name "unconnected-(U7-AN13{slash}RG3-Pad6)") (class "Default")
      (node (ref "U7") (pin "6") (pinfunction "AN13/RG3_6") (pintype "bidirectional"))
    )
    (net (code "426") (name "unconnected-(U7-RA6-Pad40)") (class "Default")
      (node (ref "U7") (pin "40") (pinfunction "RA6_40") (pintype "bidirectional"))
    )
    (net (code "427") (name "unconnected-(U7-RC0-Pad30)") (class "Default")
      (node (ref "U7") (pin "30") (pinfunction "RC0_30") (pintype "bidirectional"))
    )
    (net (code "428") (name "unconnected-(U7-RC1-Pad29)") (class "Default")
      (node (ref "U7") (pin "29") (pinfunction "RC1_29") (pintype "bidirectional"))
    )
    (net (code "429") (name "unconnected-(U7-RE6-Pad60)") (class "Default")
      (node (ref "U7") (pin "60") (pinfunction "RE6_60") (pintype "bidirectional"))
    )
    (net (code "430") (name "unconnected-(U7-RE7-Pad59)") (class "Default")
      (node (ref "U7") (pin "59") (pinfunction "RE7_59") (pintype "bidirectional"))
    )
    (net (code "431") (name "unconnected-(U7-RG0-Pad3)") (class "Default")
      (node (ref "U7") (pin "3") (pinfunction "RG0_3") (pintype "bidirectional"))
    )
    (net (code "432") (name "unconnected-(U8-AN12{slash}RG4-Pad8)") (class "Default")
      (node (ref "U8") (pin "8") (pinfunction "AN12/RG4_8") (pintype "bidirectional"))
    )
    (net (code "433") (name "unconnected-(U8-AN13{slash}RG3-Pad6)") (class "Default")
      (node (ref "U8") (pin "6") (pinfunction "AN13/RG3_6") (pintype "bidirectional"))
    )
    (net (code "434") (name "unconnected-(U8-RA4-Pad28)") (class "Default")
      (node (ref "U8") (pin "28") (pinfunction "RA4_28") (pintype "bidirectional"))
    )
    (net (code "435") (name "unconnected-(U8-RA6-Pad40)") (class "Default")
      (node (ref "U8") (pin "40") (pinfunction "RA6_40") (pintype "bidirectional"))
    )
    (net (code "436") (name "unconnected-(U8-RG0-Pad3)") (class "Default")
      (node (ref "U8") (pin "3") (pinfunction "RG0_3") (pintype "bidirectional"))
    )
    (net (code "437") (name "unconnected-(U11-RDY{slash}~{BSY}-Pad5)") (class "Default")
      (node (ref "U11") (pin "5") (pinfunction "RDY/~{BSY}_5") (pintype "output"))
    )
    (net (code "438") (name "unconnected-(U12-RDY{slash}~{BSY}-Pad5)") (class "Default")
      (node (ref "U12") (pin "5") (pinfunction "RDY/~{BSY}_5") (pintype "output"))
    )
    (net (code "439") (name "unconnected-(X-NORTH-PadM1)") (class "Default")
      (node (ref "X-NORTH") (pin "M1") (pinfunction "M1_M1") (pintype "bidirectional"))
    )
    (net (code "440") (name "unconnected-(X-NORTH-PadM2)") (class "Default")
      (node (ref "X-NORTH") (pin "M2") (pinfunction "M2_M2") (pintype "bidirectional"))
    )
    (net (code "441") (name "unconnected-(X-SOUTH-PadM1)") (class "Default")
      (node (ref "X-SOUTH") (pin "M1") (pinfunction "M1_M1") (pintype "bidirectional"))
    )
    (net (code "442") (name "unconnected-(X-SOUTH-PadM2)") (class "Default")
      (node (ref "X-SOUTH") (pin "M2") (pinfunction "M2_M2") (pintype "bidirectional"))
    )
    (net (code "443") (name "~{E_SS}") (class "Default")
      (node (ref "U1") (pin "11") (pinfunction "~{SS1}/AN5/RF7_11") (pintype "bidirectional"))
      (node (ref "U1") (pin "33") (pinfunction "RC2_33") (pintype "bidirectional"))
      (node (ref "U2") (pin "11") (pinfunction "~{SS1}/AN5/RF7_11") (pintype "bidirectional"))
      (node (ref "U2") (pin "33") (pinfunction "RC2_33") (pintype "bidirectional"))
      (node (ref "U5") (pin "11") (pinfunction "~{SS1}/AN5/RF7_11") (pintype "bidirectional"))
      (node (ref "U5") (pin "33") (pinfunction "RC2_33") (pintype "bidirectional"))
      (node (ref "U7") (pin "11") (pinfunction "~{SS1}/AN5/RF7_11") (pintype "bidirectional"))
      (node (ref "U7") (pin "33") (pinfunction "RC2_33") (pintype "bidirectional"))
    )
    (net (code "444") (name "~{LDAC_N}") (class "Default")
      (node (ref "U11") (pin "4") (pinfunction "~{LDAC}_4") (pintype "input"))
      (node (ref "U8") (pin "52") (pinfunction "SDO2/RD4_52") (pintype "bidirectional"))
    )
    (net (code "445") (name "~{LDAC_S}") (class "Default")
      (node (ref "U12") (pin "4") (pinfunction "~{LDAC}_4") (pintype "input"))
      (node (ref "U5") (pin "52") (pinfunction "SDO2/RD4_52") (pintype "bidirectional"))
    )
    (net (code "446") (name "~{MCLR1}") (class "Default")
      (node (ref "ICSP1") (pin "4") (pinfunction "4_4") (pintype "passive"))
      (node (ref "R12") (pin "2") (pinfunction "2_2") (pintype "passive"))
      (node (ref "U1") (pin "7") (pinfunction "~{MCLR}/RG5_7") (pintype "bidirectional"))
    )
    (net (code "447") (name "~{MCLR2}") (class "Default")
      (node (ref "ICSP2") (pin "4") (pinfunction "4_4") (pintype "passive"))
      (node (ref "R11") (pin "2") (pinfunction "2_2") (pintype "passive"))
      (node (ref "U2") (pin "7") (pinfunction "~{MCLR}/RG5_7") (pintype "bidirectional"))
    )
    (net (code "448") (name "~{MCLR3}") (class "Default")
      (node (ref "ICSP3") (pin "4") (pinfunction "4_4") (pintype "passive"))
      (node (ref "R10") (pin "2") (pinfunction "2_2") (pintype "passive"))
      (node (ref "U3") (pin "7") (pinfunction "~{MCLR}/RG5_7") (pintype "bidirectional"))
    )
    (net (code "449") (name "~{MCLR4}") (class "Default")
      (node (ref "ICSP4") (pin "4") (pinfunction "4_4") (pintype "passive"))
      (node (ref "R9") (pin "2") (pinfunction "2_2") (pintype "passive"))
      (node (ref "U4") (pin "7") (pinfunction "~{MCLR}/RG5_7") (pintype "bidirectional"))
    )
    (net (code "450") (name "~{MCLR5}") (class "Default")
      (node (ref "ICSP5") (pin "4") (pinfunction "4_4") (pintype "passive"))
      (node (ref "R8") (pin "2") (pinfunction "2_2") (pintype "passive"))
      (node (ref "U5") (pin "7") (pinfunction "~{MCLR}/RG5_7") (pintype "bidirectional"))
    )
    (net (code "451") (name "~{MCLR6}") (class "Default")
      (node (ref "ICSP6") (pin "4") (pinfunction "4_4") (pintype "passive"))
      (node (ref "R7") (pin "2") (pinfunction "2_2") (pintype "passive"))
      (node (ref "U6") (pin "7") (pinfunction "~{MCLR}/RG5_7") (pintype "bidirectional"))
    )
    (net (code "452") (name "~{MCLR7}") (class "Default")
      (node (ref "ICSP7") (pin "4") (pinfunction "4_4") (pintype "passive"))
      (node (ref "R6") (pin "2") (pinfunction "2_2") (pintype "passive"))
      (node (ref "U7") (pin "7") (pinfunction "~{MCLR}/RG5_7") (pintype "bidirectional"))
    )
    (net (code "453") (name "~{MCLR8}") (class "Default")
      (node (ref "ICSP8") (pin "4") (pinfunction "4_4") (pintype "passive"))
      (node (ref "R5") (pin "2") (pinfunction "2_2") (pintype "passive"))
      (node (ref "U8") (pin "7") (pinfunction "~{MCLR}/RG5_7") (pintype "bidirectional"))
    )
    (net (code "454") (name "~{W_SS}") (class "Default")
      (node (ref "U3") (pin "11") (pinfunction "~{SS1}/AN5/RF7_11") (pintype "bidirectional"))
      (node (ref "U3") (pin "33") (pinfunction "RC2_33") (pintype "bidirectional"))
      (node (ref "U4") (pin "11") (pinfunction "~{SS1}/AN5/RF7_11") (pintype "bidirectional"))
      (node (ref "U4") (pin "33") (pinfunction "RC2_33") (pintype "bidirectional"))
      (node (ref "U6") (pin "11") (pinfunction "~{SS1}/AN5/RF7_11") (pintype "bidirectional"))
      (node (ref "U6") (pin "33") (pinfunction "RC2_33") (pintype "bidirectional"))
      (node (ref "U8") (pin "11") (pinfunction "~{SS1}/AN5/RF7_11") (pintype "bidirectional"))
      (node (ref "U8") (pin "33") (pinfunction "RC2_33") (pintype "bidirectional"))
    )
  )
)
